# i386.net
KiCad netlist of a schematic drawn in Altium Designer
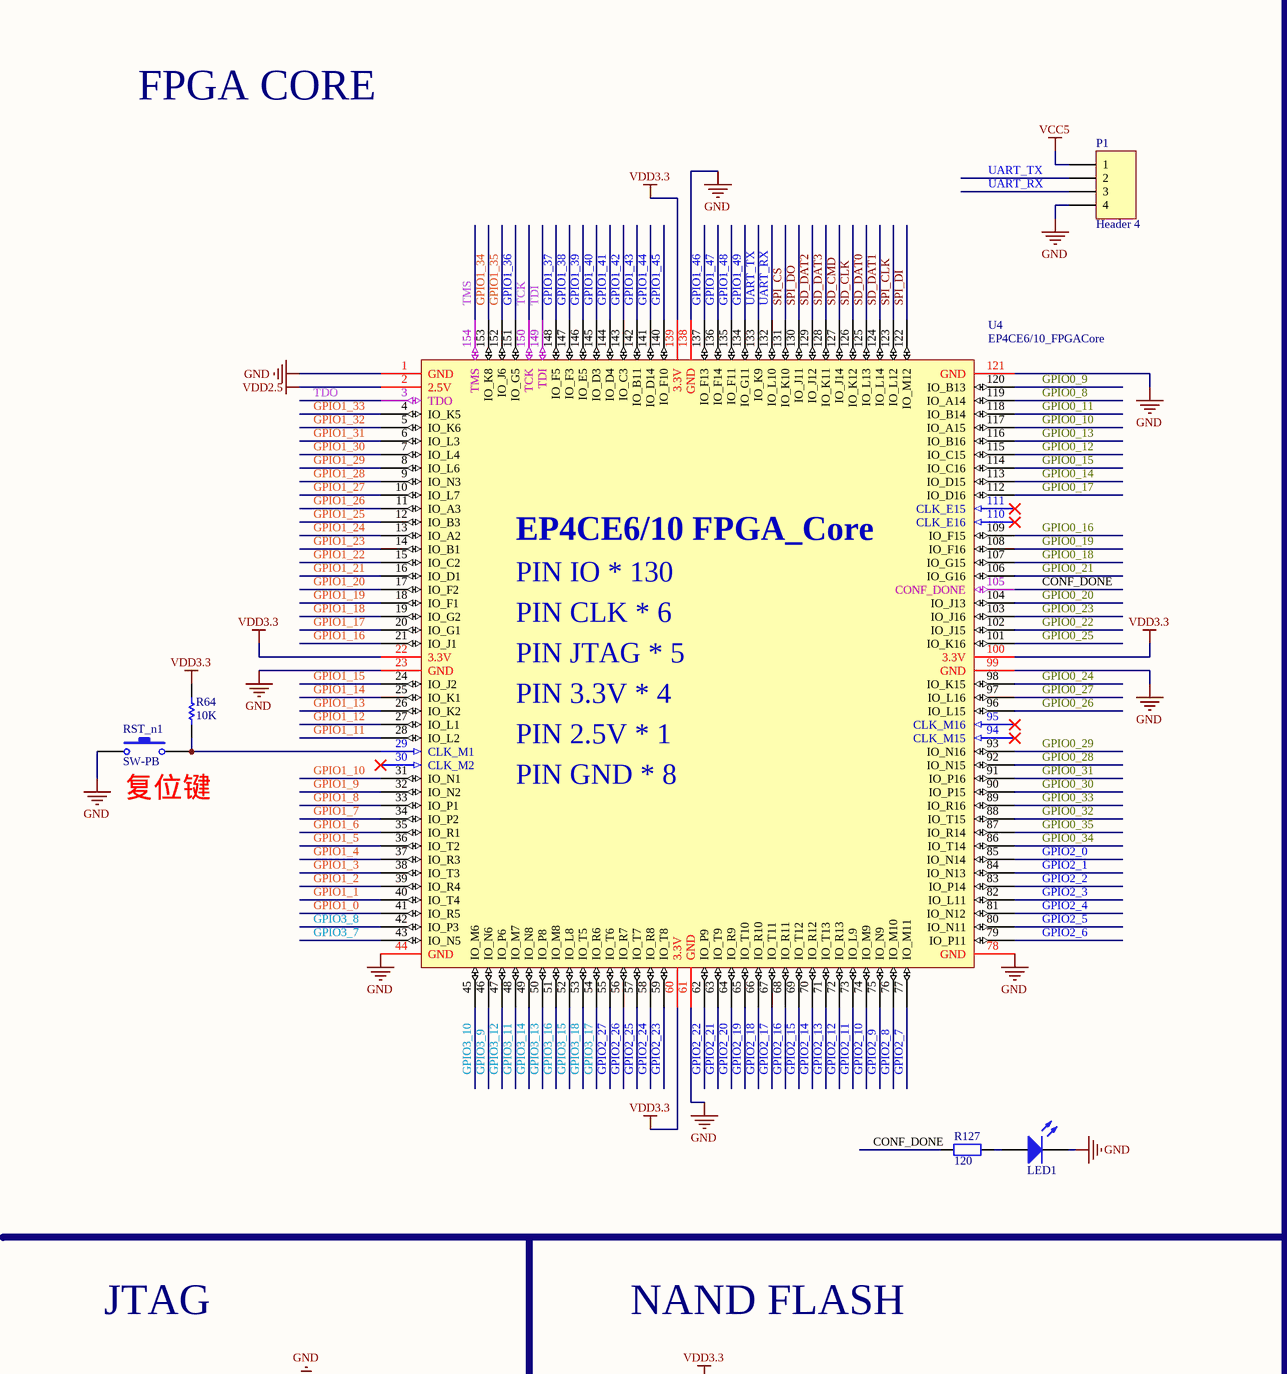
[diagram p0: i386.SchDoc, top left]
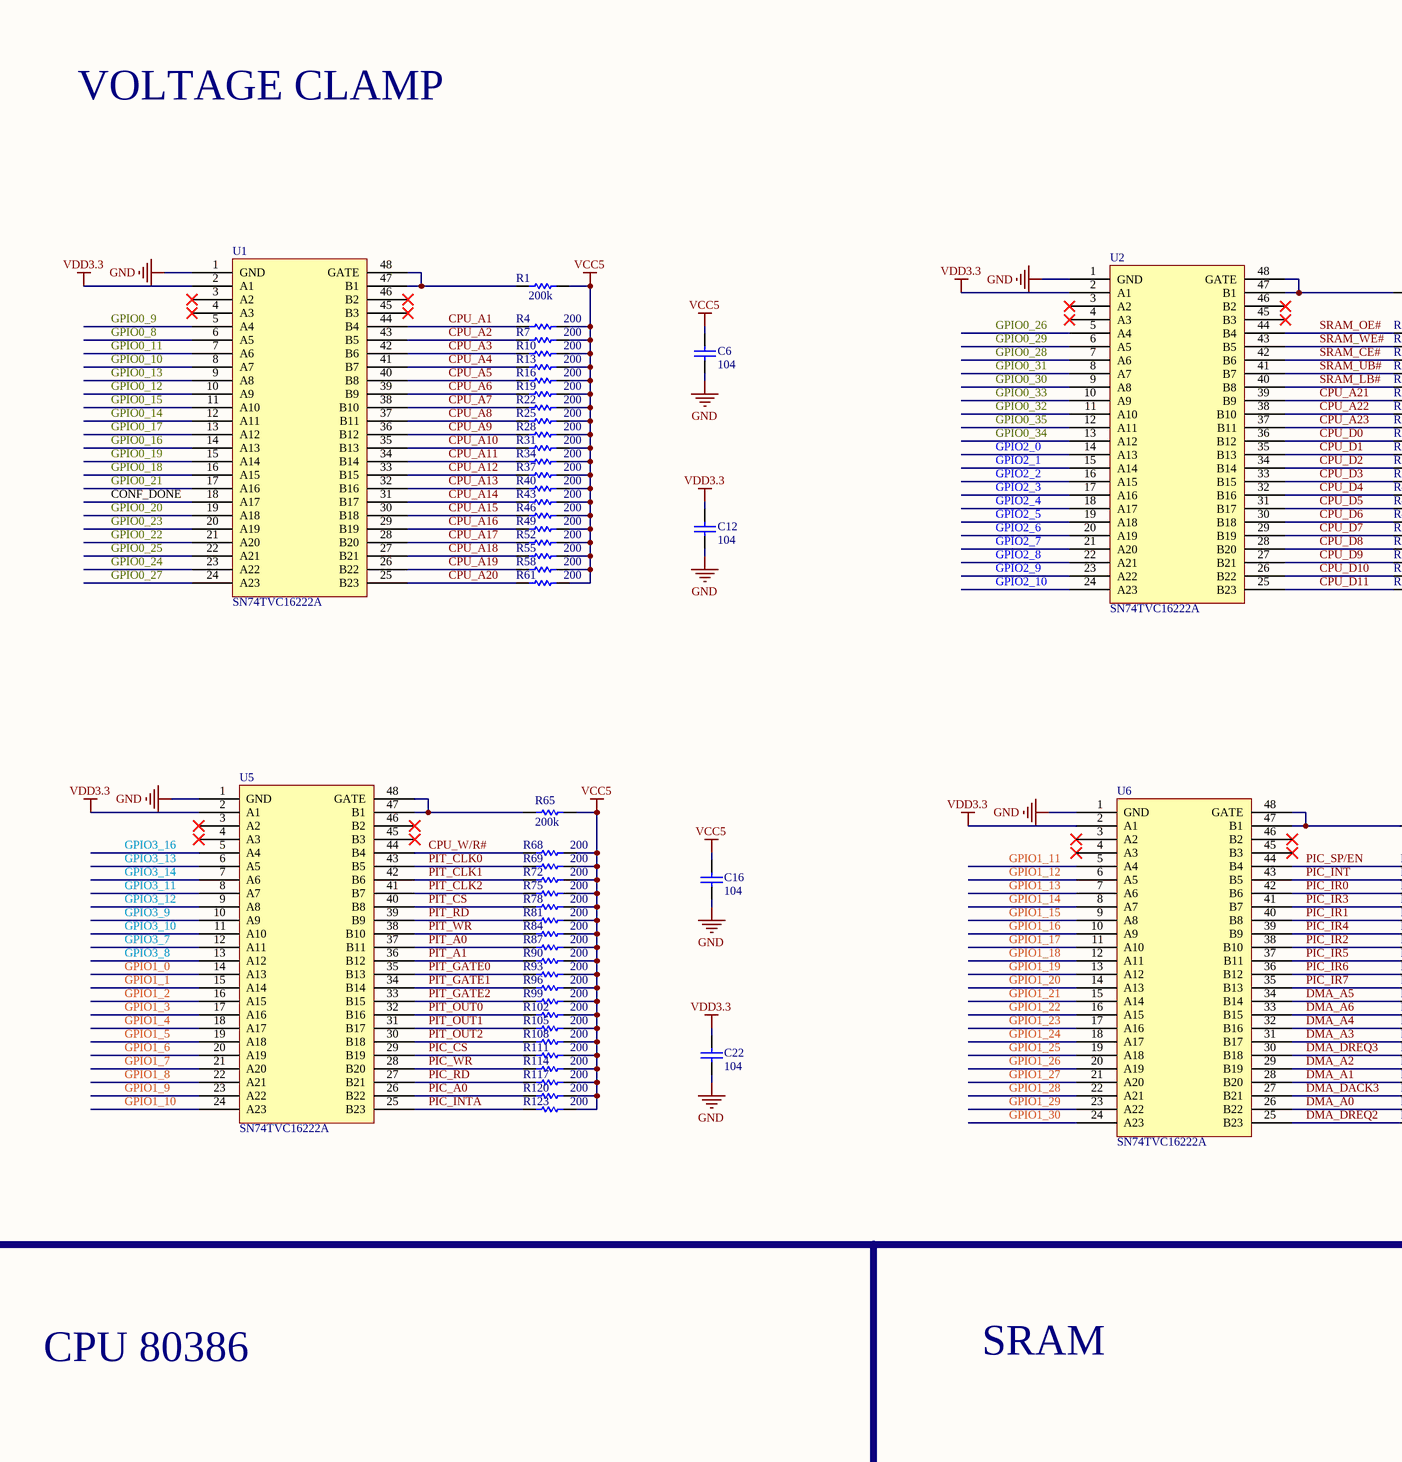
[diagram p1: i386.SchDoc, top middle]
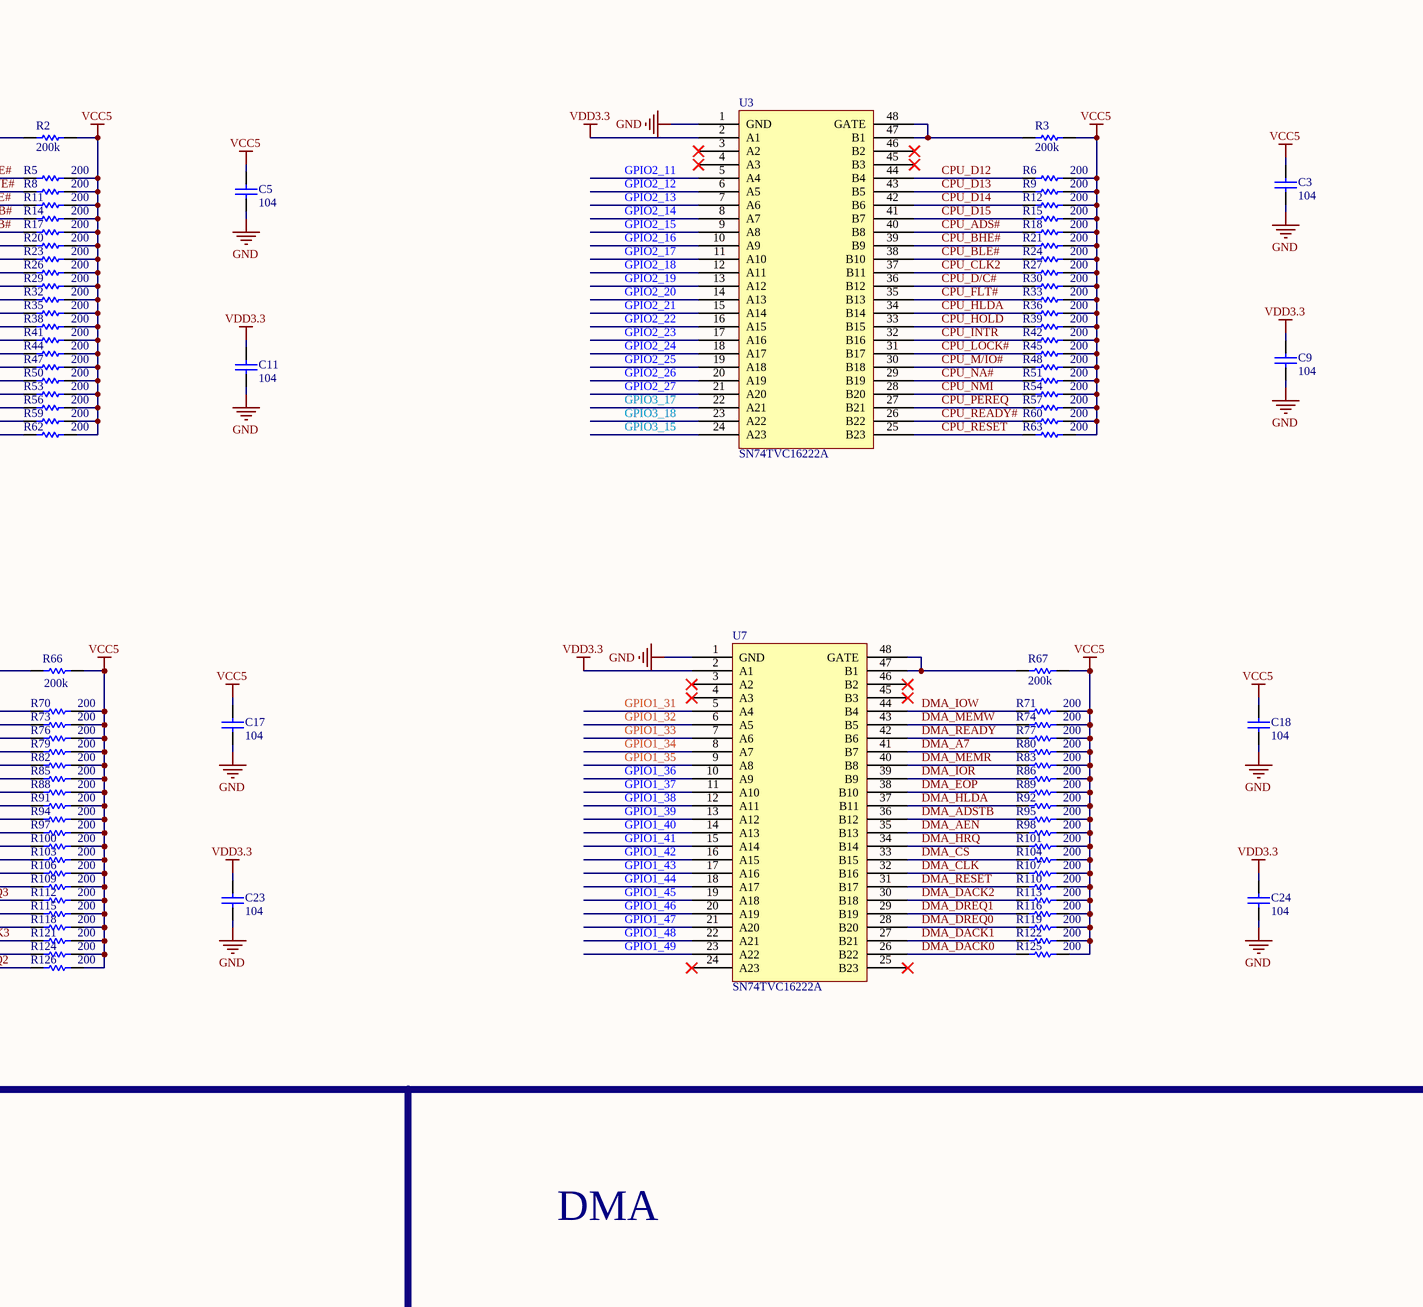
[diagram p2: i386.SchDoc, top right]
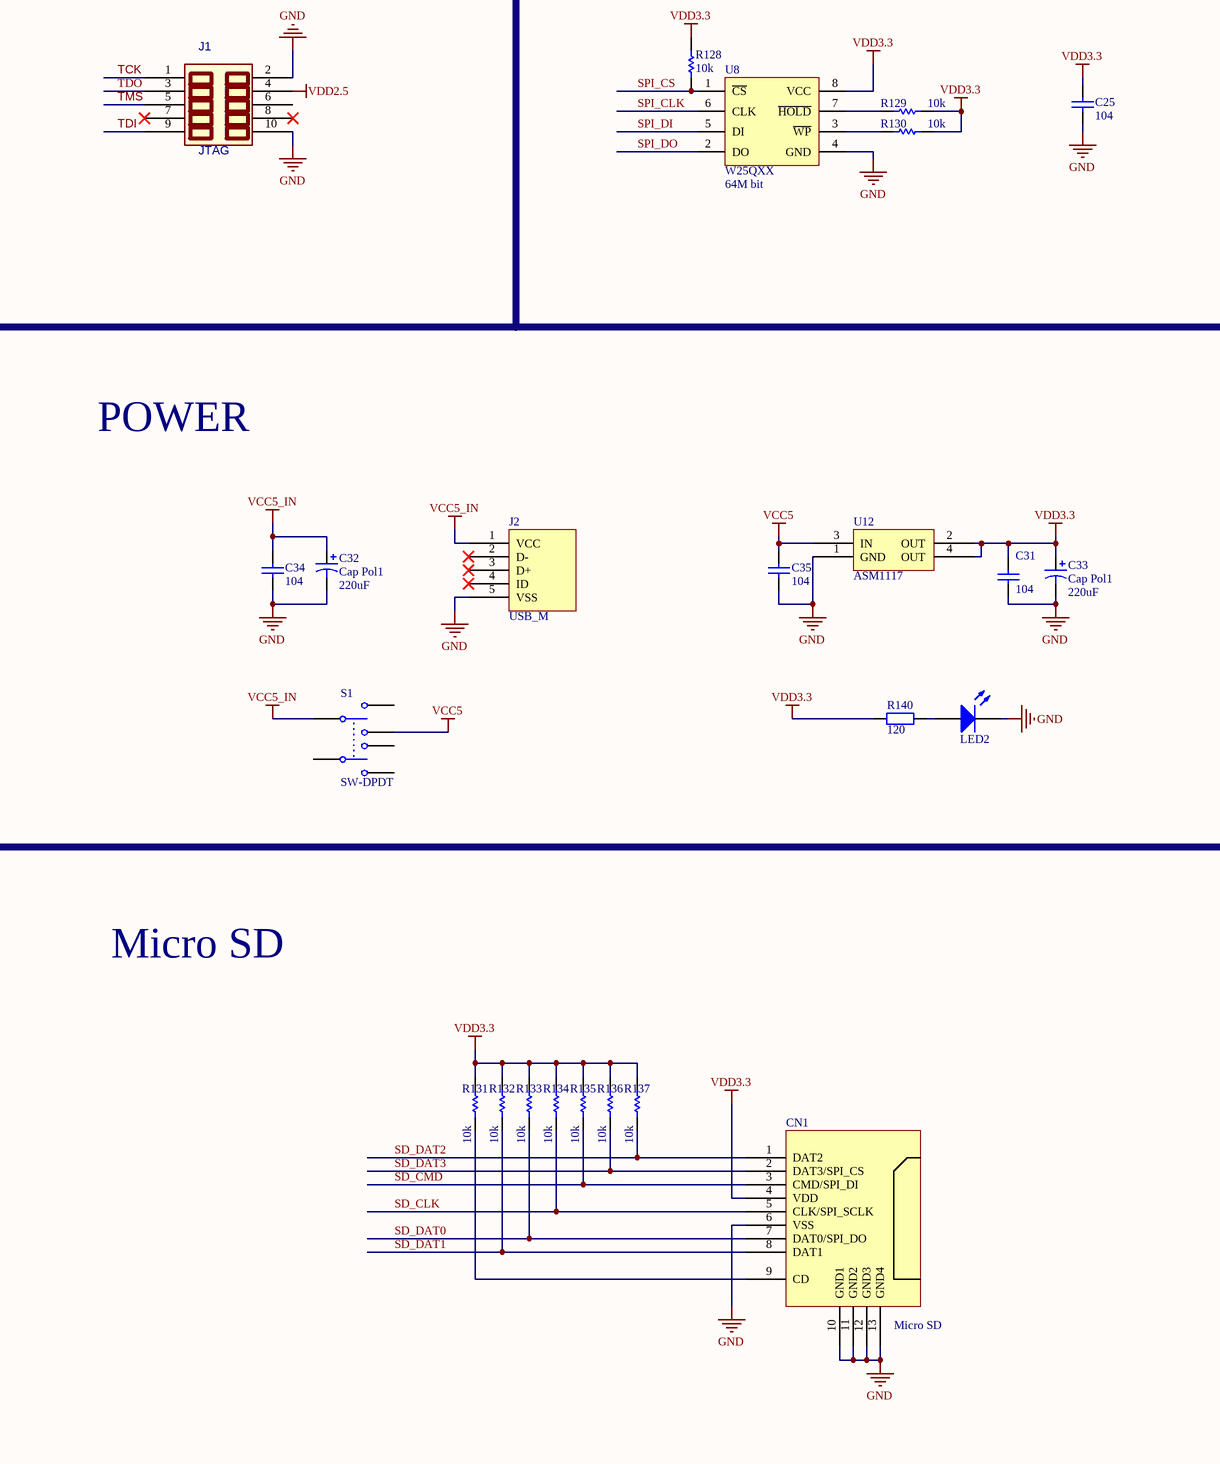
[diagram p3: i386.SchDoc, bottom left]
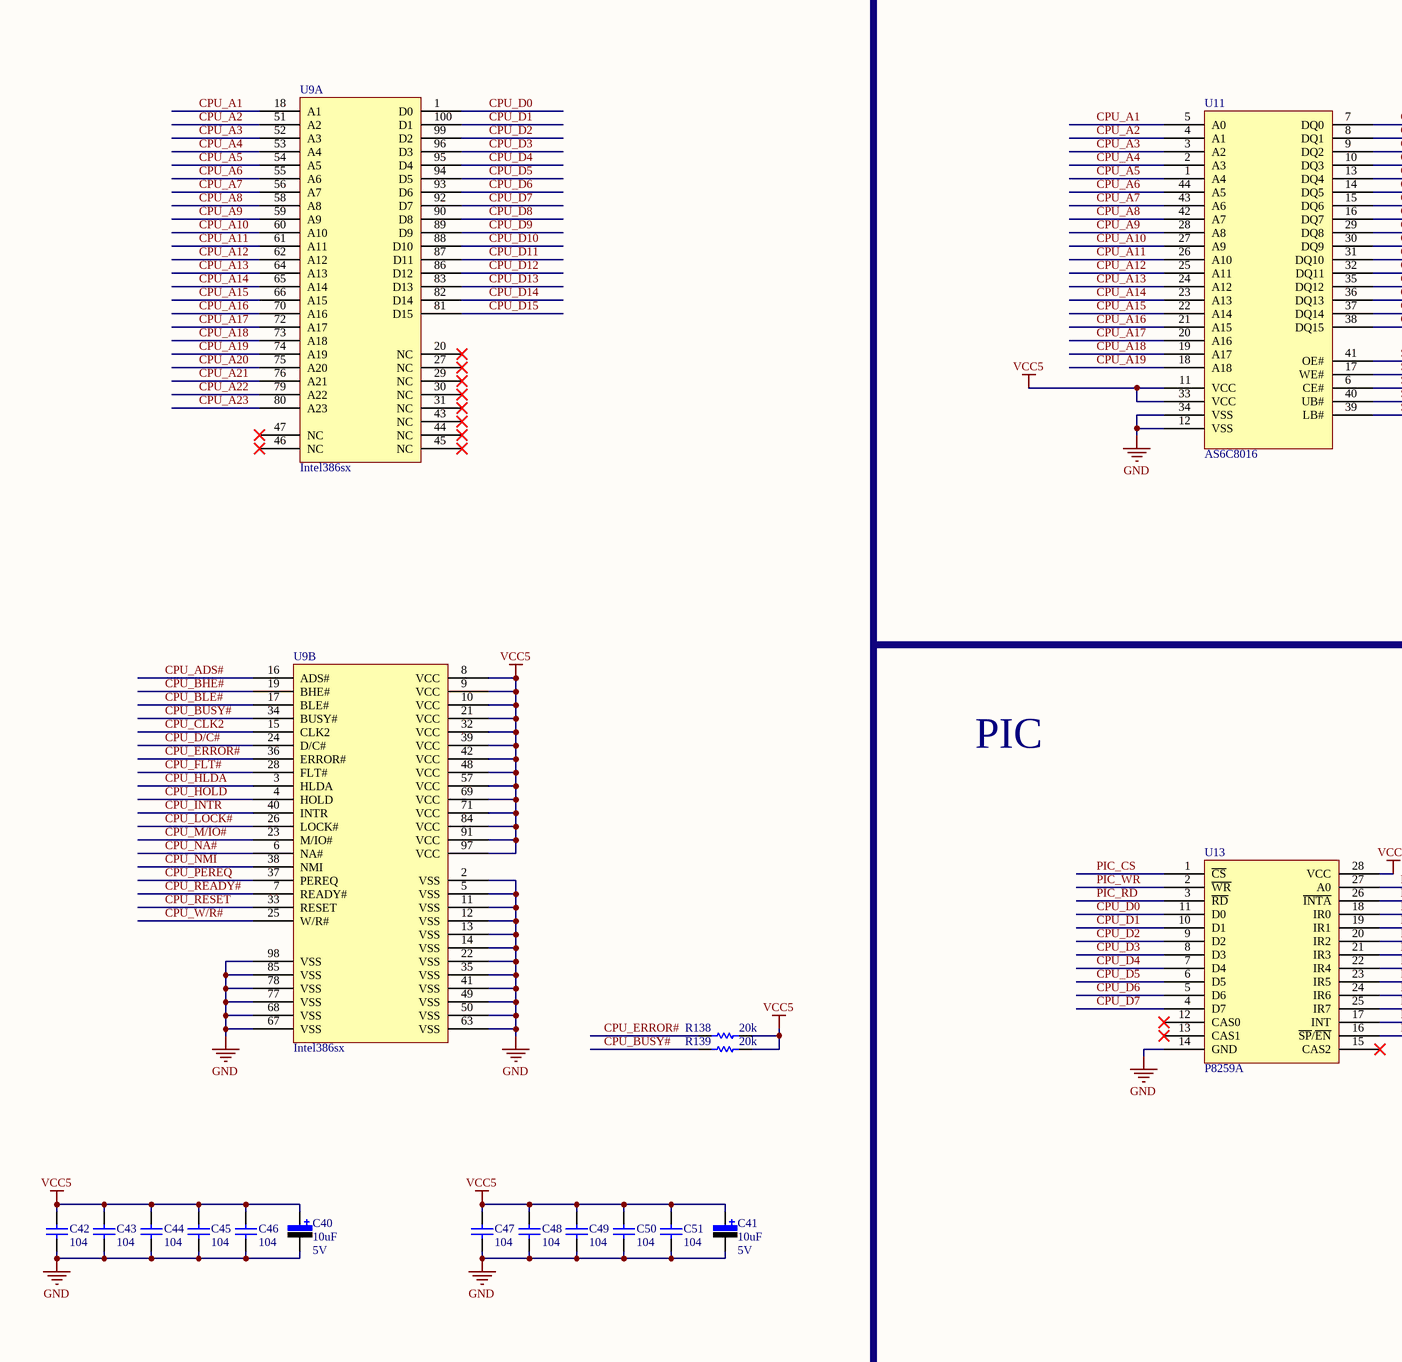
[diagram p4: i386.SchDoc, bottom middle]
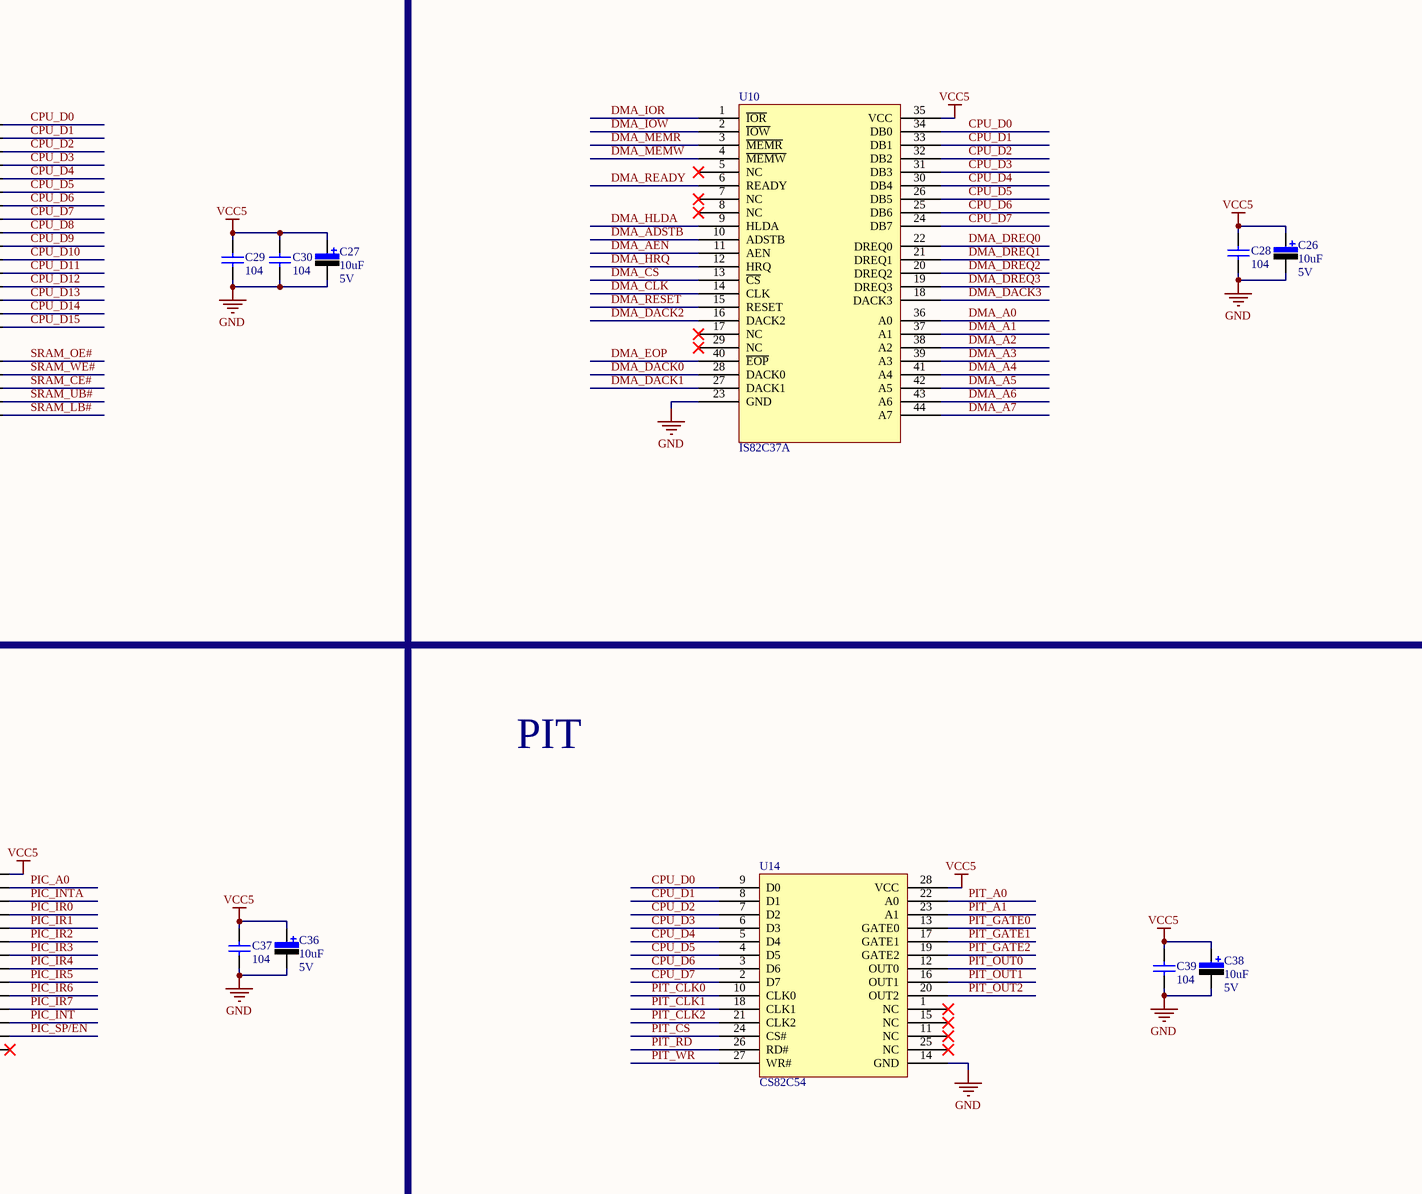
[diagram p5: i386.SchDoc, bottom right]

(export (version "E")
  (design (tool "Eeschema 10.0.6"))
  (components
    (comp (ref "C3")
      (value "104")
      (footprint "C0805")
      (description "Capacitor")
      (fields (field (name "PUBLISHER") "Altium Limited"))
      (libsource (lib "Miscellaneous Devices") (part "Cap"))
    )
    (comp (ref "C5")
      (value "104")
      (footprint "C0805")
      (description "Capacitor")
      (fields (field (name "PUBLISHER") "Altium Limited"))
      (libsource (lib "Miscellaneous Devices") (part "Cap"))
    )
    (comp (ref "C6")
      (value "104")
      (footprint "C0805")
      (description "Capacitor")
      (fields (field (name "PUBLISHER") "Altium Limited"))
      (libsource (lib "Miscellaneous Devices") (part "Cap"))
    )
    (comp (ref "C9")
      (value "104")
      (footprint "C0805")
      (description "Capacitor")
      (fields (field (name "PUBLISHER") "Altium Limited"))
      (libsource (lib "Miscellaneous Devices") (part "Cap"))
    )
    (comp (ref "C11")
      (value "104")
      (footprint "C0805")
      (description "Capacitor")
      (fields (field (name "PUBLISHER") "Altium Limited"))
      (libsource (lib "Miscellaneous Devices") (part "Cap"))
    )
    (comp (ref "C12")
      (value "104")
      (footprint "C0805")
      (description "Capacitor")
      (fields (field (name "PUBLISHER") "Altium Limited"))
      (libsource (lib "Miscellaneous Devices") (part "Cap"))
    )
    (comp (ref "C16")
      (value "104")
      (footprint "C0805")
      (description "Capacitor")
      (fields (field (name "PUBLISHER") "Altium Limited"))
      (libsource (lib "Miscellaneous Devices") (part "Cap"))
    )
    (comp (ref "C17")
      (value "104")
      (footprint "C0805")
      (description "Capacitor")
      (fields (field (name "PUBLISHER") "Altium Limited"))
      (libsource (lib "Miscellaneous Devices") (part "Cap"))
    )
    (comp (ref "C18")
      (value "104")
      (footprint "C0805")
      (description "Capacitor")
      (fields (field (name "PUBLISHER") "Altium Limited"))
      (libsource (lib "Miscellaneous Devices") (part "Cap"))
    )
    (comp (ref "C22")
      (value "104")
      (footprint "C0805")
      (description "Capacitor")
      (fields (field (name "PUBLISHER") "Altium Limited"))
      (libsource (lib "Miscellaneous Devices") (part "Cap"))
    )
    (comp (ref "C23")
      (value "104")
      (footprint "C0805")
      (description "Capacitor")
      (fields (field (name "PUBLISHER") "Altium Limited"))
      (libsource (lib "Miscellaneous Devices") (part "Cap"))
    )
    (comp (ref "C24")
      (value "104")
      (footprint "C0805")
      (description "Capacitor")
      (fields (field (name "PUBLISHER") "Altium Limited"))
      (libsource (lib "Miscellaneous Devices") (part "Cap"))
    )
    (comp (ref "C25")
      (value "104")
      (footprint "C0805")
      (description "Capacitor")
      (fields (field (name "PUBLISHER") "Altium Limited"))
      (libsource (lib "Miscellaneous Devices") (part "Cap"))
    )
    (comp (ref "C26")
      (value "10uF")
      (footprint "CAP-3528")
      (description "极性电解电容")
      (fields
        (field (name "VOL") "5V")
        (field (name "Comment") "Cap Pol")
        (field (name "PUBLISHER") "Altium Limited")
      )
      (libsource (lib "k7_ext") (part "Cap Pol"))
    )
    (comp (ref "C27")
      (value "10uF")
      (footprint "CAP-3528")
      (description "极性电解电容")
      (fields
        (field (name "VOL") "5V")
        (field (name "Comment") "Cap Pol")
        (field (name "PUBLISHER") "Altium Limited")
      )
      (libsource (lib "k7_ext") (part "Cap Pol"))
    )
    (comp (ref "C28")
      (value "104")
      (footprint "C0805")
      (description "Capacitor")
      (fields (field (name "PUBLISHER") "Altium Limited"))
      (libsource (lib "Miscellaneous Devices") (part "Cap"))
    )
    (comp (ref "C29")
      (value "104")
      (footprint "C0805")
      (description "Capacitor")
      (fields (field (name "PUBLISHER") "Altium Limited"))
      (libsource (lib "Miscellaneous Devices") (part "Cap"))
    )
    (comp (ref "C30")
      (value "104")
      (footprint "C0805")
      (description "Capacitor")
      (fields (field (name "PUBLISHER") "Altium Limited"))
      (libsource (lib "Miscellaneous Devices") (part "Cap"))
    )
    (comp (ref "C31")
      (value "104")
      (footprint "C0805")
      (description "Capacitor")
      (fields (field (name "PUBLISHER") "Altium Limited"))
      (libsource (lib "Miscellaneous Devices") (part "Cap"))
    )
    (comp (ref "C32")
      (value "Cap Pol1")
      (footprint "C-RB-S8")
      (description "Polarized Capacitor (Radial)")
      (fields (field (name "ALTIUM_VALUE") "220uF") (field (name "PUBLISHER") "Altium Limited"))
      (libsource (lib "Miscellaneous Devices") (part "Cap Pol1"))
    )
    (comp (ref "C33")
      (value "Cap Pol1")
      (footprint "C-RB-S8")
      (description "Polarized Capacitor (Radial)")
      (fields (field (name "ALTIUM_VALUE") "220uF") (field (name "PUBLISHER") "Altium Limited"))
      (libsource (lib "Miscellaneous Devices") (part "Cap Pol1"))
    )
    (comp (ref "C34")
      (value "104")
      (footprint "C0805")
      (description "Capacitor")
      (fields (field (name "PUBLISHER") "Altium Limited"))
      (libsource (lib "Miscellaneous Devices") (part "Cap"))
    )
    (comp (ref "C35")
      (value "104")
      (footprint "C0805")
      (description "Capacitor")
      (fields (field (name "PUBLISHER") "Altium Limited"))
      (libsource (lib "Miscellaneous Devices") (part "Cap"))
    )
    (comp (ref "C36")
      (value "10uF")
      (footprint "CAP-3528")
      (description "极性电解电容")
      (fields
        (field (name "VOL") "5V")
        (field (name "Comment") "Cap Pol")
        (field (name "PUBLISHER") "Altium Limited")
      )
      (libsource (lib "k7_ext") (part "Cap Pol"))
    )
    (comp (ref "C37")
      (value "104")
      (footprint "C0805")
      (description "Capacitor")
      (fields (field (name "PUBLISHER") "Altium Limited"))
      (libsource (lib "Miscellaneous Devices") (part "Cap"))
    )
    (comp (ref "C38")
      (value "10uF")
      (footprint "CAP-3528")
      (description "极性电解电容")
      (fields
        (field (name "VOL") "5V")
        (field (name "Comment") "Cap Pol")
        (field (name "PUBLISHER") "Altium Limited")
      )
      (libsource (lib "k7_ext") (part "Cap Pol"))
    )
    (comp (ref "C39")
      (value "104")
      (footprint "C0805")
      (description "Capacitor")
      (fields (field (name "PUBLISHER") "Altium Limited"))
      (libsource (lib "Miscellaneous Devices") (part "Cap"))
    )
    (comp (ref "C40")
      (value "10uF")
      (footprint "CAP-3528")
      (description "极性电解电容")
      (fields
        (field (name "VOL") "5V")
        (field (name "Comment") "Cap Pol")
        (field (name "PUBLISHER") "Altium Limited")
      )
      (libsource (lib "k7_ext") (part "Cap Pol"))
    )
    (comp (ref "C41")
      (value "10uF")
      (footprint "CAP-3528")
      (description "极性电解电容")
      (fields
        (field (name "VOL") "5V")
        (field (name "Comment") "Cap Pol")
        (field (name "PUBLISHER") "Altium Limited")
      )
      (libsource (lib "k7_ext") (part "Cap Pol"))
    )
    (comp (ref "C42")
      (value "104")
      (footprint "C0805")
      (description "Capacitor")
      (fields (field (name "PUBLISHER") "Altium Limited"))
      (libsource (lib "Miscellaneous Devices") (part "Cap"))
    )
    (comp (ref "C43")
      (value "104")
      (footprint "C0805")
      (description "Capacitor")
      (fields (field (name "PUBLISHER") "Altium Limited"))
      (libsource (lib "Miscellaneous Devices") (part "Cap"))
    )
    (comp (ref "C44")
      (value "104")
      (footprint "C0805")
      (description "Capacitor")
      (fields (field (name "PUBLISHER") "Altium Limited"))
      (libsource (lib "Miscellaneous Devices") (part "Cap"))
    )
    (comp (ref "C45")
      (value "104")
      (footprint "C0805")
      (description "Capacitor")
      (fields (field (name "PUBLISHER") "Altium Limited"))
      (libsource (lib "Miscellaneous Devices") (part "Cap"))
    )
    (comp (ref "C46")
      (value "104")
      (footprint "C0805")
      (description "Capacitor")
      (fields (field (name "PUBLISHER") "Altium Limited"))
      (libsource (lib "Miscellaneous Devices") (part "Cap"))
    )
    (comp (ref "C47")
      (value "104")
      (footprint "C0805")
      (description "Capacitor")
      (fields (field (name "PUBLISHER") "Altium Limited"))
      (libsource (lib "Miscellaneous Devices") (part "Cap"))
    )
    (comp (ref "C48")
      (value "104")
      (footprint "C0805")
      (description "Capacitor")
      (fields (field (name "PUBLISHER") "Altium Limited"))
      (libsource (lib "Miscellaneous Devices") (part "Cap"))
    )
    (comp (ref "C49")
      (value "104")
      (footprint "C0805")
      (description "Capacitor")
      (fields (field (name "PUBLISHER") "Altium Limited"))
      (libsource (lib "Miscellaneous Devices") (part "Cap"))
    )
    (comp (ref "C50")
      (value "104")
      (footprint "C0805")
      (description "Capacitor")
      (fields (field (name "PUBLISHER") "Altium Limited"))
      (libsource (lib "Miscellaneous Devices") (part "Cap"))
    )
    (comp (ref "C51")
      (value "104")
      (footprint "C0805")
      (description "Capacitor")
      (fields (field (name "PUBLISHER") "Altium Limited"))
      (libsource (lib "Miscellaneous Devices") (part "Cap"))
    )
    (comp (ref "CN1")
      (value "Micro SD")
      (footprint "SDCARD-M")
      (description "Micro SD卡座")
      (libsource (lib "k7_ext") (part "Micro SD卡座"))
    )
    (comp (ref "J1") (value "JTAG") (footprint "HDR5X2_B1") (libsource (lib "*") (part "JTAG-10_Dup1")))
    (comp (ref "J2")
      (value "USB_M")
      (footprint "USB_MICRO")
      (description "MicroUSB接口")
      (libsource (lib "k7_ext") (part "USB_M"))
    )
    (comp (ref "LED1")
      (value "LED0")
      (footprint "LED-0402")
      (description "发光二极管")
      (fields (field (name "PUBLISHER") "Altium Limited"))
      (libsource (lib "k7_ext") (part "LED0"))
    )
    (comp (ref "LED2")
      (value "LED0")
      (footprint "LED-0402")
      (description "发光二极管")
      (fields (field (name "PUBLISHER") "Altium Limited"))
      (libsource (lib "k7_ext") (part "LED0"))
    )
    (comp (ref "P1")
      (value "Header 4")
      (footprint "HDR1X4")
      (description "Header, 4-Pin")
      (fields (field (name "PUBLISHER") "Altium Limited"))
      (libsource (lib "Miscellaneous Connectors") (part "Header 4"))
    )
    (comp (ref "R1")
      (value "200k")
      (footprint "0402")
      (description "Resistor")
      (fields (field (name "Comment") "Res1") (field (name "PUBLISHER") "Altium Limited"))
      (libsource (lib "Miscellaneous Devices") (part "Res1"))
    )
    (comp (ref "R2")
      (value "200k")
      (footprint "0402")
      (description "Resistor")
      (fields (field (name "Comment") "Res1") (field (name "PUBLISHER") "Altium Limited"))
      (libsource (lib "Miscellaneous Devices") (part "Res1"))
    )
    (comp (ref "R3")
      (value "200k")
      (footprint "0402")
      (description "Resistor")
      (fields (field (name "Comment") "Res1") (field (name "PUBLISHER") "Altium Limited"))
      (libsource (lib "Miscellaneous Devices") (part "Res1"))
    )
    (comp (ref "R4")
      (value "200")
      (footprint "0402")
      (description "Resistor")
      (fields (field (name "Comment") "Res1") (field (name "PUBLISHER") "Altium Limited"))
      (libsource (lib "Miscellaneous Devices") (part "Res1"))
    )
    (comp (ref "R5")
      (value "200")
      (footprint "0402")
      (description "Resistor")
      (fields (field (name "Comment") "Res1") (field (name "PUBLISHER") "Altium Limited"))
      (libsource (lib "Miscellaneous Devices") (part "Res1"))
    )
    (comp (ref "R6")
      (value "200")
      (footprint "0402")
      (description "Resistor")
      (fields (field (name "Comment") "Res1") (field (name "PUBLISHER") "Altium Limited"))
      (libsource (lib "Miscellaneous Devices") (part "Res1"))
    )
    (comp (ref "R7")
      (value "200")
      (footprint "0402")
      (description "Resistor")
      (fields (field (name "Comment") "Res1") (field (name "PUBLISHER") "Altium Limited"))
      (libsource (lib "Miscellaneous Devices") (part "Res1"))
    )
    (comp (ref "R8")
      (value "200")
      (footprint "0402")
      (description "Resistor")
      (fields (field (name "Comment") "Res1") (field (name "PUBLISHER") "Altium Limited"))
      (libsource (lib "Miscellaneous Devices") (part "Res1"))
    )
    (comp (ref "R9")
      (value "200")
      (footprint "0402")
      (description "Resistor")
      (fields (field (name "Comment") "Res1") (field (name "PUBLISHER") "Altium Limited"))
      (libsource (lib "Miscellaneous Devices") (part "Res1"))
    )
    (comp (ref "R10")
      (value "200")
      (footprint "0402")
      (description "Resistor")
      (fields (field (name "Comment") "Res1") (field (name "PUBLISHER") "Altium Limited"))
      (libsource (lib "Miscellaneous Devices") (part "Res1"))
    )
    (comp (ref "R11")
      (value "200")
      (footprint "0402")
      (description "Resistor")
      (fields (field (name "Comment") "Res1") (field (name "PUBLISHER") "Altium Limited"))
      (libsource (lib "Miscellaneous Devices") (part "Res1"))
    )
    (comp (ref "R12")
      (value "200")
      (footprint "0402")
      (description "Resistor")
      (fields (field (name "Comment") "Res1") (field (name "PUBLISHER") "Altium Limited"))
      (libsource (lib "Miscellaneous Devices") (part "Res1"))
    )
    (comp (ref "R13")
      (value "200")
      (footprint "0402")
      (description "Resistor")
      (fields (field (name "Comment") "Res1") (field (name "PUBLISHER") "Altium Limited"))
      (libsource (lib "Miscellaneous Devices") (part "Res1"))
    )
    (comp (ref "R14")
      (value "200")
      (footprint "0402")
      (description "Resistor")
      (fields (field (name "Comment") "Res1") (field (name "PUBLISHER") "Altium Limited"))
      (libsource (lib "Miscellaneous Devices") (part "Res1"))
    )
    (comp (ref "R15")
      (value "200")
      (footprint "0402")
      (description "Resistor")
      (fields (field (name "Comment") "Res1") (field (name "PUBLISHER") "Altium Limited"))
      (libsource (lib "Miscellaneous Devices") (part "Res1"))
    )
    (comp (ref "R16")
      (value "200")
      (footprint "0402")
      (description "Resistor")
      (fields (field (name "Comment") "Res1") (field (name "PUBLISHER") "Altium Limited"))
      (libsource (lib "Miscellaneous Devices") (part "Res1"))
    )
    (comp (ref "R17")
      (value "200")
      (footprint "0402")
      (description "Resistor")
      (fields (field (name "Comment") "Res1") (field (name "PUBLISHER") "Altium Limited"))
      (libsource (lib "Miscellaneous Devices") (part "Res1"))
    )
    (comp (ref "R18")
      (value "200")
      (footprint "0402")
      (description "Resistor")
      (fields (field (name "Comment") "Res1") (field (name "PUBLISHER") "Altium Limited"))
      (libsource (lib "Miscellaneous Devices") (part "Res1"))
    )
    (comp (ref "R19")
      (value "200")
      (footprint "0402")
      (description "Resistor")
      (fields (field (name "Comment") "Res1") (field (name "PUBLISHER") "Altium Limited"))
      (libsource (lib "Miscellaneous Devices") (part "Res1"))
    )
    (comp (ref "R20")
      (value "200")
      (footprint "0402")
      (description "Resistor")
      (fields (field (name "Comment") "Res1") (field (name "PUBLISHER") "Altium Limited"))
      (libsource (lib "Miscellaneous Devices") (part "Res1"))
    )
    (comp (ref "R21")
      (value "200")
      (footprint "0402")
      (description "Resistor")
      (fields (field (name "Comment") "Res1") (field (name "PUBLISHER") "Altium Limited"))
      (libsource (lib "Miscellaneous Devices") (part "Res1"))
    )
    (comp (ref "R22")
      (value "200")
      (footprint "0402")
      (description "Resistor")
      (fields (field (name "Comment") "Res1") (field (name "PUBLISHER") "Altium Limited"))
      (libsource (lib "Miscellaneous Devices") (part "Res1"))
    )
    (comp (ref "R23")
      (value "200")
      (footprint "0402")
      (description "Resistor")
      (fields (field (name "Comment") "Res1") (field (name "PUBLISHER") "Altium Limited"))
      (libsource (lib "Miscellaneous Devices") (part "Res1"))
    )
    (comp (ref "R24")
      (value "200")
      (footprint "0402")
      (description "Resistor")
      (fields (field (name "Comment") "Res1") (field (name "PUBLISHER") "Altium Limited"))
      (libsource (lib "Miscellaneous Devices") (part "Res1"))
    )
    (comp (ref "R25")
      (value "200")
      (footprint "0402")
      (description "Resistor")
      (fields (field (name "Comment") "Res1") (field (name "PUBLISHER") "Altium Limited"))
      (libsource (lib "Miscellaneous Devices") (part "Res1"))
    )
    (comp (ref "R26")
      (value "200")
      (footprint "0402")
      (description "Resistor")
      (fields (field (name "Comment") "Res1") (field (name "PUBLISHER") "Altium Limited"))
      (libsource (lib "Miscellaneous Devices") (part "Res1"))
    )
    (comp (ref "R27")
      (value "200")
      (footprint "0402")
      (description "Resistor")
      (fields (field (name "Comment") "Res1") (field (name "PUBLISHER") "Altium Limited"))
      (libsource (lib "Miscellaneous Devices") (part "Res1"))
    )
    (comp (ref "R28")
      (value "200")
      (footprint "0402")
      (description "Resistor")
      (fields (field (name "Comment") "Res1") (field (name "PUBLISHER") "Altium Limited"))
      (libsource (lib "Miscellaneous Devices") (part "Res1"))
    )
    (comp (ref "R29")
      (value "200")
      (footprint "0402")
      (description "Resistor")
      (fields (field (name "Comment") "Res1") (field (name "PUBLISHER") "Altium Limited"))
      (libsource (lib "Miscellaneous Devices") (part "Res1"))
    )
    (comp (ref "R30")
      (value "200")
      (footprint "0402")
      (description "Resistor")
      (fields (field (name "Comment") "Res1") (field (name "PUBLISHER") "Altium Limited"))
      (libsource (lib "Miscellaneous Devices") (part "Res1"))
    )
    (comp (ref "R31")
      (value "200")
      (footprint "0402")
      (description "Resistor")
      (fields (field (name "Comment") "Res1") (field (name "PUBLISHER") "Altium Limited"))
      (libsource (lib "Miscellaneous Devices") (part "Res1"))
    )
    (comp (ref "R32")
      (value "200")
      (footprint "0402")
      (description "Resistor")
      (fields (field (name "Comment") "Res1") (field (name "PUBLISHER") "Altium Limited"))
      (libsource (lib "Miscellaneous Devices") (part "Res1"))
    )
    (comp (ref "R33")
      (value "200")
      (footprint "0402")
      (description "Resistor")
      (fields (field (name "Comment") "Res1") (field (name "PUBLISHER") "Altium Limited"))
      (libsource (lib "Miscellaneous Devices") (part "Res1"))
    )
    (comp (ref "R34")
      (value "200")
      (footprint "0402")
      (description "Resistor")
      (fields (field (name "Comment") "Res1") (field (name "PUBLISHER") "Altium Limited"))
      (libsource (lib "Miscellaneous Devices") (part "Res1"))
    )
    (comp (ref "R35")
      (value "200")
      (footprint "0402")
      (description "Resistor")
      (fields (field (name "Comment") "Res1") (field (name "PUBLISHER") "Altium Limited"))
      (libsource (lib "Miscellaneous Devices") (part "Res1"))
    )
    (comp (ref "R36")
      (value "200")
      (footprint "0402")
      (description "Resistor")
      (fields (field (name "Comment") "Res1") (field (name "PUBLISHER") "Altium Limited"))
      (libsource (lib "Miscellaneous Devices") (part "Res1"))
    )
    (comp (ref "R37")
      (value "200")
      (footprint "0402")
      (description "Resistor")
      (fields (field (name "Comment") "Res1") (field (name "PUBLISHER") "Altium Limited"))
      (libsource (lib "Miscellaneous Devices") (part "Res1"))
    )
    (comp (ref "R38")
      (value "200")
      (footprint "0402")
      (description "Resistor")
      (fields (field (name "Comment") "Res1") (field (name "PUBLISHER") "Altium Limited"))
      (libsource (lib "Miscellaneous Devices") (part "Res1"))
    )
    (comp (ref "R39")
      (value "200")
      (footprint "0402")
      (description "Resistor")
      (fields (field (name "Comment") "Res1") (field (name "PUBLISHER") "Altium Limited"))
      (libsource (lib "Miscellaneous Devices") (part "Res1"))
    )
    (comp (ref "R40")
      (value "200")
      (footprint "0402")
      (description "Resistor")
      (fields (field (name "Comment") "Res1") (field (name "PUBLISHER") "Altium Limited"))
      (libsource (lib "Miscellaneous Devices") (part "Res1"))
    )
    (comp (ref "R41")
      (value "200")
      (footprint "0402")
      (description "Resistor")
      (fields (field (name "Comment") "Res1") (field (name "PUBLISHER") "Altium Limited"))
      (libsource (lib "Miscellaneous Devices") (part "Res1"))
    )
    (comp (ref "R42")
      (value "200")
      (footprint "0402")
      (description "Resistor")
      (fields (field (name "Comment") "Res1") (field (name "PUBLISHER") "Altium Limited"))
      (libsource (lib "Miscellaneous Devices") (part "Res1"))
    )
    (comp (ref "R43")
      (value "200")
      (footprint "0402")
      (description "Resistor")
      (fields (field (name "Comment") "Res1") (field (name "PUBLISHER") "Altium Limited"))
      (libsource (lib "Miscellaneous Devices") (part "Res1"))
    )
    (comp (ref "R44")
      (value "200")
      (footprint "0402")
      (description "Resistor")
      (fields (field (name "Comment") "Res1") (field (name "PUBLISHER") "Altium Limited"))
      (libsource (lib "Miscellaneous Devices") (part "Res1"))
    )
    (comp (ref "R45")
      (value "200")
      (footprint "0402")
      (description "Resistor")
      (fields (field (name "Comment") "Res1") (field (name "PUBLISHER") "Altium Limited"))
      (libsource (lib "Miscellaneous Devices") (part "Res1"))
    )
    (comp (ref "R46")
      (value "200")
      (footprint "0402")
      (description "Resistor")
      (fields (field (name "Comment") "Res1") (field (name "PUBLISHER") "Altium Limited"))
      (libsource (lib "Miscellaneous Devices") (part "Res1"))
    )
    (comp (ref "R47")
      (value "200")
      (footprint "0402")
      (description "Resistor")
      (fields (field (name "Comment") "Res1") (field (name "PUBLISHER") "Altium Limited"))
      (libsource (lib "Miscellaneous Devices") (part "Res1"))
    )
    (comp (ref "R48")
      (value "200")
      (footprint "0402")
      (description "Resistor")
      (fields (field (name "Comment") "Res1") (field (name "PUBLISHER") "Altium Limited"))
      (libsource (lib "Miscellaneous Devices") (part "Res1"))
    )
    (comp (ref "R49")
      (value "200")
      (footprint "0402")
      (description "Resistor")
      (fields (field (name "Comment") "Res1") (field (name "PUBLISHER") "Altium Limited"))
      (libsource (lib "Miscellaneous Devices") (part "Res1"))
    )
    (comp (ref "R50")
      (value "200")
      (footprint "0402")
      (description "Resistor")
      (fields (field (name "Comment") "Res1") (field (name "PUBLISHER") "Altium Limited"))
      (libsource (lib "Miscellaneous Devices") (part "Res1"))
    )
    (comp (ref "R51")
      (value "200")
      (footprint "0402")
      (description "Resistor")
      (fields (field (name "Comment") "Res1") (field (name "PUBLISHER") "Altium Limited"))
      (libsource (lib "Miscellaneous Devices") (part "Res1"))
    )
    (comp (ref "R52")
      (value "200")
      (footprint "0402")
      (description "Resistor")
      (fields (field (name "Comment") "Res1") (field (name "PUBLISHER") "Altium Limited"))
      (libsource (lib "Miscellaneous Devices") (part "Res1"))
    )
    (comp (ref "R53")
      (value "200")
      (footprint "0402")
      (description "Resistor")
      (fields (field (name "Comment") "Res1") (field (name "PUBLISHER") "Altium Limited"))
      (libsource (lib "Miscellaneous Devices") (part "Res1"))
    )
    (comp (ref "R54")
      (value "200")
      (footprint "0402")
      (description "Resistor")
      (fields (field (name "Comment") "Res1") (field (name "PUBLISHER") "Altium Limited"))
      (libsource (lib "Miscellaneous Devices") (part "Res1"))
    )
    (comp (ref "R55")
      (value "200")
      (footprint "0402")
      (description "Resistor")
      (fields (field (name "Comment") "Res1") (field (name "PUBLISHER") "Altium Limited"))
      (libsource (lib "Miscellaneous Devices") (part "Res1"))
    )
    (comp (ref "R56")
      (value "200")
      (footprint "0402")
      (description "Resistor")
      (fields (field (name "Comment") "Res1") (field (name "PUBLISHER") "Altium Limited"))
      (libsource (lib "Miscellaneous Devices") (part "Res1"))
    )
    (comp (ref "R57")
      (value "200")
      (footprint "0402")
      (description "Resistor")
      (fields (field (name "Comment") "Res1") (field (name "PUBLISHER") "Altium Limited"))
      (libsource (lib "Miscellaneous Devices") (part "Res1"))
    )
    (comp (ref "R58")
      (value "200")
      (footprint "0402")
      (description "Resistor")
      (fields (field (name "Comment") "Res1") (field (name "PUBLISHER") "Altium Limited"))
      (libsource (lib "Miscellaneous Devices") (part "Res1"))
    )
    (comp (ref "R59")
      (value "200")
      (footprint "0402")
      (description "Resistor")
      (fields (field (name "Comment") "Res1") (field (name "PUBLISHER") "Altium Limited"))
      (libsource (lib "Miscellaneous Devices") (part "Res1"))
    )
    (comp (ref "R60")
      (value "200")
      (footprint "0402")
      (description "Resistor")
      (fields (field (name "Comment") "Res1") (field (name "PUBLISHER") "Altium Limited"))
      (libsource (lib "Miscellaneous Devices") (part "Res1"))
    )
    (comp (ref "R61")
      (value "200")
      (footprint "0402")
      (description "Resistor")
      (fields (field (name "Comment") "Res1") (field (name "PUBLISHER") "Altium Limited"))
      (libsource (lib "Miscellaneous Devices") (part "Res1"))
    )
    (comp (ref "R62")
      (value "200")
      (footprint "0402")
      (description "Resistor")
      (fields (field (name "Comment") "Res1") (field (name "PUBLISHER") "Altium Limited"))
      (libsource (lib "Miscellaneous Devices") (part "Res1"))
    )
    (comp (ref "R63")
      (value "200")
      (footprint "0402")
      (description "Resistor")
      (fields (field (name "Comment") "Res1") (field (name "PUBLISHER") "Altium Limited"))
      (libsource (lib "Miscellaneous Devices") (part "Res1"))
    )
    (comp (ref "R64")
      (value "10K")
      (footprint "0402")
      (description "Resistor")
      (fields (field (name "PUBLISHER") "Altium Limited"))
      (libsource (lib "Miscellaneous Devices") (part "Res1"))
    )
    (comp (ref "R65")
      (value "200k")
      (footprint "0402")
      (description "Resistor")
      (fields (field (name "Comment") "Res1") (field (name "PUBLISHER") "Altium Limited"))
      (libsource (lib "Miscellaneous Devices") (part "Res1"))
    )
    (comp (ref "R66")
      (value "200k")
      (footprint "0402")
      (description "Resistor")
      (fields (field (name "Comment") "Res1") (field (name "PUBLISHER") "Altium Limited"))
      (libsource (lib "Miscellaneous Devices") (part "Res1"))
    )
    (comp (ref "R67")
      (value "200k")
      (footprint "0402")
      (description "Resistor")
      (fields (field (name "Comment") "Res1") (field (name "PUBLISHER") "Altium Limited"))
      (libsource (lib "Miscellaneous Devices") (part "Res1"))
    )
    (comp (ref "R68")
      (value "200")
      (footprint "0402")
      (description "Resistor")
      (fields (field (name "Comment") "Res1") (field (name "PUBLISHER") "Altium Limited"))
      (libsource (lib "Miscellaneous Devices") (part "Res1"))
    )
    (comp (ref "R69")
      (value "200")
      (footprint "0402")
      (description "Resistor")
      (fields (field (name "Comment") "Res1") (field (name "PUBLISHER") "Altium Limited"))
      (libsource (lib "Miscellaneous Devices") (part "Res1"))
    )
    (comp (ref "R70")
      (value "200")
      (footprint "0402")
      (description "Resistor")
      (fields (field (name "Comment") "Res1") (field (name "PUBLISHER") "Altium Limited"))
      (libsource (lib "Miscellaneous Devices") (part "Res1"))
    )
    (comp (ref "R71")
      (value "200")
      (footprint "0402")
      (description "Resistor")
      (fields (field (name "Comment") "Res1") (field (name "PUBLISHER") "Altium Limited"))
      (libsource (lib "Miscellaneous Devices") (part "Res1"))
    )
    (comp (ref "R72")
      (value "200")
      (footprint "0402")
      (description "Resistor")
      (fields (field (name "Comment") "Res1") (field (name "PUBLISHER") "Altium Limited"))
      (libsource (lib "Miscellaneous Devices") (part "Res1"))
    )
    (comp (ref "R73")
      (value "200")
      (footprint "0402")
      (description "Resistor")
      (fields (field (name "Comment") "Res1") (field (name "PUBLISHER") "Altium Limited"))
      (libsource (lib "Miscellaneous Devices") (part "Res1"))
    )
    (comp (ref "R74")
      (value "200")
      (footprint "0402")
      (description "Resistor")
      (fields (field (name "Comment") "Res1") (field (name "PUBLISHER") "Altium Limited"))
      (libsource (lib "Miscellaneous Devices") (part "Res1"))
    )
    (comp (ref "R75")
      (value "200")
      (footprint "0402")
      (description "Resistor")
      (fields (field (name "Comment") "Res1") (field (name "PUBLISHER") "Altium Limited"))
      (libsource (lib "Miscellaneous Devices") (part "Res1"))
    )
    (comp (ref "R76")
      (value "200")
      (footprint "0402")
      (description "Resistor")
      (fields (field (name "Comment") "Res1") (field (name "PUBLISHER") "Altium Limited"))
      (libsource (lib "Miscellaneous Devices") (part "Res1"))
    )
    (comp (ref "R77")
      (value "200")
      (footprint "0402")
      (description "Resistor")
      (fields (field (name "Comment") "Res1") (field (name "PUBLISHER") "Altium Limited"))
      (libsource (lib "Miscellaneous Devices") (part "Res1"))
    )
    (comp (ref "R78")
      (value "200")
      (footprint "0402")
      (description "Resistor")
      (fields (field (name "Comment") "Res1") (field (name "PUBLISHER") "Altium Limited"))
      (libsource (lib "Miscellaneous Devices") (part "Res1"))
    )
    (comp (ref "R79")
      (value "200")
      (footprint "0402")
      (description "Resistor")
      (fields (field (name "Comment") "Res1") (field (name "PUBLISHER") "Altium Limited"))
      (libsource (lib "Miscellaneous Devices") (part "Res1"))
    )
    (comp (ref "R80")
      (value "200")
      (footprint "0402")
      (description "Resistor")
      (fields (field (name "Comment") "Res1") (field (name "PUBLISHER") "Altium Limited"))
      (libsource (lib "Miscellaneous Devices") (part "Res1"))
    )
    (comp (ref "R81")
      (value "200")
      (footprint "0402")
      (description "Resistor")
      (fields (field (name "Comment") "Res1") (field (name "PUBLISHER") "Altium Limited"))
      (libsource (lib "Miscellaneous Devices") (part "Res1"))
    )
    (comp (ref "R82")
      (value "200")
      (footprint "0402")
      (description "Resistor")
      (fields (field (name "Comment") "Res1") (field (name "PUBLISHER") "Altium Limited"))
      (libsource (lib "Miscellaneous Devices") (part "Res1"))
    )
    (comp (ref "R83")
      (value "200")
      (footprint "0402")
      (description "Resistor")
      (fields (field (name "Comment") "Res1") (field (name "PUBLISHER") "Altium Limited"))
      (libsource (lib "Miscellaneous Devices") (part "Res1"))
    )
    (comp (ref "R84")
      (value "200")
      (footprint "0402")
      (description "Resistor")
      (fields (field (name "Comment") "Res1") (field (name "PUBLISHER") "Altium Limited"))
      (libsource (lib "Miscellaneous Devices") (part "Res1"))
    )
    (comp (ref "R85")
      (value "200")
      (footprint "0402")
      (description "Resistor")
      (fields (field (name "Comment") "Res1") (field (name "PUBLISHER") "Altium Limited"))
      (libsource (lib "Miscellaneous Devices") (part "Res1"))
    )
    (comp (ref "R86")
      (value "200")
      (footprint "0402")
      (description "Resistor")
      (fields (field (name "Comment") "Res1") (field (name "PUBLISHER") "Altium Limited"))
      (libsource (lib "Miscellaneous Devices") (part "Res1"))
    )
    (comp (ref "R87")
      (value "200")
      (footprint "0402")
      (description "Resistor")
      (fields (field (name "Comment") "Res1") (field (name "PUBLISHER") "Altium Limited"))
      (libsource (lib "Miscellaneous Devices") (part "Res1"))
    )
    (comp (ref "R88")
      (value "200")
      (footprint "0402")
      (description "Resistor")
      (fields (field (name "Comment") "Res1") (field (name "PUBLISHER") "Altium Limited"))
      (libsource (lib "Miscellaneous Devices") (part "Res1"))
    )
    (comp (ref "R89")
      (value "200")
      (footprint "0402")
      (description "Resistor")
      (fields (field (name "Comment") "Res1") (field (name "PUBLISHER") "Altium Limited"))
      (libsource (lib "Miscellaneous Devices") (part "Res1"))
    )
    (comp (ref "R90")
      (value "200")
      (footprint "0402")
      (description "Resistor")
      (fields (field (name "Comment") "Res1") (field (name "PUBLISHER") "Altium Limited"))
      (libsource (lib "Miscellaneous Devices") (part "Res1"))
    )
    (comp (ref "R91")
      (value "200")
      (footprint "0402")
      (description "Resistor")
      (fields (field (name "Comment") "Res1") (field (name "PUBLISHER") "Altium Limited"))
      (libsource (lib "Miscellaneous Devices") (part "Res1"))
    )
    (comp (ref "R92")
      (value "200")
      (footprint "0402")
      (description "Resistor")
      (fields (field (name "Comment") "Res1") (field (name "PUBLISHER") "Altium Limited"))
      (libsource (lib "Miscellaneous Devices") (part "Res1"))
    )
    (comp (ref "R93")
      (value "200")
      (footprint "0402")
      (description "Resistor")
      (fields (field (name "Comment") "Res1") (field (name "PUBLISHER") "Altium Limited"))
      (libsource (lib "Miscellaneous Devices") (part "Res1"))
    )
    (comp (ref "R94")
      (value "200")
      (footprint "0402")
      (description "Resistor")
      (fields (field (name "Comment") "Res1") (field (name "PUBLISHER") "Altium Limited"))
      (libsource (lib "Miscellaneous Devices") (part "Res1"))
    )
    (comp (ref "R95")
      (value "200")
      (footprint "0402")
      (description "Resistor")
      (fields (field (name "Comment") "Res1") (field (name "PUBLISHER") "Altium Limited"))
      (libsource (lib "Miscellaneous Devices") (part "Res1"))
    )
    (comp (ref "R96")
      (value "200")
      (footprint "0402")
      (description "Resistor")
      (fields (field (name "Comment") "Res1") (field (name "PUBLISHER") "Altium Limited"))
      (libsource (lib "Miscellaneous Devices") (part "Res1"))
    )
    (comp (ref "R97")
      (value "200")
      (footprint "0402")
      (description "Resistor")
      (fields (field (name "Comment") "Res1") (field (name "PUBLISHER") "Altium Limited"))
      (libsource (lib "Miscellaneous Devices") (part "Res1"))
    )
    (comp (ref "R98")
      (value "200")
      (footprint "0402")
      (description "Resistor")
      (fields (field (name "Comment") "Res1") (field (name "PUBLISHER") "Altium Limited"))
      (libsource (lib "Miscellaneous Devices") (part "Res1"))
    )
    (comp (ref "R99")
      (value "200")
      (footprint "0402")
      (description "Resistor")
      (fields (field (name "Comment") "Res1") (field (name "PUBLISHER") "Altium Limited"))
      (libsource (lib "Miscellaneous Devices") (part "Res1"))
    )
    (comp (ref "R100")
      (value "200")
      (footprint "0402")
      (description "Resistor")
      (fields (field (name "Comment") "Res1") (field (name "PUBLISHER") "Altium Limited"))
      (libsource (lib "Miscellaneous Devices") (part "Res1"))
    )
    (comp (ref "R101")
      (value "200")
      (footprint "0402")
      (description "Resistor")
      (fields (field (name "Comment") "Res1") (field (name "PUBLISHER") "Altium Limited"))
      (libsource (lib "Miscellaneous Devices") (part "Res1"))
    )
    (comp (ref "R102")
      (value "200")
      (footprint "0402")
      (description "Resistor")
      (fields (field (name "Comment") "Res1") (field (name "PUBLISHER") "Altium Limited"))
      (libsource (lib "Miscellaneous Devices") (part "Res1"))
    )
    (comp (ref "R103")
      (value "200")
      (footprint "0402")
      (description "Resistor")
      (fields (field (name "Comment") "Res1") (field (name "PUBLISHER") "Altium Limited"))
      (libsource (lib "Miscellaneous Devices") (part "Res1"))
    )
    (comp (ref "R104")
      (value "200")
      (footprint "0402")
      (description "Resistor")
      (fields (field (name "Comment") "Res1") (field (name "PUBLISHER") "Altium Limited"))
      (libsource (lib "Miscellaneous Devices") (part "Res1"))
    )
    (comp (ref "R105")
      (value "200")
      (footprint "0402")
      (description "Resistor")
      (fields (field (name "Comment") "Res1") (field (name "PUBLISHER") "Altium Limited"))
      (libsource (lib "Miscellaneous Devices") (part "Res1"))
    )
    (comp (ref "R106")
      (value "200")
      (footprint "0402")
      (description "Resistor")
      (fields (field (name "Comment") "Res1") (field (name "PUBLISHER") "Altium Limited"))
      (libsource (lib "Miscellaneous Devices") (part "Res1"))
    )
    (comp (ref "R107")
      (value "200")
      (footprint "0402")
      (description "Resistor")
      (fields (field (name "Comment") "Res1") (field (name "PUBLISHER") "Altium Limited"))
      (libsource (lib "Miscellaneous Devices") (part "Res1"))
    )
    (comp (ref "R108")
      (value "200")
      (footprint "0402")
      (description "Resistor")
      (fields (field (name "Comment") "Res1") (field (name "PUBLISHER") "Altium Limited"))
      (libsource (lib "Miscellaneous Devices") (part "Res1"))
    )
    (comp (ref "R109")
      (value "200")
      (footprint "0402")
      (description "Resistor")
      (fields (field (name "Comment") "Res1") (field (name "PUBLISHER") "Altium Limited"))
      (libsource (lib "Miscellaneous Devices") (part "Res1"))
    )
    (comp (ref "R110")
      (value "200")
      (footprint "0402")
      (description "Resistor")
      (fields (field (name "Comment") "Res1") (field (name "PUBLISHER") "Altium Limited"))
      (libsource (lib "Miscellaneous Devices") (part "Res1"))
    )
    (comp (ref "R111")
      (value "200")
      (footprint "0402")
      (description "Resistor")
      (fields (field (name "Comment") "Res1") (field (name "PUBLISHER") "Altium Limited"))
      (libsource (lib "Miscellaneous Devices") (part "Res1"))
    )
    (comp (ref "R112")
      (value "200")
      (footprint "0402")
      (description "Resistor")
      (fields (field (name "Comment") "Res1") (field (name "PUBLISHER") "Altium Limited"))
      (libsource (lib "Miscellaneous Devices") (part "Res1"))
    )
    (comp (ref "R113")
      (value "200")
      (footprint "0402")
      (description "Resistor")
      (fields (field (name "Comment") "Res1") (field (name "PUBLISHER") "Altium Limited"))
      (libsource (lib "Miscellaneous Devices") (part "Res1"))
    )
    (comp (ref "R114")
      (value "200")
      (footprint "0402")
      (description "Resistor")
      (fields (field (name "Comment") "Res1") (field (name "PUBLISHER") "Altium Limited"))
      (libsource (lib "Miscellaneous Devices") (part "Res1"))
    )
    (comp (ref "R115")
      (value "200")
      (footprint "0402")
      (description "Resistor")
      (fields (field (name "Comment") "Res1") (field (name "PUBLISHER") "Altium Limited"))
      (libsource (lib "Miscellaneous Devices") (part "Res1"))
    )
    (comp (ref "R116")
      (value "200")
      (footprint "0402")
      (description "Resistor")
      (fields (field (name "Comment") "Res1") (field (name "PUBLISHER") "Altium Limited"))
      (libsource (lib "Miscellaneous Devices") (part "Res1"))
    )
    (comp (ref "R117")
      (value "200")
      (footprint "0402")
      (description "Resistor")
      (fields (field (name "Comment") "Res1") (field (name "PUBLISHER") "Altium Limited"))
      (libsource (lib "Miscellaneous Devices") (part "Res1"))
    )
    (comp (ref "R118")
      (value "200")
      (footprint "0402")
      (description "Resistor")
      (fields (field (name "Comment") "Res1") (field (name "PUBLISHER") "Altium Limited"))
      (libsource (lib "Miscellaneous Devices") (part "Res1"))
    )
    (comp (ref "R119")
      (value "200")
      (footprint "0402")
      (description "Resistor")
      (fields (field (name "Comment") "Res1") (field (name "PUBLISHER") "Altium Limited"))
      (libsource (lib "Miscellaneous Devices") (part "Res1"))
    )
    (comp (ref "R120")
      (value "200")
      (footprint "0402")
      (description "Resistor")
      (fields (field (name "Comment") "Res1") (field (name "PUBLISHER") "Altium Limited"))
      (libsource (lib "Miscellaneous Devices") (part "Res1"))
    )
    (comp (ref "R121")
      (value "200")
      (footprint "0402")
      (description "Resistor")
      (fields (field (name "Comment") "Res1") (field (name "PUBLISHER") "Altium Limited"))
      (libsource (lib "Miscellaneous Devices") (part "Res1"))
    )
    (comp (ref "R122")
      (value "200")
      (footprint "0402")
      (description "Resistor")
      (fields (field (name "Comment") "Res1") (field (name "PUBLISHER") "Altium Limited"))
      (libsource (lib "Miscellaneous Devices") (part "Res1"))
    )
    (comp (ref "R123")
      (value "200")
      (footprint "0402")
      (description "Resistor")
      (fields (field (name "Comment") "Res1") (field (name "PUBLISHER") "Altium Limited"))
      (libsource (lib "Miscellaneous Devices") (part "Res1"))
    )
    (comp (ref "R124")
      (value "200")
      (footprint "0402")
      (description "Resistor")
      (fields (field (name "Comment") "Res1") (field (name "PUBLISHER") "Altium Limited"))
      (libsource (lib "Miscellaneous Devices") (part "Res1"))
    )
    (comp (ref "R125")
      (value "200")
      (footprint "0402")
      (description "Resistor")
      (fields (field (name "Comment") "Res1") (field (name "PUBLISHER") "Altium Limited"))
      (libsource (lib "Miscellaneous Devices") (part "Res1"))
    )
    (comp (ref "R126")
      (value "200")
      (footprint "0402")
      (description "Resistor")
      (fields (field (name "Comment") "Res1") (field (name "PUBLISHER") "Altium Limited"))
      (libsource (lib "Miscellaneous Devices") (part "Res1"))
    )
    (comp (ref "R127")
      (value "120")
      (footprint "0402")
      (description "贴片电阻")
      (fields (field (name "Comment") "Res1") (field (name "PUBLISHER") "Altium Limited"))
      (libsource (lib "k7_ext") (part "Res1"))
    )
    (comp (ref "R128")
      (value "10k")
      (footprint "0402")
      (description "Resistor")
      (fields (field (name "Comment") "Res1") (field (name "PUBLISHER") "Altium Limited"))
      (libsource (lib "Miscellaneous Devices") (part "Res1"))
    )
    (comp (ref "R129")
      (value "10k")
      (footprint "0402")
      (description "Resistor")
      (fields (field (name "Comment") "Res1") (field (name "PUBLISHER") "Altium Limited"))
      (libsource (lib "Miscellaneous Devices") (part "Res1"))
    )
    (comp (ref "R130")
      (value "10k")
      (footprint "0402")
      (description "Resistor")
      (fields (field (name "Comment") "Res1") (field (name "PUBLISHER") "Altium Limited"))
      (libsource (lib "Miscellaneous Devices") (part "Res1"))
    )
    (comp (ref "R131")
      (value "10k")
      (footprint "0402")
      (description "Resistor")
      (fields (field (name "Comment") "Res1") (field (name "PUBLISHER") "Altium Limited"))
      (libsource (lib "Miscellaneous Devices") (part "Res1"))
    )
    (comp (ref "R132")
      (value "10k")
      (footprint "0402")
      (description "Resistor")
      (fields (field (name "Comment") "Res1") (field (name "PUBLISHER") "Altium Limited"))
      (libsource (lib "Miscellaneous Devices") (part "Res1"))
    )
    (comp (ref "R133")
      (value "10k")
      (footprint "0402")
      (description "Resistor")
      (fields (field (name "Comment") "Res1") (field (name "PUBLISHER") "Altium Limited"))
      (libsource (lib "Miscellaneous Devices") (part "Res1"))
    )
    (comp (ref "R134")
      (value "10k")
      (footprint "0402")
      (description "Resistor")
      (fields (field (name "Comment") "Res1") (field (name "PUBLISHER") "Altium Limited"))
      (libsource (lib "Miscellaneous Devices") (part "Res1"))
    )
    (comp (ref "R135")
      (value "10k")
      (footprint "0402")
      (description "Resistor")
      (fields (field (name "Comment") "Res1") (field (name "PUBLISHER") "Altium Limited"))
      (libsource (lib "Miscellaneous Devices") (part "Res1"))
    )
    (comp (ref "R136")
      (value "10k")
      (footprint "0402")
      (description "Resistor")
      (fields (field (name "Comment") "Res1") (field (name "PUBLISHER") "Altium Limited"))
      (libsource (lib "Miscellaneous Devices") (part "Res1"))
    )
    (comp (ref "R137")
      (value "10k")
      (footprint "0402")
      (description "Resistor")
      (fields (field (name "Comment") "Res1") (field (name "PUBLISHER") "Altium Limited"))
      (libsource (lib "Miscellaneous Devices") (part "Res1"))
    )
    (comp (ref "R138")
      (value "20k")
      (footprint "0402")
      (description "Resistor")
      (fields (field (name "Comment") "Res1") (field (name "PUBLISHER") "Altium Limited"))
      (libsource (lib "Miscellaneous Devices") (part "Res1"))
    )
    (comp (ref "R139")
      (value "20k")
      (footprint "0402")
      (description "Resistor")
      (fields (field (name "Comment") "Res1") (field (name "PUBLISHER") "Altium Limited"))
      (libsource (lib "Miscellaneous Devices") (part "Res1"))
    )
    (comp (ref "R140")
      (value "120")
      (footprint "0402")
      (description "贴片电阻")
      (fields (field (name "Comment") "Res1") (field (name "PUBLISHER") "Altium Limited"))
      (libsource (lib "k7_ext") (part "Res1"))
    )
    (comp (ref "RST_n1")
      (value "SW-PB")
      (footprint "SPST-2")
      (description "Switch")
      (fields (field (name "PUBLISHER") "Altium Limited"))
      (libsource (lib "Miscellaneous Devices") (part "SW-PB"))
    )
    (comp (ref "S1")
      (value "SW-DPDT")
      (footprint "DPDT-6")
      (description "Double-Pole, Double-Throw Switch")
      (fields (field (name "PUBLISHER") "Altium Limited"))
      (libsource (lib "Miscellaneous Devices") (part "SW-DPDT"))
    )
    (comp (ref "U1")
      (value "SN74TVC16222A")
      (footprint "TSSOP50P810X120-48N")
      (libsource (lib "k7_ext") (part "SN74TVC16222A"))
    )
    (comp (ref "U2")
      (value "SN74TVC16222A")
      (footprint "TSSOP50P810X120-48N")
      (libsource (lib "k7_ext") (part "SN74TVC16222A"))
    )
    (comp (ref "U3")
      (value "SN74TVC16222A")
      (footprint "TSSOP50P810X120-48N")
      (libsource (lib "k7_ext") (part "SN74TVC16222A"))
    )
    (comp (ref "U4")
      (value "EP4CE6/10_FPGACore")
      (footprint "EP4CE6/10_FPGACore")
      (libsource (lib "VIP_Board_Mini") (part "EP4CE6/10_FPGACore"))
    )
    (comp (ref "U5")
      (value "SN74TVC16222A")
      (footprint "TSSOP50P810X120-48N")
      (libsource (lib "k7_ext") (part "SN74TVC16222A"))
    )
    (comp (ref "U6")
      (value "SN74TVC16222A")
      (footprint "TSSOP50P810X120-48N")
      (libsource (lib "k7_ext") (part "SN74TVC16222A"))
    )
    (comp (ref "U7")
      (value "SN74TVC16222A")
      (footprint "TSSOP50P810X120-48N")
      (libsource (lib "k7_ext") (part "SN74TVC16222A"))
    )
    (comp (ref "U8")
      (value "W25QXX")
      (footprint "SOIC8_W")
      (description "SPI FLASH")
      (fields (field (name "MEMORY") "64M bit"))
      (libsource (lib "k7_ext") (part "W25QXX"))
    )
    (comp (ref "U9")
      (value "Intel386sx")
      (footprint "BQFP-i386-SX")
      (description "CPU-80386")
      (libsource (lib "k7_ext") (part "Intel386sx"))
    )
    (comp (ref "U10")
      (value "IS82C37A")
      (footprint "PLCC-44-IC-SOCKET")
      (description "DMA控制器")
      (libsource (lib "k7_ext") (part "IS82C37A"))
    )
    (comp (ref "U11")
      (value "AS6C8016")
      (footprint "TSOP80P1160X120-44N")
      (libsource (lib "k7_ext") (part "AS6C8016"))
    )
    (comp (ref "U12")
      (value "ASM1117")
      (footprint "SOT-223")
      (description "3.3V稳压芯片")
      (libsource (lib "k7_ext") (part "ASM1117"))
    )
    (comp (ref "U13")
      (value "P8259A")
      (footprint "DIP28")
      (description "中断控制器")
      (libsource (lib "k7_ext") (part "P8259A"))
    )
    (comp (ref "U14")
      (value "CS82C54")
      (footprint "PLCC-28-IC-SOCKET")
      (description "Timer 定时器")
      (libsource (lib "k7_ext") (part "CS82C54"))
    )
  )
  (nets
    (net (code "1") (name "/CONF_DONE") (class "Default")
      (node (ref "R127") (pin "1") (pinfunction "1_1") (pintype "passive"))
      (node (ref "U1") (pin "18") (pinfunction "A17_18") (pintype "passive"))
      (node (ref "U4") (pin "105") (pinfunction "CONF_DONE_105") (pintype "bidirectional"))
    )
    (net (code "2") (name "/CPU_A1") (class "Default")
      (node (ref "R4") (pin "1") (pinfunction "1_1") (pintype "passive"))
      (node (ref "U1") (pin "44") (pinfunction "B4_44") (pintype "passive"))
      (node (ref "U11") (pin "5") (pinfunction "A0_5") (pintype "passive"))
      (node (ref "U9") (pin "18") (pinfunction "A1_18") (pintype "passive"))
    )
    (net (code "3") (name "/CPU_A2") (class "Default")
      (node (ref "R7") (pin "1") (pinfunction "1_1") (pintype "passive"))
      (node (ref "U1") (pin "43") (pinfunction "B5_43") (pintype "passive"))
      (node (ref "U11") (pin "4") (pinfunction "A1_4") (pintype "passive"))
      (node (ref "U9") (pin "51") (pinfunction "A2_51") (pintype "passive"))
    )
    (net (code "4") (name "/CPU_A3") (class "Default")
      (node (ref "R10") (pin "1") (pinfunction "1_1") (pintype "passive"))
      (node (ref "U1") (pin "42") (pinfunction "B6_42") (pintype "passive"))
      (node (ref "U11") (pin "3") (pinfunction "A2_3") (pintype "passive"))
      (node (ref "U9") (pin "52") (pinfunction "A3_52") (pintype "passive"))
    )
    (net (code "5") (name "/CPU_A4") (class "Default")
      (node (ref "R13") (pin "1") (pinfunction "1_1") (pintype "passive"))
      (node (ref "U1") (pin "41") (pinfunction "B7_41") (pintype "passive"))
      (node (ref "U11") (pin "2") (pinfunction "A3_2") (pintype "passive"))
      (node (ref "U9") (pin "53") (pinfunction "A4_53") (pintype "passive"))
    )
    (net (code "6") (name "/CPU_A5") (class "Default")
      (node (ref "R16") (pin "1") (pinfunction "1_1") (pintype "passive"))
      (node (ref "U1") (pin "40") (pinfunction "B8_40") (pintype "passive"))
      (node (ref "U11") (pin "1") (pinfunction "A4_1") (pintype "passive"))
      (node (ref "U9") (pin "54") (pinfunction "A5_54") (pintype "passive"))
    )
    (net (code "7") (name "/CPU_A6") (class "Default")
      (node (ref "R19") (pin "1") (pinfunction "1_1") (pintype "passive"))
      (node (ref "U1") (pin "39") (pinfunction "B9_39") (pintype "passive"))
      (node (ref "U11") (pin "44") (pinfunction "A5_44") (pintype "passive"))
      (node (ref "U9") (pin "55") (pinfunction "A6_55") (pintype "passive"))
    )
    (net (code "8") (name "/CPU_A7") (class "Default")
      (node (ref "R22") (pin "1") (pinfunction "1_1") (pintype "passive"))
      (node (ref "U1") (pin "38") (pinfunction "B10_38") (pintype "passive"))
      (node (ref "U11") (pin "43") (pinfunction "A6_43") (pintype "passive"))
      (node (ref "U9") (pin "56") (pinfunction "A7_56") (pintype "passive"))
    )
    (net (code "9") (name "/CPU_A8") (class "Default")
      (node (ref "R25") (pin "1") (pinfunction "1_1") (pintype "passive"))
      (node (ref "U1") (pin "37") (pinfunction "B11_37") (pintype "passive"))
      (node (ref "U11") (pin "42") (pinfunction "A7_42") (pintype "passive"))
      (node (ref "U9") (pin "58") (pinfunction "A8_58") (pintype "passive"))
    )
    (net (code "10") (name "/CPU_A9") (class "Default")
      (node (ref "R28") (pin "1") (pinfunction "1_1") (pintype "passive"))
      (node (ref "U1") (pin "36") (pinfunction "B12_36") (pintype "passive"))
      (node (ref "U11") (pin "28") (pinfunction "A8_28") (pintype "passive"))
      (node (ref "U9") (pin "59") (pinfunction "A9_59") (pintype "passive"))
    )
    (net (code "11") (name "/CPU_A10") (class "Default")
      (node (ref "R31") (pin "1") (pinfunction "1_1") (pintype "passive"))
      (node (ref "U1") (pin "35") (pinfunction "B13_35") (pintype "passive"))
      (node (ref "U11") (pin "27") (pinfunction "A9_27") (pintype "passive"))
      (node (ref "U9") (pin "60") (pinfunction "A10_60") (pintype "passive"))
    )
    (net (code "12") (name "/CPU_A11") (class "Default")
      (node (ref "R34") (pin "1") (pinfunction "1_1") (pintype "passive"))
      (node (ref "U1") (pin "34") (pinfunction "B14_34") (pintype "passive"))
      (node (ref "U11") (pin "26") (pinfunction "A10_26") (pintype "passive"))
      (node (ref "U9") (pin "61") (pinfunction "A11_61") (pintype "passive"))
    )
    (net (code "13") (name "/CPU_A12") (class "Default")
      (node (ref "R37") (pin "1") (pinfunction "1_1") (pintype "passive"))
      (node (ref "U1") (pin "33") (pinfunction "B15_33") (pintype "passive"))
      (node (ref "U11") (pin "25") (pinfunction "A11_25") (pintype "passive"))
      (node (ref "U9") (pin "62") (pinfunction "A12_62") (pintype "passive"))
    )
    (net (code "14") (name "/CPU_A13") (class "Default")
      (node (ref "R40") (pin "1") (pinfunction "1_1") (pintype "passive"))
      (node (ref "U1") (pin "32") (pinfunction "B16_32") (pintype "passive"))
      (node (ref "U11") (pin "24") (pinfunction "A12_24") (pintype "passive"))
      (node (ref "U9") (pin "64") (pinfunction "A13_64") (pintype "passive"))
    )
    (net (code "15") (name "/CPU_A14") (class "Default")
      (node (ref "R43") (pin "1") (pinfunction "1_1") (pintype "passive"))
      (node (ref "U1") (pin "31") (pinfunction "B17_31") (pintype "passive"))
      (node (ref "U11") (pin "23") (pinfunction "A13_23") (pintype "passive"))
      (node (ref "U9") (pin "65") (pinfunction "A14_65") (pintype "passive"))
    )
    (net (code "16") (name "/CPU_A15") (class "Default")
      (node (ref "R46") (pin "1") (pinfunction "1_1") (pintype "passive"))
      (node (ref "U1") (pin "30") (pinfunction "B18_30") (pintype "passive"))
      (node (ref "U11") (pin "22") (pinfunction "A14_22") (pintype "passive"))
      (node (ref "U9") (pin "66") (pinfunction "A15_66") (pintype "passive"))
    )
    (net (code "17") (name "/CPU_A16") (class "Default")
      (node (ref "R49") (pin "1") (pinfunction "1_1") (pintype "passive"))
      (node (ref "U1") (pin "29") (pinfunction "B19_29") (pintype "passive"))
      (node (ref "U11") (pin "21") (pinfunction "A15_21") (pintype "passive"))
      (node (ref "U9") (pin "70") (pinfunction "A16_70") (pintype "passive"))
    )
    (net (code "18") (name "/CPU_A17") (class "Default")
      (node (ref "R52") (pin "1") (pinfunction "1_1") (pintype "passive"))
      (node (ref "U1") (pin "28") (pinfunction "B20_28") (pintype "passive"))
      (node (ref "U11") (pin "20") (pinfunction "A16_20") (pintype "passive"))
      (node (ref "U9") (pin "72") (pinfunction "A17_72") (pintype "passive"))
    )
    (net (code "19") (name "/CPU_A18") (class "Default")
      (node (ref "R55") (pin "1") (pinfunction "1_1") (pintype "passive"))
      (node (ref "U1") (pin "27") (pinfunction "B21_27") (pintype "passive"))
      (node (ref "U11") (pin "19") (pinfunction "A17_19") (pintype "passive"))
      (node (ref "U9") (pin "73") (pinfunction "A18_73") (pintype "passive"))
    )
    (net (code "20") (name "/CPU_A19") (class "Default")
      (node (ref "R58") (pin "1") (pinfunction "1_1") (pintype "passive"))
      (node (ref "U1") (pin "26") (pinfunction "B22_26") (pintype "passive"))
      (node (ref "U11") (pin "18") (pinfunction "A18_18") (pintype "passive"))
      (node (ref "U9") (pin "74") (pinfunction "A19_74") (pintype "passive"))
    )
    (net (code "21") (name "/CPU_A20") (class "Default")
      (node (ref "R61") (pin "1") (pinfunction "1_1") (pintype "passive"))
      (node (ref "U1") (pin "25") (pinfunction "B23_25") (pintype "passive"))
      (node (ref "U9") (pin "75") (pinfunction "A20_75") (pintype "passive"))
    )
    (net (code "22") (name "/CPU_A21") (class "Default")
      (node (ref "R20") (pin "1") (pinfunction "1_1") (pintype "passive"))
      (node (ref "U2") (pin "39") (pinfunction "B9_39") (pintype "passive"))
      (node (ref "U9") (pin "76") (pinfunction "A21_76") (pintype "passive"))
    )
    (net (code "23") (name "/CPU_A22") (class "Default")
      (node (ref "R23") (pin "1") (pinfunction "1_1") (pintype "passive"))
      (node (ref "U2") (pin "38") (pinfunction "B10_38") (pintype "passive"))
      (node (ref "U9") (pin "79") (pinfunction "A22_79") (pintype "passive"))
    )
    (net (code "24") (name "/CPU_A23") (class "Default")
      (node (ref "R26") (pin "1") (pinfunction "1_1") (pintype "passive"))
      (node (ref "U2") (pin "37") (pinfunction "B11_37") (pintype "passive"))
      (node (ref "U9") (pin "80") (pinfunction "A23_80") (pintype "passive"))
    )
    (net (code "25") (name "/CPU_ADS#") (class "Default")
      (node (ref "R18") (pin "1") (pinfunction "1_1") (pintype "passive"))
      (node (ref "U3") (pin "40") (pinfunction "B8_40") (pintype "passive"))
      (node (ref "U9") (pin "16") (pinfunction "ADS#_16") (pintype "passive"))
    )
    (net (code "26") (name "/CPU_BHE#") (class "Default")
      (node (ref "R21") (pin "1") (pinfunction "1_1") (pintype "passive"))
      (node (ref "U3") (pin "39") (pinfunction "B9_39") (pintype "passive"))
      (node (ref "U9") (pin "19") (pinfunction "BHE#_19") (pintype "passive"))
    )
    (net (code "27") (name "/CPU_BLE#") (class "Default")
      (node (ref "R24") (pin "1") (pinfunction "1_1") (pintype "passive"))
      (node (ref "U3") (pin "38") (pinfunction "B10_38") (pintype "passive"))
      (node (ref "U9") (pin "17") (pinfunction "BLE#_17") (pintype "passive"))
    )
    (net (code "28") (name "/CPU_BUSY#") (class "Default")
      (node (ref "R139") (pin "1") (pinfunction "1_1") (pintype "passive"))
      (node (ref "U9") (pin "34") (pinfunction "BUSY#_34") (pintype "passive"))
    )
    (net (code "29") (name "/CPU_CLK2") (class "Default")
      (node (ref "R27") (pin "1") (pinfunction "1_1") (pintype "passive"))
      (node (ref "U3") (pin "37") (pinfunction "B11_37") (pintype "passive"))
      (node (ref "U9") (pin "15") (pinfunction "CLK2_15") (pintype "passive"))
    )
    (net (code "30") (name "/CPU_D0") (class "Default")
      (node (ref "R29") (pin "1") (pinfunction "1_1") (pintype "passive"))
      (node (ref "U10") (pin "34") (pinfunction "DB0_34") (pintype "passive"))
      (node (ref "U11") (pin "7") (pinfunction "DQ0_7") (pintype "passive"))
      (node (ref "U13") (pin "11") (pinfunction "D0_11") (pintype "passive"))
      (node (ref "U14") (pin "9") (pinfunction "D0_9") (pintype "passive"))
      (node (ref "U2") (pin "36") (pinfunction "B12_36") (pintype "passive"))
      (node (ref "U9") (pin "1") (pinfunction "D0_1") (pintype "passive"))
    )
    (net (code "31") (name "/CPU_D1") (class "Default")
      (node (ref "R32") (pin "1") (pinfunction "1_1") (pintype "passive"))
      (node (ref "U10") (pin "33") (pinfunction "DB1_33") (pintype "passive"))
      (node (ref "U11") (pin "8") (pinfunction "DQ1_8") (pintype "passive"))
      (node (ref "U13") (pin "10") (pinfunction "D1_10") (pintype "passive"))
      (node (ref "U14") (pin "8") (pinfunction "D1_8") (pintype "passive"))
      (node (ref "U2") (pin "35") (pinfunction "B13_35") (pintype "passive"))
      (node (ref "U9") (pin "100") (pinfunction "D1_100") (pintype "passive"))
    )
    (net (code "32") (name "/CPU_D2") (class "Default")
      (node (ref "R35") (pin "1") (pinfunction "1_1") (pintype "passive"))
      (node (ref "U10") (pin "32") (pinfunction "DB2_32") (pintype "passive"))
      (node (ref "U11") (pin "9") (pinfunction "DQ2_9") (pintype "passive"))
      (node (ref "U13") (pin "9") (pinfunction "D2_9") (pintype "passive"))
      (node (ref "U14") (pin "7") (pinfunction "D2_7") (pintype "passive"))
      (node (ref "U2") (pin "34") (pinfunction "B14_34") (pintype "passive"))
      (node (ref "U9") (pin "99") (pinfunction "D2_99") (pintype "passive"))
    )
    (net (code "33") (name "/CPU_D3") (class "Default")
      (node (ref "R38") (pin "1") (pinfunction "1_1") (pintype "passive"))
      (node (ref "U10") (pin "31") (pinfunction "DB3_31") (pintype "passive"))
      (node (ref "U11") (pin "10") (pinfunction "DQ3_10") (pintype "passive"))
      (node (ref "U13") (pin "8") (pinfunction "D3_8") (pintype "passive"))
      (node (ref "U14") (pin "6") (pinfunction "D3_6") (pintype "passive"))
      (node (ref "U2") (pin "33") (pinfunction "B15_33") (pintype "passive"))
      (node (ref "U9") (pin "96") (pinfunction "D3_96") (pintype "passive"))
    )
    (net (code "34") (name "/CPU_D4") (class "Default")
      (node (ref "R41") (pin "1") (pinfunction "1_1") (pintype "passive"))
      (node (ref "U10") (pin "30") (pinfunction "DB4_30") (pintype "passive"))
      (node (ref "U11") (pin "13") (pinfunction "DQ4_13") (pintype "passive"))
      (node (ref "U13") (pin "7") (pinfunction "D4_7") (pintype "passive"))
      (node (ref "U14") (pin "5") (pinfunction "D4_5") (pintype "passive"))
      (node (ref "U2") (pin "32") (pinfunction "B16_32") (pintype "passive"))
      (node (ref "U9") (pin "95") (pinfunction "D4_95") (pintype "passive"))
    )
    (net (code "35") (name "/CPU_D5") (class "Default")
      (node (ref "R44") (pin "1") (pinfunction "1_1") (pintype "passive"))
      (node (ref "U10") (pin "26") (pinfunction "DB5_26") (pintype "passive"))
      (node (ref "U11") (pin "14") (pinfunction "DQ5_14") (pintype "passive"))
      (node (ref "U13") (pin "6") (pinfunction "D5_6") (pintype "passive"))
      (node (ref "U14") (pin "4") (pinfunction "D5_4") (pintype "passive"))
      (node (ref "U2") (pin "31") (pinfunction "B17_31") (pintype "passive"))
      (node (ref "U9") (pin "94") (pinfunction "D5_94") (pintype "passive"))
    )
    (net (code "36") (name "/CPU_D6") (class "Default")
      (node (ref "R47") (pin "1") (pinfunction "1_1") (pintype "passive"))
      (node (ref "U10") (pin "25") (pinfunction "DB6_25") (pintype "passive"))
      (node (ref "U11") (pin "15") (pinfunction "DQ6_15") (pintype "passive"))
      (node (ref "U13") (pin "5") (pinfunction "D6_5") (pintype "passive"))
      (node (ref "U14") (pin "3") (pinfunction "D6_3") (pintype "passive"))
      (node (ref "U2") (pin "30") (pinfunction "B18_30") (pintype "passive"))
      (node (ref "U9") (pin "93") (pinfunction "D6_93") (pintype "passive"))
    )
    (net (code "37") (name "/CPU_D7") (class "Default")
      (node (ref "R50") (pin "1") (pinfunction "1_1") (pintype "passive"))
      (node (ref "U10") (pin "24") (pinfunction "DB7_24") (pintype "passive"))
      (node (ref "U11") (pin "16") (pinfunction "DQ7_16") (pintype "passive"))
      (node (ref "U13") (pin "4") (pinfunction "D7_4") (pintype "passive"))
      (node (ref "U14") (pin "2") (pinfunction "D7_2") (pintype "passive"))
      (node (ref "U2") (pin "29") (pinfunction "B19_29") (pintype "passive"))
      (node (ref "U9") (pin "92") (pinfunction "D7_92") (pintype "passive"))
    )
    (net (code "38") (name "/CPU_D8") (class "Default")
      (node (ref "R53") (pin "1") (pinfunction "1_1") (pintype "passive"))
      (node (ref "U11") (pin "29") (pinfunction "DQ8_29") (pintype "passive"))
      (node (ref "U2") (pin "28") (pinfunction "B20_28") (pintype "passive"))
      (node (ref "U9") (pin "90") (pinfunction "D8_90") (pintype "passive"))
    )
    (net (code "39") (name "/CPU_D9") (class "Default")
      (node (ref "R56") (pin "1") (pinfunction "1_1") (pintype "passive"))
      (node (ref "U11") (pin "30") (pinfunction "DQ9_30") (pintype "passive"))
      (node (ref "U2") (pin "27") (pinfunction "B21_27") (pintype "passive"))
      (node (ref "U9") (pin "89") (pinfunction "D9_89") (pintype "passive"))
    )
    (net (code "40") (name "/CPU_D10") (class "Default")
      (node (ref "R59") (pin "1") (pinfunction "1_1") (pintype "passive"))
      (node (ref "U11") (pin "31") (pinfunction "DQ10_31") (pintype "passive"))
      (node (ref "U2") (pin "26") (pinfunction "B22_26") (pintype "passive"))
      (node (ref "U9") (pin "88") (pinfunction "D10_88") (pintype "passive"))
    )
    (net (code "41") (name "/CPU_D11") (class "Default")
      (node (ref "R62") (pin "1") (pinfunction "1_1") (pintype "passive"))
      (node (ref "U11") (pin "32") (pinfunction "DQ11_32") (pintype "passive"))
      (node (ref "U2") (pin "25") (pinfunction "B23_25") (pintype "passive"))
      (node (ref "U9") (pin "87") (pinfunction "D11_87") (pintype "passive"))
    )
    (net (code "42") (name "/CPU_D12") (class "Default")
      (node (ref "R6") (pin "1") (pinfunction "1_1") (pintype "passive"))
      (node (ref "U11") (pin "35") (pinfunction "DQ12_35") (pintype "passive"))
      (node (ref "U3") (pin "44") (pinfunction "B4_44") (pintype "passive"))
      (node (ref "U9") (pin "86") (pinfunction "D12_86") (pintype "passive"))
    )
    (net (code "43") (name "/CPU_D13") (class "Default")
      (node (ref "R9") (pin "1") (pinfunction "1_1") (pintype "passive"))
      (node (ref "U11") (pin "36") (pinfunction "DQ13_36") (pintype "passive"))
      (node (ref "U3") (pin "43") (pinfunction "B5_43") (pintype "passive"))
      (node (ref "U9") (pin "83") (pinfunction "D13_83") (pintype "passive"))
    )
    (net (code "44") (name "/CPU_D14") (class "Default")
      (node (ref "R12") (pin "1") (pinfunction "1_1") (pintype "passive"))
      (node (ref "U11") (pin "37") (pinfunction "DQ14_37") (pintype "passive"))
      (node (ref "U3") (pin "42") (pinfunction "B6_42") (pintype "passive"))
      (node (ref "U9") (pin "82") (pinfunction "D14_82") (pintype "passive"))
    )
    (net (code "45") (name "/CPU_D15") (class "Default")
      (node (ref "R15") (pin "1") (pinfunction "1_1") (pintype "passive"))
      (node (ref "U11") (pin "38") (pinfunction "DQ15_38") (pintype "passive"))
      (node (ref "U3") (pin "41") (pinfunction "B7_41") (pintype "passive"))
      (node (ref "U9") (pin "81") (pinfunction "D15_81") (pintype "passive"))
    )
    (net (code "46") (name "/CPU_D{slash}C#") (class "Default")
      (node (ref "R30") (pin "1") (pinfunction "1_1") (pintype "passive"))
      (node (ref "U3") (pin "36") (pinfunction "B12_36") (pintype "passive"))
      (node (ref "U9") (pin "24") (pinfunction "D/C#_24") (pintype "passive"))
    )
    (net (code "47") (name "/CPU_ERROR#") (class "Default")
      (node (ref "R138") (pin "1") (pinfunction "1_1") (pintype "passive"))
      (node (ref "U9") (pin "36") (pinfunction "ERROR#_36") (pintype "passive"))
    )
    (net (code "48") (name "/CPU_FLT#") (class "Default")
      (node (ref "R33") (pin "1") (pinfunction "1_1") (pintype "passive"))
      (node (ref "U3") (pin "35") (pinfunction "B13_35") (pintype "passive"))
      (node (ref "U9") (pin "28") (pinfunction "FLT#_28") (pintype "passive"))
    )
    (net (code "49") (name "/CPU_HLDA") (class "Default")
      (node (ref "R36") (pin "1") (pinfunction "1_1") (pintype "passive"))
      (node (ref "U3") (pin "34") (pinfunction "B14_34") (pintype "passive"))
      (node (ref "U9") (pin "3") (pinfunction "HLDA_3") (pintype "passive"))
    )
    (net (code "50") (name "/CPU_HOLD") (class "Default")
      (node (ref "R39") (pin "1") (pinfunction "1_1") (pintype "passive"))
      (node (ref "U3") (pin "33") (pinfunction "B15_33") (pintype "passive"))
      (node (ref "U9") (pin "4") (pinfunction "HOLD_4") (pintype "passive"))
    )
    (net (code "51") (name "/CPU_INTR") (class "Default")
      (node (ref "R42") (pin "1") (pinfunction "1_1") (pintype "passive"))
      (node (ref "U3") (pin "32") (pinfunction "B16_32") (pintype "passive"))
      (node (ref "U9") (pin "40") (pinfunction "INTR_40") (pintype "passive"))
    )
    (net (code "52") (name "/CPU_LOCK#") (class "Default")
      (node (ref "R45") (pin "1") (pinfunction "1_1") (pintype "passive"))
      (node (ref "U3") (pin "31") (pinfunction "B17_31") (pintype "passive"))
      (node (ref "U9") (pin "26") (pinfunction "LOCK#_26") (pintype "passive"))
    )
    (net (code "53") (name "/CPU_M{slash}IO#") (class "Default")
      (node (ref "R48") (pin "1") (pinfunction "1_1") (pintype "passive"))
      (node (ref "U3") (pin "30") (pinfunction "B18_30") (pintype "passive"))
      (node (ref "U9") (pin "23") (pinfunction "M/IO#_23") (pintype "passive"))
    )
    (net (code "54") (name "/CPU_NA#") (class "Default")
      (node (ref "R51") (pin "1") (pinfunction "1_1") (pintype "passive"))
      (node (ref "U3") (pin "29") (pinfunction "B19_29") (pintype "passive"))
      (node (ref "U9") (pin "6") (pinfunction "NA#_6") (pintype "passive"))
    )
    (net (code "55") (name "/CPU_NMI") (class "Default")
      (node (ref "R54") (pin "1") (pinfunction "1_1") (pintype "passive"))
      (node (ref "U3") (pin "28") (pinfunction "B20_28") (pintype "passive"))
      (node (ref "U9") (pin "38") (pinfunction "NMI_38") (pintype "passive"))
    )
    (net (code "56") (name "/CPU_PEREQ") (class "Default")
      (node (ref "R57") (pin "1") (pinfunction "1_1") (pintype "passive"))
      (node (ref "U3") (pin "27") (pinfunction "B21_27") (pintype "passive"))
      (node (ref "U9") (pin "37") (pinfunction "PEREQ_37") (pintype "passive"))
    )
    (net (code "57") (name "/CPU_READY#") (class "Default")
      (node (ref "R60") (pin "1") (pinfunction "1_1") (pintype "passive"))
      (node (ref "U3") (pin "26") (pinfunction "B22_26") (pintype "passive"))
      (node (ref "U9") (pin "7") (pinfunction "READY#_7") (pintype "passive"))
    )
    (net (code "58") (name "/CPU_RESET") (class "Default")
      (node (ref "R63") (pin "1") (pinfunction "1_1") (pintype "passive"))
      (node (ref "U3") (pin "25") (pinfunction "B23_25") (pintype "passive"))
      (node (ref "U9") (pin "33") (pinfunction "RESET_33") (pintype "passive"))
    )
    (net (code "59") (name "/CPU_W{slash}R#") (class "Default")
      (node (ref "R68") (pin "1") (pinfunction "1_1") (pintype "passive"))
      (node (ref "U5") (pin "44") (pinfunction "B4_44") (pintype "passive"))
      (node (ref "U9") (pin "25") (pinfunction "W/R#_25") (pintype "passive"))
    )
    (net (code "60") (name "/DMA_A0") (class "Default")
      (node (ref "R124") (pin "1") (pinfunction "1_1") (pintype "passive"))
      (node (ref "U10") (pin "36") (pinfunction "A0_36") (pintype "passive"))
      (node (ref "U6") (pin "26") (pinfunction "B22_26") (pintype "passive"))
    )
    (net (code "61") (name "/DMA_A1") (class "Default")
      (node (ref "R118") (pin "1") (pinfunction "1_1") (pintype "passive"))
      (node (ref "U10") (pin "37") (pinfunction "A1_37") (pintype "passive"))
      (node (ref "U6") (pin "28") (pinfunction "B20_28") (pintype "passive"))
    )
    (net (code "62") (name "/DMA_A2") (class "Default")
      (node (ref "R115") (pin "1") (pinfunction "1_1") (pintype "passive"))
      (node (ref "U10") (pin "38") (pinfunction "A2_38") (pintype "passive"))
      (node (ref "U6") (pin "29") (pinfunction "B19_29") (pintype "passive"))
    )
    (net (code "63") (name "/DMA_A3") (class "Default")
      (node (ref "R109") (pin "1") (pinfunction "1_1") (pintype "passive"))
      (node (ref "U10") (pin "39") (pinfunction "A3_39") (pintype "passive"))
      (node (ref "U6") (pin "31") (pinfunction "B17_31") (pintype "passive"))
    )
    (net (code "64") (name "/DMA_A4") (class "Default")
      (node (ref "R106") (pin "1") (pinfunction "1_1") (pintype "passive"))
      (node (ref "U10") (pin "41") (pinfunction "A4_41") (pintype "passive"))
      (node (ref "U6") (pin "32") (pinfunction "B16_32") (pintype "passive"))
    )
    (net (code "65") (name "/DMA_A5") (class "Default")
      (node (ref "R100") (pin "1") (pinfunction "1_1") (pintype "passive"))
      (node (ref "U10") (pin "42") (pinfunction "A5_42") (pintype "passive"))
      (node (ref "U6") (pin "34") (pinfunction "B14_34") (pintype "passive"))
    )
    (net (code "66") (name "/DMA_A6") (class "Default")
      (node (ref "R103") (pin "1") (pinfunction "1_1") (pintype "passive"))
      (node (ref "U10") (pin "43") (pinfunction "A6_43") (pintype "passive"))
      (node (ref "U6") (pin "33") (pinfunction "B15_33") (pintype "passive"))
    )
    (net (code "67") (name "/DMA_A7") (class "Default")
      (node (ref "R80") (pin "1") (pinfunction "1_1") (pintype "passive"))
      (node (ref "U10") (pin "44") (pinfunction "A7_44") (pintype "passive"))
      (node (ref "U7") (pin "41") (pinfunction "B7_41") (pintype "passive"))
    )
    (net (code "68") (name "/DMA_ADSTB") (class "Default")
      (node (ref "R95") (pin "1") (pinfunction "1_1") (pintype "passive"))
      (node (ref "U10") (pin "10") (pinfunction "ADSTB_10") (pintype "passive"))
      (node (ref "U7") (pin "36") (pinfunction "B12_36") (pintype "passive"))
    )
    (net (code "69") (name "/DMA_AEN") (class "Default")
      (node (ref "R98") (pin "1") (pinfunction "1_1") (pintype "passive"))
      (node (ref "U10") (pin "11") (pinfunction "AEN_11") (pintype "passive"))
      (node (ref "U7") (pin "35") (pinfunction "B13_35") (pintype "passive"))
    )
    (net (code "70") (name "/DMA_CLK") (class "Default")
      (node (ref "R107") (pin "1") (pinfunction "1_1") (pintype "passive"))
      (node (ref "U10") (pin "14") (pinfunction "CLK_14") (pintype "passive"))
      (node (ref "U7") (pin "32") (pinfunction "B16_32") (pintype "passive"))
    )
    (net (code "71") (name "/DMA_CS") (class "Default")
      (node (ref "R104") (pin "1") (pinfunction "1_1") (pintype "passive"))
      (node (ref "U10") (pin "13") (pinfunction "~{CS}_13") (pintype "passive"))
      (node (ref "U7") (pin "33") (pinfunction "B15_33") (pintype "passive"))
    )
    (net (code "72") (name "/DMA_DACK0") (class "Default")
      (node (ref "R125") (pin "1") (pinfunction "1_1") (pintype "passive"))
      (node (ref "U10") (pin "28") (pinfunction "DACK0_28") (pintype "passive"))
      (node (ref "U7") (pin "26") (pinfunction "B22_26") (pintype "passive"))
    )
    (net (code "73") (name "/DMA_DACK1") (class "Default")
      (node (ref "R122") (pin "1") (pinfunction "1_1") (pintype "passive"))
      (node (ref "U10") (pin "27") (pinfunction "DACK1_27") (pintype "passive"))
      (node (ref "U7") (pin "27") (pinfunction "B21_27") (pintype "passive"))
    )
    (net (code "74") (name "/DMA_DACK2") (class "Default")
      (node (ref "R113") (pin "1") (pinfunction "1_1") (pintype "passive"))
      (node (ref "U10") (pin "16") (pinfunction "DACK2_16") (pintype "passive"))
      (node (ref "U7") (pin "30") (pinfunction "B18_30") (pintype "passive"))
    )
    (net (code "75") (name "/DMA_DACK3") (class "Default")
      (node (ref "R121") (pin "1") (pinfunction "1_1") (pintype "passive"))
      (node (ref "U10") (pin "18") (pinfunction "DACK3_18") (pintype "passive"))
      (node (ref "U6") (pin "27") (pinfunction "B21_27") (pintype "passive"))
    )
    (net (code "76") (name "/DMA_DREQ0") (class "Default")
      (node (ref "R119") (pin "1") (pinfunction "1_1") (pintype "passive"))
      (node (ref "U10") (pin "22") (pinfunction "DREQ0_22") (pintype "passive"))
      (node (ref "U7") (pin "28") (pinfunction "B20_28") (pintype "passive"))
    )
    (net (code "77") (name "/DMA_DREQ1") (class "Default")
      (node (ref "R116") (pin "1") (pinfunction "1_1") (pintype "passive"))
      (node (ref "U10") (pin "21") (pinfunction "DREQ1_21") (pintype "passive"))
      (node (ref "U7") (pin "29") (pinfunction "B19_29") (pintype "passive"))
    )
    (net (code "78") (name "/DMA_DREQ2") (class "Default")
      (node (ref "R126") (pin "1") (pinfunction "1_1") (pintype "passive"))
      (node (ref "U10") (pin "20") (pinfunction "DREQ2_20") (pintype "passive"))
      (node (ref "U6") (pin "25") (pinfunction "B23_25") (pintype "passive"))
    )
    (net (code "79") (name "/DMA_DREQ3") (class "Default")
      (node (ref "R112") (pin "1") (pinfunction "1_1") (pintype "passive"))
      (node (ref "U10") (pin "19") (pinfunction "DREQ3_19") (pintype "passive"))
      (node (ref "U6") (pin "30") (pinfunction "B18_30") (pintype "passive"))
    )
    (net (code "80") (name "/DMA_EOP") (class "Default")
      (node (ref "R89") (pin "1") (pinfunction "1_1") (pintype "passive"))
      (node (ref "U10") (pin "40") (pinfunction "~{EOP}_40") (pintype "passive"))
      (node (ref "U7") (pin "38") (pinfunction "B10_38") (pintype "passive"))
    )
    (net (code "81") (name "/DMA_HLDA") (class "Default")
      (node (ref "R92") (pin "1") (pinfunction "1_1") (pintype "passive"))
      (node (ref "U10") (pin "9") (pinfunction "HLDA_9") (pintype "passive"))
      (node (ref "U7") (pin "37") (pinfunction "B11_37") (pintype "passive"))
    )
    (net (code "82") (name "/DMA_HRQ") (class "Default")
      (node (ref "R101") (pin "1") (pinfunction "1_1") (pintype "passive"))
      (node (ref "U10") (pin "12") (pinfunction "HRQ_12") (pintype "passive"))
      (node (ref "U7") (pin "34") (pinfunction "B14_34") (pintype "passive"))
    )
    (net (code "83") (name "/DMA_IOR") (class "Default")
      (node (ref "R86") (pin "1") (pinfunction "1_1") (pintype "passive"))
      (node (ref "U10") (pin "1") (pinfunction "~{IOR}_1") (pintype "passive"))
      (node (ref "U7") (pin "39") (pinfunction "B9_39") (pintype "passive"))
    )
    (net (code "84") (name "/DMA_IOW") (class "Default")
      (node (ref "R71") (pin "1") (pinfunction "1_1") (pintype "passive"))
      (node (ref "U10") (pin "2") (pinfunction "~{IOW}_2") (pintype "passive"))
      (node (ref "U7") (pin "44") (pinfunction "B4_44") (pintype "passive"))
    )
    (net (code "85") (name "/DMA_MEMR") (class "Default")
      (node (ref "R83") (pin "1") (pinfunction "1_1") (pintype "passive"))
      (node (ref "U10") (pin "3") (pinfunction "~{MEMR}_3") (pintype "passive"))
      (node (ref "U7") (pin "40") (pinfunction "B8_40") (pintype "passive"))
    )
    (net (code "86") (name "/DMA_MEMW") (class "Default")
      (node (ref "R74") (pin "1") (pinfunction "1_1") (pintype "passive"))
      (node (ref "U10") (pin "4") (pinfunction "~{MEMW}_4") (pintype "passive"))
      (node (ref "U7") (pin "43") (pinfunction "B5_43") (pintype "passive"))
    )
    (net (code "87") (name "/DMA_READY") (class "Default")
      (node (ref "R77") (pin "1") (pinfunction "1_1") (pintype "passive"))
      (node (ref "U10") (pin "6") (pinfunction "READY_6") (pintype "passive"))
      (node (ref "U7") (pin "42") (pinfunction "B6_42") (pintype "passive"))
    )
    (net (code "88") (name "/DMA_RESET") (class "Default")
      (node (ref "R110") (pin "1") (pinfunction "1_1") (pintype "passive"))
      (node (ref "U10") (pin "15") (pinfunction "RESET_15") (pintype "passive"))
      (node (ref "U7") (pin "31") (pinfunction "B17_31") (pintype "passive"))
    )
    (net (code "89") (name "/GPIO0_8") (class "Default")
      (node (ref "U1") (pin "6") (pinfunction "A5_6") (pintype "passive"))
      (node (ref "U4") (pin "119") (pinfunction "IO_A14_119") (pintype "bidirectional"))
    )
    (net (code "90") (name "/GPIO0_9") (class "Default")
      (node (ref "U1") (pin "5") (pinfunction "A4_5") (pintype "passive"))
      (node (ref "U4") (pin "120") (pinfunction "IO_B13_120") (pintype "bidirectional"))
    )
    (net (code "91") (name "/GPIO0_10") (class "Default")
      (node (ref "U1") (pin "8") (pinfunction "A7_8") (pintype "passive"))
      (node (ref "U4") (pin "117") (pinfunction "IO_A15_117") (pintype "bidirectional"))
    )
    (net (code "92") (name "/GPIO0_11") (class "Default")
      (node (ref "U1") (pin "7") (pinfunction "A6_7") (pintype "passive"))
      (node (ref "U4") (pin "118") (pinfunction "IO_B14_118") (pintype "bidirectional"))
    )
    (net (code "93") (name "/GPIO0_12") (class "Default")
      (node (ref "U1") (pin "10") (pinfunction "A9_10") (pintype "passive"))
      (node (ref "U4") (pin "115") (pinfunction "IO_C15_115") (pintype "bidirectional"))
    )
    (net (code "94") (name "/GPIO0_13") (class "Default")
      (node (ref "U1") (pin "9") (pinfunction "A8_9") (pintype "passive"))
      (node (ref "U4") (pin "116") (pinfunction "IO_B16_116") (pintype "bidirectional"))
    )
    (net (code "95") (name "/GPIO0_14") (class "Default")
      (node (ref "U1") (pin "12") (pinfunction "A11_12") (pintype "passive"))
      (node (ref "U4") (pin "113") (pinfunction "IO_D15_113") (pintype "bidirectional"))
    )
    (net (code "96") (name "/GPIO0_15") (class "Default")
      (node (ref "U1") (pin "11") (pinfunction "A10_11") (pintype "passive"))
      (node (ref "U4") (pin "114") (pinfunction "IO_C16_114") (pintype "bidirectional"))
    )
    (net (code "97") (name "/GPIO0_16") (class "Default")
      (node (ref "U1") (pin "14") (pinfunction "A13_14") (pintype "passive"))
      (node (ref "U4") (pin "109") (pinfunction "IO_F15_109") (pintype "bidirectional"))
    )
    (net (code "98") (name "/GPIO0_17") (class "Default")
      (node (ref "U1") (pin "13") (pinfunction "A12_13") (pintype "passive"))
      (node (ref "U4") (pin "112") (pinfunction "IO_D16_112") (pintype "bidirectional"))
    )
    (net (code "99") (name "/GPIO0_18") (class "Default")
      (node (ref "U1") (pin "16") (pinfunction "A15_16") (pintype "passive"))
      (node (ref "U4") (pin "107") (pinfunction "IO_G15_107") (pintype "bidirectional"))
    )
    (net (code "100") (name "/GPIO0_19") (class "Default")
      (node (ref "U1") (pin "15") (pinfunction "A14_15") (pintype "passive"))
      (node (ref "U4") (pin "108") (pinfunction "IO_F16_108") (pintype "bidirectional"))
    )
    (net (code "101") (name "/GPIO0_20") (class "Default")
      (node (ref "U1") (pin "19") (pinfunction "A18_19") (pintype "passive"))
      (node (ref "U4") (pin "104") (pinfunction "IO_J13_104") (pintype "bidirectional"))
    )
    (net (code "102") (name "/GPIO0_21") (class "Default")
      (node (ref "U1") (pin "17") (pinfunction "A16_17") (pintype "passive"))
      (node (ref "U4") (pin "106") (pinfunction "IO_G16_106") (pintype "bidirectional"))
    )
    (net (code "103") (name "/GPIO0_22") (class "Default")
      (node (ref "U1") (pin "21") (pinfunction "A20_21") (pintype "passive"))
      (node (ref "U4") (pin "102") (pinfunction "IO_J15_102") (pintype "bidirectional"))
    )
    (net (code "104") (name "/GPIO0_23") (class "Default")
      (node (ref "U1") (pin "20") (pinfunction "A19_20") (pintype "passive"))
      (node (ref "U4") (pin "103") (pinfunction "IO_J16_103") (pintype "bidirectional"))
    )
    (net (code "105") (name "/GPIO0_24") (class "Default")
      (node (ref "U1") (pin "23") (pinfunction "A22_23") (pintype "passive"))
      (node (ref "U4") (pin "98") (pinfunction "IO_K15_98") (pintype "bidirectional"))
    )
    (net (code "106") (name "/GPIO0_25") (class "Default")
      (node (ref "U1") (pin "22") (pinfunction "A21_22") (pintype "passive"))
      (node (ref "U4") (pin "101") (pinfunction "IO_K16_101") (pintype "bidirectional"))
    )
    (net (code "107") (name "/GPIO0_26") (class "Default")
      (node (ref "U2") (pin "5") (pinfunction "A4_5") (pintype "passive"))
      (node (ref "U4") (pin "96") (pinfunction "IO_L15_96") (pintype "bidirectional"))
    )
    (net (code "108") (name "/GPIO0_27") (class "Default")
      (node (ref "U1") (pin "24") (pinfunction "A23_24") (pintype "passive"))
      (node (ref "U4") (pin "97") (pinfunction "IO_L16_97") (pintype "bidirectional"))
    )
    (net (code "109") (name "/GPIO0_28") (class "Default")
      (node (ref "U2") (pin "7") (pinfunction "A6_7") (pintype "passive"))
      (node (ref "U4") (pin "92") (pinfunction "IO_N15_92") (pintype "bidirectional"))
    )
    (net (code "110") (name "/GPIO0_29") (class "Default")
      (node (ref "U2") (pin "6") (pinfunction "A5_6") (pintype "passive"))
      (node (ref "U4") (pin "93") (pinfunction "IO_N16_93") (pintype "bidirectional"))
    )
    (net (code "111") (name "/GPIO0_30") (class "Default")
      (node (ref "U2") (pin "9") (pinfunction "A8_9") (pintype "passive"))
      (node (ref "U4") (pin "90") (pinfunction "IO_P15_90") (pintype "bidirectional"))
    )
    (net (code "112") (name "/GPIO0_31") (class "Default")
      (node (ref "U2") (pin "8") (pinfunction "A7_8") (pintype "passive"))
      (node (ref "U4") (pin "91") (pinfunction "IO_P16_91") (pintype "bidirectional"))
    )
    (net (code "113") (name "/GPIO0_32") (class "Default")
      (node (ref "U2") (pin "11") (pinfunction "A10_11") (pintype "passive"))
      (node (ref "U4") (pin "88") (pinfunction "IO_T15_88") (pintype "bidirectional"))
    )
    (net (code "114") (name "/GPIO0_33") (class "Default")
      (node (ref "U2") (pin "10") (pinfunction "A9_10") (pintype "passive"))
      (node (ref "U4") (pin "89") (pinfunction "IO_R16_89") (pintype "bidirectional"))
    )
    (net (code "115") (name "/GPIO0_34") (class "Default")
      (node (ref "U2") (pin "13") (pinfunction "A12_13") (pintype "passive"))
      (node (ref "U4") (pin "86") (pinfunction "IO_T14_86") (pintype "bidirectional"))
    )
    (net (code "116") (name "/GPIO0_35") (class "Default")
      (node (ref "U2") (pin "12") (pinfunction "A11_12") (pintype "passive"))
      (node (ref "U4") (pin "87") (pinfunction "IO_R14_87") (pintype "bidirectional"))
    )
    (net (code "117") (name "/GPIO1_0") (class "Default")
      (node (ref "U4") (pin "41") (pinfunction "IO_R5_41") (pintype "bidirectional"))
      (node (ref "U5") (pin "14") (pinfunction "A13_14") (pintype "passive"))
    )
    (net (code "118") (name "/GPIO1_1") (class "Default")
      (node (ref "U4") (pin "40") (pinfunction "IO_T4_40") (pintype "bidirectional"))
      (node (ref "U5") (pin "15") (pinfunction "A14_15") (pintype "passive"))
    )
    (net (code "119") (name "/GPIO1_2") (class "Default")
      (node (ref "U4") (pin "39") (pinfunction "IO_R4_39") (pintype "bidirectional"))
      (node (ref "U5") (pin "16") (pinfunction "A15_16") (pintype "passive"))
    )
    (net (code "120") (name "/GPIO1_3") (class "Default")
      (node (ref "U4") (pin "38") (pinfunction "IO_T3_38") (pintype "bidirectional"))
      (node (ref "U5") (pin "17") (pinfunction "A16_17") (pintype "passive"))
    )
    (net (code "121") (name "/GPIO1_4") (class "Default")
      (node (ref "U4") (pin "37") (pinfunction "IO_R3_37") (pintype "bidirectional"))
      (node (ref "U5") (pin "18") (pinfunction "A17_18") (pintype "passive"))
    )
    (net (code "122") (name "/GPIO1_5") (class "Default")
      (node (ref "U4") (pin "36") (pinfunction "IO_T2_36") (pintype "bidirectional"))
      (node (ref "U5") (pin "19") (pinfunction "A18_19") (pintype "passive"))
    )
    (net (code "123") (name "/GPIO1_6") (class "Default")
      (node (ref "U4") (pin "35") (pinfunction "IO_R1_35") (pintype "bidirectional"))
      (node (ref "U5") (pin "20") (pinfunction "A19_20") (pintype "passive"))
    )
    (net (code "124") (name "/GPIO1_7") (class "Default")
      (node (ref "U4") (pin "34") (pinfunction "IO_P2_34") (pintype "bidirectional"))
      (node (ref "U5") (pin "21") (pinfunction "A20_21") (pintype "passive"))
    )
    (net (code "125") (name "/GPIO1_8") (class "Default")
      (node (ref "U4") (pin "33") (pinfunction "IO_P1_33") (pintype "bidirectional"))
      (node (ref "U5") (pin "22") (pinfunction "A21_22") (pintype "passive"))
    )
    (net (code "126") (name "/GPIO1_9") (class "Default")
      (node (ref "U4") (pin "32") (pinfunction "IO_N2_32") (pintype "bidirectional"))
      (node (ref "U5") (pin "23") (pinfunction "A22_23") (pintype "passive"))
    )
    (net (code "127") (name "/GPIO1_10") (class "Default")
      (node (ref "U4") (pin "31") (pinfunction "IO_N1_31") (pintype "bidirectional"))
      (node (ref "U5") (pin "24") (pinfunction "A23_24") (pintype "passive"))
    )
    (net (code "128") (name "/GPIO1_11") (class "Default")
      (node (ref "U4") (pin "28") (pinfunction "IO_L2_28") (pintype "bidirectional"))
      (node (ref "U6") (pin "5") (pinfunction "A4_5") (pintype "passive"))
    )
    (net (code "129") (name "/GPIO1_12") (class "Default")
      (node (ref "U4") (pin "27") (pinfunction "IO_L1_27") (pintype "bidirectional"))
      (node (ref "U6") (pin "6") (pinfunction "A5_6") (pintype "passive"))
    )
    (net (code "130") (name "/GPIO1_13") (class "Default")
      (node (ref "U4") (pin "26") (pinfunction "IO_K2_26") (pintype "bidirectional"))
      (node (ref "U6") (pin "7") (pinfunction "A6_7") (pintype "passive"))
    )
    (net (code "131") (name "/GPIO1_14") (class "Default")
      (node (ref "U4") (pin "25") (pinfunction "IO_K1_25") (pintype "bidirectional"))
      (node (ref "U6") (pin "8") (pinfunction "A7_8") (pintype "passive"))
    )
    (net (code "132") (name "/GPIO1_15") (class "Default")
      (node (ref "U4") (pin "24") (pinfunction "IO_J2_24") (pintype "bidirectional"))
      (node (ref "U6") (pin "9") (pinfunction "A8_9") (pintype "passive"))
    )
    (net (code "133") (name "/GPIO1_16") (class "Default")
      (node (ref "U4") (pin "21") (pinfunction "IO_J1_21") (pintype "bidirectional"))
      (node (ref "U6") (pin "10") (pinfunction "A9_10") (pintype "passive"))
    )
    (net (code "134") (name "/GPIO1_17") (class "Default")
      (node (ref "U4") (pin "20") (pinfunction "IO_G1_20") (pintype "bidirectional"))
      (node (ref "U6") (pin "11") (pinfunction "A10_11") (pintype "passive"))
    )
    (net (code "135") (name "/GPIO1_18") (class "Default")
      (node (ref "U4") (pin "19") (pinfunction "IO_G2_19") (pintype "bidirectional"))
      (node (ref "U6") (pin "12") (pinfunction "A11_12") (pintype "passive"))
    )
    (net (code "136") (name "/GPIO1_19") (class "Default")
      (node (ref "U4") (pin "18") (pinfunction "IO_F1_18") (pintype "bidirectional"))
      (node (ref "U6") (pin "13") (pinfunction "A12_13") (pintype "passive"))
    )
    (net (code "137") (name "/GPIO1_20") (class "Default")
      (node (ref "U4") (pin "17") (pinfunction "IO_F2_17") (pintype "bidirectional"))
      (node (ref "U6") (pin "14") (pinfunction "A13_14") (pintype "passive"))
    )
    (net (code "138") (name "/GPIO1_21") (class "Default")
      (node (ref "U4") (pin "16") (pinfunction "IO_D1_16") (pintype "bidirectional"))
      (node (ref "U6") (pin "15") (pinfunction "A14_15") (pintype "passive"))
    )
    (net (code "139") (name "/GPIO1_22") (class "Default")
      (node (ref "U4") (pin "15") (pinfunction "IO_C2_15") (pintype "bidirectional"))
      (node (ref "U6") (pin "16") (pinfunction "A15_16") (pintype "passive"))
    )
    (net (code "140") (name "/GPIO1_23") (class "Default")
      (node (ref "U4") (pin "14") (pinfunction "IO_B1_14") (pintype "bidirectional"))
      (node (ref "U6") (pin "17") (pinfunction "A16_17") (pintype "passive"))
    )
    (net (code "141") (name "/GPIO1_24") (class "Default")
      (node (ref "U4") (pin "13") (pinfunction "IO_A2_13") (pintype "bidirectional"))
      (node (ref "U6") (pin "18") (pinfunction "A17_18") (pintype "passive"))
    )
    (net (code "142") (name "/GPIO1_25") (class "Default")
      (node (ref "U4") (pin "12") (pinfunction "IO_B3_12") (pintype "bidirectional"))
      (node (ref "U6") (pin "19") (pinfunction "A18_19") (pintype "passive"))
    )
    (net (code "143") (name "/GPIO1_26") (class "Default")
      (node (ref "U4") (pin "11") (pinfunction "IO_A3_11") (pintype "bidirectional"))
      (node (ref "U6") (pin "20") (pinfunction "A19_20") (pintype "passive"))
    )
    (net (code "144") (name "/GPIO1_27") (class "Default")
      (node (ref "U4") (pin "10") (pinfunction "IO_L7_10") (pintype "bidirectional"))
      (node (ref "U6") (pin "21") (pinfunction "A20_21") (pintype "passive"))
    )
    (net (code "145") (name "/GPIO1_28") (class "Default")
      (node (ref "U4") (pin "9") (pinfunction "IO_N3_9") (pintype "bidirectional"))
      (node (ref "U6") (pin "22") (pinfunction "A21_22") (pintype "passive"))
    )
    (net (code "146") (name "/GPIO1_29") (class "Default")
      (node (ref "U4") (pin "8") (pinfunction "IO_L6_8") (pintype "bidirectional"))
      (node (ref "U6") (pin "23") (pinfunction "A22_23") (pintype "passive"))
    )
    (net (code "147") (name "/GPIO1_30") (class "Default")
      (node (ref "U4") (pin "7") (pinfunction "IO_L4_7") (pintype "bidirectional"))
      (node (ref "U6") (pin "24") (pinfunction "A23_24") (pintype "passive"))
    )
    (net (code "148") (name "/GPIO1_31") (class "Default")
      (node (ref "U4") (pin "6") (pinfunction "IO_L3_6") (pintype "bidirectional"))
      (node (ref "U7") (pin "5") (pinfunction "A4_5") (pintype "passive"))
    )
    (net (code "149") (name "/GPIO1_32") (class "Default")
      (node (ref "U4") (pin "5") (pinfunction "IO_K6_5") (pintype "bidirectional"))
      (node (ref "U7") (pin "6") (pinfunction "A5_6") (pintype "passive"))
    )
    (net (code "150") (name "/GPIO1_33") (class "Default")
      (node (ref "U4") (pin "4") (pinfunction "IO_K5_4") (pintype "bidirectional"))
      (node (ref "U7") (pin "7") (pinfunction "A6_7") (pintype "passive"))
    )
    (net (code "151") (name "/GPIO1_34") (class "Default")
      (node (ref "U4") (pin "153") (pinfunction "IO_K8_153") (pintype "bidirectional"))
      (node (ref "U7") (pin "8") (pinfunction "A7_8") (pintype "passive"))
    )
    (net (code "152") (name "/GPIO1_35") (class "Default")
      (node (ref "U4") (pin "152") (pinfunction "IO_J6_152") (pintype "bidirectional"))
      (node (ref "U7") (pin "9") (pinfunction "A8_9") (pintype "passive"))
    )
    (net (code "153") (name "/GPIO1_36") (class "Default")
      (node (ref "U4") (pin "151") (pinfunction "IO_G5_151") (pintype "bidirectional"))
      (node (ref "U7") (pin "10") (pinfunction "A9_10") (pintype "passive"))
    )
    (net (code "154") (name "/GPIO1_37") (class "Default")
      (node (ref "U4") (pin "148") (pinfunction "IO_F5_148") (pintype "bidirectional"))
      (node (ref "U7") (pin "11") (pinfunction "A10_11") (pintype "passive"))
    )
    (net (code "155") (name "/GPIO1_38") (class "Default")
      (node (ref "U4") (pin "147") (pinfunction "IO_F3_147") (pintype "bidirectional"))
      (node (ref "U7") (pin "12") (pinfunction "A11_12") (pintype "passive"))
    )
    (net (code "156") (name "/GPIO1_39") (class "Default")
      (node (ref "U4") (pin "146") (pinfunction "IO_E5_146") (pintype "bidirectional"))
      (node (ref "U7") (pin "13") (pinfunction "A12_13") (pintype "passive"))
    )
    (net (code "157") (name "/GPIO1_40") (class "Default")
      (node (ref "U4") (pin "145") (pinfunction "IO_D3_145") (pintype "bidirectional"))
      (node (ref "U7") (pin "14") (pinfunction "A13_14") (pintype "passive"))
    )
    (net (code "158") (name "/GPIO1_41") (class "Default")
      (node (ref "U4") (pin "144") (pinfunction "IO_D4_144") (pintype "bidirectional"))
      (node (ref "U7") (pin "15") (pinfunction "A14_15") (pintype "passive"))
    )
    (net (code "159") (name "/GPIO1_42") (class "Default")
      (node (ref "U4") (pin "143") (pinfunction "IO_C3_143") (pintype "bidirectional"))
      (node (ref "U7") (pin "16") (pinfunction "A15_16") (pintype "passive"))
    )
    (net (code "160") (name "/GPIO1_43") (class "Default")
      (node (ref "U4") (pin "142") (pinfunction "IO_B11_142") (pintype "bidirectional"))
      (node (ref "U7") (pin "17") (pinfunction "A16_17") (pintype "passive"))
    )
    (net (code "161") (name "/GPIO1_44") (class "Default")
      (node (ref "U4") (pin "141") (pinfunction "IO_D14_141") (pintype "bidirectional"))
      (node (ref "U7") (pin "18") (pinfunction "A17_18") (pintype "passive"))
    )
    (net (code "162") (name "/GPIO1_45") (class "Default")
      (node (ref "U4") (pin "140") (pinfunction "IO_F10_140") (pintype "bidirectional"))
      (node (ref "U7") (pin "19") (pinfunction "A18_19") (pintype "passive"))
    )
    (net (code "163") (name "/GPIO1_46") (class "Default")
      (node (ref "U4") (pin "137") (pinfunction "IO_F13_137") (pintype "bidirectional"))
      (node (ref "U7") (pin "20") (pinfunction "A19_20") (pintype "passive"))
    )
    (net (code "164") (name "/GPIO1_47") (class "Default")
      (node (ref "U4") (pin "136") (pinfunction "IO_F14_136") (pintype "bidirectional"))
      (node (ref "U7") (pin "21") (pinfunction "A20_21") (pintype "passive"))
    )
    (net (code "165") (name "/GPIO1_48") (class "Default")
      (node (ref "U4") (pin "135") (pinfunction "IO_F11_135") (pintype "bidirectional"))
      (node (ref "U7") (pin "22") (pinfunction "A21_22") (pintype "passive"))
    )
    (net (code "166") (name "/GPIO1_49") (class "Default")
      (node (ref "U4") (pin "134") (pinfunction "IO_G11_134") (pintype "bidirectional"))
      (node (ref "U7") (pin "23") (pinfunction "A22_23") (pintype "passive"))
    )
    (net (code "167") (name "/GPIO2_0") (class "Default")
      (node (ref "U2") (pin "14") (pinfunction "A13_14") (pintype "passive"))
      (node (ref "U4") (pin "85") (pinfunction "IO_N14_85") (pintype "bidirectional"))
    )
    (net (code "168") (name "/GPIO2_1") (class "Default")
      (node (ref "U2") (pin "15") (pinfunction "A14_15") (pintype "passive"))
      (node (ref "U4") (pin "84") (pinfunction "IO_N13_84") (pintype "bidirectional"))
    )
    (net (code "169") (name "/GPIO2_2") (class "Default")
      (node (ref "U2") (pin "16") (pinfunction "A15_16") (pintype "passive"))
      (node (ref "U4") (pin "83") (pinfunction "IO_P14_83") (pintype "bidirectional"))
    )
    (net (code "170") (name "/GPIO2_3") (class "Default")
      (node (ref "U2") (pin "17") (pinfunction "A16_17") (pintype "passive"))
      (node (ref "U4") (pin "82") (pinfunction "IO_L11_82") (pintype "bidirectional"))
    )
    (net (code "171") (name "/GPIO2_4") (class "Default")
      (node (ref "U2") (pin "18") (pinfunction "A17_18") (pintype "passive"))
      (node (ref "U4") (pin "81") (pinfunction "IO_N12_81") (pintype "bidirectional"))
    )
    (net (code "172") (name "/GPIO2_5") (class "Default")
      (node (ref "U2") (pin "19") (pinfunction "A18_19") (pintype "passive"))
      (node (ref "U4") (pin "80") (pinfunction "IO_N11_80") (pintype "bidirectional"))
    )
    (net (code "173") (name "/GPIO2_6") (class "Default")
      (node (ref "U2") (pin "20") (pinfunction "A19_20") (pintype "passive"))
      (node (ref "U4") (pin "79") (pinfunction "IO_P11_79") (pintype "bidirectional"))
    )
    (net (code "174") (name "/GPIO2_7") (class "Default")
      (node (ref "U2") (pin "21") (pinfunction "A20_21") (pintype "passive"))
      (node (ref "U4") (pin "77") (pinfunction "IO_M11_77") (pintype "bidirectional"))
    )
    (net (code "175") (name "/GPIO2_8") (class "Default")
      (node (ref "U2") (pin "22") (pinfunction "A21_22") (pintype "passive"))
      (node (ref "U4") (pin "76") (pinfunction "IO_M10_76") (pintype "bidirectional"))
    )
    (net (code "176") (name "/GPIO2_9") (class "Default")
      (node (ref "U2") (pin "23") (pinfunction "A22_23") (pintype "passive"))
      (node (ref "U4") (pin "75") (pinfunction "IO_N9_75") (pintype "bidirectional"))
    )
    (net (code "177") (name "/GPIO2_10") (class "Default")
      (node (ref "U2") (pin "24") (pinfunction "A23_24") (pintype "passive"))
      (node (ref "U4") (pin "74") (pinfunction "IO_M9_74") (pintype "bidirectional"))
    )
    (net (code "178") (name "/GPIO2_11") (class "Default")
      (node (ref "U3") (pin "5") (pinfunction "A4_5") (pintype "passive"))
      (node (ref "U4") (pin "73") (pinfunction "IO_L9_73") (pintype "bidirectional"))
    )
    (net (code "179") (name "/GPIO2_12") (class "Default")
      (node (ref "U3") (pin "6") (pinfunction "A5_6") (pintype "passive"))
      (node (ref "U4") (pin "72") (pinfunction "IO_R13_72") (pintype "bidirectional"))
    )
    (net (code "180") (name "/GPIO2_13") (class "Default")
      (node (ref "U3") (pin "7") (pinfunction "A6_7") (pintype "passive"))
      (node (ref "U4") (pin "71") (pinfunction "IO_T13_71") (pintype "bidirectional"))
    )
    (net (code "181") (name "/GPIO2_14") (class "Default")
      (node (ref "U3") (pin "8") (pinfunction "A7_8") (pintype "passive"))
      (node (ref "U4") (pin "70") (pinfunction "IO_R12_70") (pintype "bidirectional"))
    )
    (net (code "182") (name "/GPIO2_15") (class "Default")
      (node (ref "U3") (pin "9") (pinfunction "A8_9") (pintype "passive"))
      (node (ref "U4") (pin "69") (pinfunction "IO_T12_69") (pintype "bidirectional"))
    )
    (net (code "183") (name "/GPIO2_16") (class "Default")
      (node (ref "U3") (pin "10") (pinfunction "A9_10") (pintype "passive"))
      (node (ref "U4") (pin "68") (pinfunction "IO_R11_68") (pintype "bidirectional"))
    )
    (net (code "184") (name "/GPIO2_17") (class "Default")
      (node (ref "U3") (pin "11") (pinfunction "A10_11") (pintype "passive"))
      (node (ref "U4") (pin "67") (pinfunction "IO_T11_67") (pintype "bidirectional"))
    )
    (net (code "185") (name "/GPIO2_18") (class "Default")
      (node (ref "U3") (pin "12") (pinfunction "A11_12") (pintype "passive"))
      (node (ref "U4") (pin "66") (pinfunction "IO_R10_66") (pintype "bidirectional"))
    )
    (net (code "186") (name "/GPIO2_19") (class "Default")
      (node (ref "U3") (pin "13") (pinfunction "A12_13") (pintype "passive"))
      (node (ref "U4") (pin "65") (pinfunction "IO_T10_65") (pintype "bidirectional"))
    )
    (net (code "187") (name "/GPIO2_20") (class "Default")
      (node (ref "U3") (pin "14") (pinfunction "A13_14") (pintype "passive"))
      (node (ref "U4") (pin "64") (pinfunction "IO_R9_64") (pintype "bidirectional"))
    )
    (net (code "188") (name "/GPIO2_21") (class "Default")
      (node (ref "U3") (pin "15") (pinfunction "A14_15") (pintype "passive"))
      (node (ref "U4") (pin "63") (pinfunction "IO_T9_63") (pintype "bidirectional"))
    )
    (net (code "189") (name "/GPIO2_22") (class "Default")
      (node (ref "U3") (pin "16") (pinfunction "A15_16") (pintype "passive"))
      (node (ref "U4") (pin "62") (pinfunction "IO_P9_62") (pintype "bidirectional"))
    )
    (net (code "190") (name "/GPIO2_23") (class "Default")
      (node (ref "U3") (pin "17") (pinfunction "A16_17") (pintype "passive"))
      (node (ref "U4") (pin "59") (pinfunction "IO_T8_59") (pintype "bidirectional"))
    )
    (net (code "191") (name "/GPIO2_24") (class "Default")
      (node (ref "U3") (pin "18") (pinfunction "A17_18") (pintype "passive"))
      (node (ref "U4") (pin "58") (pinfunction "IO_R8_58") (pintype "bidirectional"))
    )
    (net (code "192") (name "/GPIO2_25") (class "Default")
      (node (ref "U3") (pin "19") (pinfunction "A18_19") (pintype "passive"))
      (node (ref "U4") (pin "57") (pinfunction "IO_T7_57") (pintype "bidirectional"))
    )
    (net (code "193") (name "/GPIO2_26") (class "Default")
      (node (ref "U3") (pin "20") (pinfunction "A19_20") (pintype "passive"))
      (node (ref "U4") (pin "56") (pinfunction "IO_R7_56") (pintype "bidirectional"))
    )
    (net (code "194") (name "/GPIO2_27") (class "Default")
      (node (ref "U3") (pin "21") (pinfunction "A20_21") (pintype "passive"))
      (node (ref "U4") (pin "55") (pinfunction "IO_T6_55") (pintype "bidirectional"))
    )
    (net (code "195") (name "/GPIO3_7") (class "Default")
      (node (ref "U4") (pin "43") (pinfunction "IO_N5_43") (pintype "bidirectional"))
      (node (ref "U5") (pin "12") (pinfunction "A11_12") (pintype "passive"))
    )
    (net (code "196") (name "/GPIO3_8") (class "Default")
      (node (ref "U4") (pin "42") (pinfunction "IO_P3_42") (pintype "bidirectional"))
      (node (ref "U5") (pin "13") (pinfunction "A12_13") (pintype "passive"))
    )
    (net (code "197") (name "/GPIO3_9") (class "Default")
      (node (ref "U4") (pin "46") (pinfunction "IO_N6_46") (pintype "bidirectional"))
      (node (ref "U5") (pin "10") (pinfunction "A9_10") (pintype "passive"))
    )
    (net (code "198") (name "/GPIO3_10") (class "Default")
      (node (ref "U4") (pin "45") (pinfunction "IO_M6_45") (pintype "bidirectional"))
      (node (ref "U5") (pin "11") (pinfunction "A10_11") (pintype "passive"))
    )
    (net (code "199") (name "/GPIO3_11") (class "Default")
      (node (ref "U4") (pin "48") (pinfunction "IO_M7_48") (pintype "bidirectional"))
      (node (ref "U5") (pin "8") (pinfunction "A7_8") (pintype "passive"))
    )
    (net (code "200") (name "/GPIO3_12") (class "Default")
      (node (ref "U4") (pin "47") (pinfunction "IO_P6_47") (pintype "bidirectional"))
      (node (ref "U5") (pin "9") (pinfunction "A8_9") (pintype "passive"))
    )
    (net (code "201") (name "/GPIO3_13") (class "Default")
      (node (ref "U4") (pin "50") (pinfunction "IO_P8_50") (pintype "bidirectional"))
      (node (ref "U5") (pin "6") (pinfunction "A5_6") (pintype "passive"))
    )
    (net (code "202") (name "/GPIO3_14") (class "Default")
      (node (ref "U4") (pin "49") (pinfunction "IO_N8_49") (pintype "bidirectional"))
      (node (ref "U5") (pin "7") (pinfunction "A6_7") (pintype "passive"))
    )
    (net (code "203") (name "/GPIO3_15") (class "Default")
      (node (ref "U3") (pin "24") (pinfunction "A23_24") (pintype "passive"))
      (node (ref "U4") (pin "52") (pinfunction "IO_L8_52") (pintype "bidirectional"))
    )
    (net (code "204") (name "/GPIO3_16") (class "Default")
      (node (ref "U4") (pin "51") (pinfunction "IO_M8_51") (pintype "bidirectional"))
      (node (ref "U5") (pin "5") (pinfunction "A4_5") (pintype "passive"))
    )
    (net (code "205") (name "/GPIO3_17") (class "Default")
      (node (ref "U3") (pin "22") (pinfunction "A21_22") (pintype "passive"))
      (node (ref "U4") (pin "54") (pinfunction "IO_R6_54") (pintype "bidirectional"))
    )
    (net (code "206") (name "/GPIO3_18") (class "Default")
      (node (ref "U3") (pin "23") (pinfunction "A22_23") (pintype "passive"))
      (node (ref "U4") (pin "53") (pinfunction "IO_T5_53") (pintype "bidirectional"))
    )
    (net (code "207") (name "/PIC_A0") (class "Default")
      (node (ref "R120") (pin "1") (pinfunction "1_1") (pintype "passive"))
      (node (ref "U13") (pin "27") (pinfunction "A0_27") (pintype "passive"))
      (node (ref "U5") (pin "26") (pinfunction "B22_26") (pintype "passive"))
    )
    (net (code "208") (name "/PIC_CS") (class "Default")
      (node (ref "R111") (pin "1") (pinfunction "1_1") (pintype "passive"))
      (node (ref "U13") (pin "1") (pinfunction "~{CS}_1") (pintype "passive"))
      (node (ref "U5") (pin "29") (pinfunction "B19_29") (pintype "passive"))
    )
    (net (code "209") (name "/PIC_INT") (class "Default")
      (node (ref "R73") (pin "1") (pinfunction "1_1") (pintype "passive"))
      (node (ref "U13") (pin "17") (pinfunction "INT_17") (pintype "passive"))
      (node (ref "U6") (pin "43") (pinfunction "B5_43") (pintype "passive"))
    )
    (net (code "210") (name "/PIC_INTA") (class "Default")
      (node (ref "R123") (pin "1") (pinfunction "1_1") (pintype "passive"))
      (node (ref "U13") (pin "26") (pinfunction "~{INTA}_26") (pintype "passive"))
      (node (ref "U5") (pin "25") (pinfunction "B23_25") (pintype "passive"))
    )
    (net (code "211") (name "/PIC_IR0") (class "Default")
      (node (ref "R76") (pin "1") (pinfunction "1_1") (pintype "passive"))
      (node (ref "U13") (pin "18") (pinfunction "IR0_18") (pintype "passive"))
      (node (ref "U6") (pin "42") (pinfunction "B6_42") (pintype "passive"))
    )
    (net (code "212") (name "/PIC_IR1") (class "Default")
      (node (ref "R82") (pin "1") (pinfunction "1_1") (pintype "passive"))
      (node (ref "U13") (pin "19") (pinfunction "IR1_19") (pintype "passive"))
      (node (ref "U6") (pin "40") (pinfunction "B8_40") (pintype "passive"))
    )
    (net (code "213") (name "/PIC_IR2") (class "Default")
      (node (ref "R88") (pin "1") (pinfunction "1_1") (pintype "passive"))
      (node (ref "U13") (pin "20") (pinfunction "IR2_20") (pintype "passive"))
      (node (ref "U6") (pin "38") (pinfunction "B10_38") (pintype "passive"))
    )
    (net (code "214") (name "/PIC_IR3") (class "Default")
      (node (ref "R79") (pin "1") (pinfunction "1_1") (pintype "passive"))
      (node (ref "U13") (pin "21") (pinfunction "IR3_21") (pintype "passive"))
      (node (ref "U6") (pin "41") (pinfunction "B7_41") (pintype "passive"))
    )
    (net (code "215") (name "/PIC_IR4") (class "Default")
      (node (ref "R85") (pin "1") (pinfunction "1_1") (pintype "passive"))
      (node (ref "U13") (pin "22") (pinfunction "IR4_22") (pintype "passive"))
      (node (ref "U6") (pin "39") (pinfunction "B9_39") (pintype "passive"))
    )
    (net (code "216") (name "/PIC_IR5") (class "Default")
      (node (ref "R91") (pin "1") (pinfunction "1_1") (pintype "passive"))
      (node (ref "U13") (pin "23") (pinfunction "IR5_23") (pintype "passive"))
      (node (ref "U6") (pin "37") (pinfunction "B11_37") (pintype "passive"))
    )
    (net (code "217") (name "/PIC_IR6") (class "Default")
      (node (ref "R94") (pin "1") (pinfunction "1_1") (pintype "passive"))
      (node (ref "U13") (pin "24") (pinfunction "IR6_24") (pintype "passive"))
      (node (ref "U6") (pin "36") (pinfunction "B12_36") (pintype "passive"))
    )
    (net (code "218") (name "/PIC_IR7") (class "Default")
      (node (ref "R97") (pin "1") (pinfunction "1_1") (pintype "passive"))
      (node (ref "U13") (pin "25") (pinfunction "IR7_25") (pintype "passive"))
      (node (ref "U6") (pin "35") (pinfunction "B13_35") (pintype "passive"))
    )
    (net (code "219") (name "/PIC_RD") (class "Default")
      (node (ref "R117") (pin "1") (pinfunction "1_1") (pintype "passive"))
      (node (ref "U13") (pin "3") (pinfunction "~{RD}_3") (pintype "passive"))
      (node (ref "U5") (pin "27") (pinfunction "B21_27") (pintype "passive"))
    )
    (net (code "220") (name "/PIC_SP{slash}EN") (class "Default")
      (node (ref "R70") (pin "1") (pinfunction "1_1") (pintype "passive"))
      (node (ref "U13") (pin "16") (pinfunction "~{SP}/~{EN}_16") (pintype "passive"))
      (node (ref "U6") (pin "44") (pinfunction "B4_44") (pintype "passive"))
    )
    (net (code "221") (name "/PIC_WR") (class "Default")
      (node (ref "R114") (pin "1") (pinfunction "1_1") (pintype "passive"))
      (node (ref "U13") (pin "2") (pinfunction "~{WR}_2") (pintype "passive"))
      (node (ref "U5") (pin "28") (pinfunction "B20_28") (pintype "passive"))
    )
    (net (code "222") (name "/PIT_A0") (class "Default")
      (node (ref "R87") (pin "1") (pinfunction "1_1") (pintype "passive"))
      (node (ref "U14") (pin "22") (pinfunction "A0_22") (pintype "passive"))
      (node (ref "U5") (pin "37") (pinfunction "B11_37") (pintype "passive"))
    )
    (net (code "223") (name "/PIT_A1") (class "Default")
      (node (ref "R90") (pin "1") (pinfunction "1_1") (pintype "passive"))
      (node (ref "U14") (pin "23") (pinfunction "A1_23") (pintype "passive"))
      (node (ref "U5") (pin "36") (pinfunction "B12_36") (pintype "passive"))
    )
    (net (code "224") (name "/PIT_CLK0") (class "Default")
      (node (ref "R69") (pin "1") (pinfunction "1_1") (pintype "passive"))
      (node (ref "U14") (pin "10") (pinfunction "CLK0_10") (pintype "passive"))
      (node (ref "U5") (pin "43") (pinfunction "B5_43") (pintype "passive"))
    )
    (net (code "225") (name "/PIT_CLK1") (class "Default")
      (node (ref "R72") (pin "1") (pinfunction "1_1") (pintype "passive"))
      (node (ref "U14") (pin "18") (pinfunction "CLK1_18") (pintype "passive"))
      (node (ref "U5") (pin "42") (pinfunction "B6_42") (pintype "passive"))
    )
    (net (code "226") (name "/PIT_CLK2") (class "Default")
      (node (ref "R75") (pin "1") (pinfunction "1_1") (pintype "passive"))
      (node (ref "U14") (pin "21") (pinfunction "CLK2_21") (pintype "passive"))
      (node (ref "U5") (pin "41") (pinfunction "B7_41") (pintype "passive"))
    )
    (net (code "227") (name "/PIT_CS") (class "Default")
      (node (ref "R78") (pin "1") (pinfunction "1_1") (pintype "passive"))
      (node (ref "U14") (pin "24") (pinfunction "CS#_24") (pintype "passive"))
      (node (ref "U5") (pin "40") (pinfunction "B8_40") (pintype "passive"))
    )
    (net (code "228") (name "/PIT_GATE0") (class "Default")
      (node (ref "R93") (pin "1") (pinfunction "1_1") (pintype "passive"))
      (node (ref "U14") (pin "13") (pinfunction "GATE0_13") (pintype "passive"))
      (node (ref "U5") (pin "35") (pinfunction "B13_35") (pintype "passive"))
    )
    (net (code "229") (name "/PIT_GATE1") (class "Default")
      (node (ref "R96") (pin "1") (pinfunction "1_1") (pintype "passive"))
      (node (ref "U14") (pin "17") (pinfunction "GATE1_17") (pintype "passive"))
      (node (ref "U5") (pin "34") (pinfunction "B14_34") (pintype "passive"))
    )
    (net (code "230") (name "/PIT_GATE2") (class "Default")
      (node (ref "R99") (pin "1") (pinfunction "1_1") (pintype "passive"))
      (node (ref "U14") (pin "19") (pinfunction "GATE2_19") (pintype "passive"))
      (node (ref "U5") (pin "33") (pinfunction "B15_33") (pintype "passive"))
    )
    (net (code "231") (name "/PIT_OUT0") (class "Default")
      (node (ref "R102") (pin "1") (pinfunction "1_1") (pintype "passive"))
      (node (ref "U14") (pin "12") (pinfunction "OUT0_12") (pintype "passive"))
      (node (ref "U5") (pin "32") (pinfunction "B16_32") (pintype "passive"))
    )
    (net (code "232") (name "/PIT_OUT1") (class "Default")
      (node (ref "R105") (pin "1") (pinfunction "1_1") (pintype "passive"))
      (node (ref "U14") (pin "16") (pinfunction "OUT1_16") (pintype "passive"))
      (node (ref "U5") (pin "31") (pinfunction "B17_31") (pintype "passive"))
    )
    (net (code "233") (name "/PIT_OUT2") (class "Default")
      (node (ref "R108") (pin "1") (pinfunction "1_1") (pintype "passive"))
      (node (ref "U14") (pin "20") (pinfunction "OUT2_20") (pintype "passive"))
      (node (ref "U5") (pin "30") (pinfunction "B18_30") (pintype "passive"))
    )
    (net (code "234") (name "/PIT_RD") (class "Default")
      (node (ref "R81") (pin "1") (pinfunction "1_1") (pintype "passive"))
      (node (ref "U14") (pin "26") (pinfunction "RD#_26") (pintype "passive"))
      (node (ref "U5") (pin "39") (pinfunction "B9_39") (pintype "passive"))
    )
    (net (code "235") (name "/PIT_WR") (class "Default")
      (node (ref "R84") (pin "1") (pinfunction "1_1") (pintype "passive"))
      (node (ref "U14") (pin "27") (pinfunction "WR#_27") (pintype "passive"))
      (node (ref "U5") (pin "38") (pinfunction "B10_38") (pintype "passive"))
    )
    (net (code "236") (name "/SD_CLK") (class "Default")
      (node (ref "CN1") (pin "5") (pinfunction "CLK/SPI_SCLK_5") (pintype "passive"))
      (node (ref "R134") (pin "1") (pinfunction "1_1") (pintype "passive"))
      (node (ref "U4") (pin "126") (pinfunction "IO_K12_126") (pintype "bidirectional"))
    )
    (net (code "237") (name "/SD_CMD") (class "Default")
      (node (ref "CN1") (pin "3") (pinfunction "CMD/SPI_DI_3") (pintype "passive"))
      (node (ref "R135") (pin "1") (pinfunction "1_1") (pintype "passive"))
      (node (ref "U4") (pin "127") (pinfunction "IO_J14_127") (pintype "bidirectional"))
    )
    (net (code "238") (name "/SD_DAT0") (class "Default")
      (node (ref "CN1") (pin "7") (pinfunction "DAT0/SPI_DO_7") (pintype "passive"))
      (node (ref "R133") (pin "1") (pinfunction "1_1") (pintype "passive"))
      (node (ref "U4") (pin "125") (pinfunction "IO_L13_125") (pintype "bidirectional"))
    )
    (net (code "239") (name "/SD_DAT1") (class "Default")
      (node (ref "CN1") (pin "8") (pinfunction "DAT1_8") (pintype "passive"))
      (node (ref "R132") (pin "1") (pinfunction "1_1") (pintype "passive"))
      (node (ref "U4") (pin "124") (pinfunction "IO_L14_124") (pintype "bidirectional"))
    )
    (net (code "240") (name "/SD_DAT2") (class "Default")
      (node (ref "CN1") (pin "1") (pinfunction "DAT2_1") (pintype "passive"))
      (node (ref "R137") (pin "1") (pinfunction "1_1") (pintype "passive"))
      (node (ref "U4") (pin "129") (pinfunction "IO_J12_129") (pintype "bidirectional"))
    )
    (net (code "241") (name "/SD_DAT3") (class "Default")
      (node (ref "CN1") (pin "2") (pinfunction "DAT3/SPI_CS_2") (pintype "passive"))
      (node (ref "R136") (pin "1") (pinfunction "1_1") (pintype "passive"))
      (node (ref "U4") (pin "128") (pinfunction "IO_K11_128") (pintype "bidirectional"))
    )
    (net (code "242") (name "/SPI_CLK") (class "Default")
      (node (ref "U4") (pin "123") (pinfunction "IO_L12_123") (pintype "bidirectional"))
      (node (ref "U8") (pin "6") (pinfunction "CLK_6") (pintype "passive"))
    )
    (net (code "243") (name "/SPI_CS") (class "Default")
      (node (ref "R128") (pin "1") (pinfunction "1_1") (pintype "passive"))
      (node (ref "U4") (pin "131") (pinfunction "IO_K10_131") (pintype "bidirectional"))
      (node (ref "U8") (pin "1") (pinfunction "~{CS}_1") (pintype "passive"))
    )
    (net (code "244") (name "/SPI_DI") (class "Default")
      (node (ref "U4") (pin "122") (pinfunction "IO_M12_122") (pintype "bidirectional"))
      (node (ref "U8") (pin "5") (pinfunction "DI_5") (pintype "passive"))
    )
    (net (code "245") (name "/SPI_DO") (class "Default")
      (node (ref "U4") (pin "130") (pinfunction "IO_J11_130") (pintype "bidirectional"))
      (node (ref "U8") (pin "2") (pinfunction "DO_2") (pintype "passive"))
    )
    (net (code "246") (name "/SRAM_CE#") (class "Default")
      (node (ref "R11") (pin "1") (pinfunction "1_1") (pintype "passive"))
      (node (ref "U11") (pin "6") (pinfunction "CE#_6") (pintype "passive"))
      (node (ref "U2") (pin "42") (pinfunction "B6_42") (pintype "passive"))
    )
    (net (code "247") (name "/SRAM_LB#") (class "Default")
      (node (ref "R17") (pin "1") (pinfunction "1_1") (pintype "passive"))
      (node (ref "U11") (pin "39") (pinfunction "LB#_39") (pintype "passive"))
      (node (ref "U2") (pin "40") (pinfunction "B8_40") (pintype "passive"))
    )
    (net (code "248") (name "/SRAM_OE#") (class "Default")
      (node (ref "R5") (pin "1") (pinfunction "1_1") (pintype "passive"))
      (node (ref "U11") (pin "41") (pinfunction "OE#_41") (pintype "passive"))
      (node (ref "U2") (pin "44") (pinfunction "B4_44") (pintype "passive"))
    )
    (net (code "249") (name "/SRAM_UB#") (class "Default")
      (node (ref "R14") (pin "1") (pinfunction "1_1") (pintype "passive"))
      (node (ref "U11") (pin "40") (pinfunction "UB#_40") (pintype "passive"))
      (node (ref "U2") (pin "41") (pinfunction "B7_41") (pintype "passive"))
    )
    (net (code "250") (name "/SRAM_WE#") (class "Default")
      (node (ref "R8") (pin "1") (pinfunction "1_1") (pintype "passive"))
      (node (ref "U11") (pin "17") (pinfunction "WE#_17") (pintype "passive"))
      (node (ref "U2") (pin "43") (pinfunction "B5_43") (pintype "passive"))
    )
    (net (code "251") (name "/TCK") (class "Default")
      (node (ref "J1") (pin "1") (pinfunction "1_1") (pintype "passive"))
      (node (ref "U4") (pin "150") (pinfunction "TCK_150") (pintype "bidirectional"))
    )
    (net (code "252") (name "/TDI") (class "Default")
      (node (ref "J1") (pin "9") (pinfunction "9_9") (pintype "passive"))
      (node (ref "U4") (pin "149") (pinfunction "TDI_149") (pintype "bidirectional"))
    )
    (net (code "253") (name "/TDO") (class "Default")
      (node (ref "J1") (pin "3") (pinfunction "3_3") (pintype "passive"))
      (node (ref "U4") (pin "3") (pinfunction "TDO_3") (pintype "bidirectional"))
    )
    (net (code "254") (name "/TMS") (class "Default")
      (node (ref "J1") (pin "5") (pinfunction "5_5") (pintype "passive"))
      (node (ref "U4") (pin "154") (pinfunction "TMS_154") (pintype "bidirectional"))
    )
    (net (code "255") (name "/UART_RX") (class "Default")
      (node (ref "P1") (pin "3") (pinfunction "3_3") (pintype "passive"))
      (node (ref "U4") (pin "132") (pinfunction "IO_L10_132") (pintype "bidirectional"))
    )
    (net (code "256") (name "/UART_TX") (class "Default")
      (node (ref "P1") (pin "2") (pinfunction "2_2") (pintype "passive"))
      (node (ref "U4") (pin "133") (pinfunction "IO_K9_133") (pintype "bidirectional"))
    )
    (net (code "257") (name "GND") (class "Default")
      (node (ref "C11") (pin "2") (pinfunction "2_2") (pintype "passive"))
      (node (ref "C12") (pin "2") (pinfunction "2_2") (pintype "passive"))
      (node (ref "C16") (pin "2") (pinfunction "2_2") (pintype "passive"))
      (node (ref "C17") (pin "2") (pinfunction "2_2") (pintype "passive"))
      (node (ref "C18") (pin "2") (pinfunction "2_2") (pintype "passive"))
      (node (ref "C22") (pin "2") (pinfunction "2_2") (pintype "passive"))
      (node (ref "C23") (pin "2") (pinfunction "2_2") (pintype "passive"))
      (node (ref "C24") (pin "2") (pinfunction "2_2") (pintype "passive"))
      (node (ref "C25") (pin "1") (pinfunction "1_1") (pintype "passive"))
      (node (ref "C26") (pin "2") (pinfunction "2_2") (pintype "passive"))
      (node (ref "C27") (pin "2") (pinfunction "2_2") (pintype "passive"))
      (node (ref "C28") (pin "2") (pinfunction "2_2") (pintype "passive"))
      (node (ref "C29") (pin "2") (pinfunction "2_2") (pintype "passive"))
      (node (ref "C3") (pin "2") (pinfunction "2_2") (pintype "passive"))
      (node (ref "C30") (pin "2") (pinfunction "2_2") (pintype "passive"))
      (node (ref "C31") (pin "1") (pinfunction "1_1") (pintype "passive"))
      (node (ref "C32") (pin "2") (pinfunction "2_2") (pintype "passive"))
      (node (ref "C33") (pin "2") (pinfunction "2_2") (pintype "passive"))
      (node (ref "C34") (pin "1") (pinfunction "1_1") (pintype "passive"))
      (node (ref "C35") (pin "1") (pinfunction "1_1") (pintype "passive"))
      (node (ref "C36") (pin "2") (pinfunction "2_2") (pintype "passive"))
      (node (ref "C37") (pin "2") (pinfunction "2_2") (pintype "passive"))
      (node (ref "C38") (pin "2") (pinfunction "2_2") (pintype "passive"))
      (node (ref "C39") (pin "2") (pinfunction "2_2") (pintype "passive"))
      (node (ref "C40") (pin "2") (pinfunction "2_2") (pintype "passive"))
      (node (ref "C41") (pin "2") (pinfunction "2_2") (pintype "passive"))
      (node (ref "C42") (pin "2") (pinfunction "2_2") (pintype "passive"))
      (node (ref "C43") (pin "2") (pinfunction "2_2") (pintype "passive"))
      (node (ref "C44") (pin "2") (pinfunction "2_2") (pintype "passive"))
      (node (ref "C45") (pin "2") (pinfunction "2_2") (pintype "passive"))
      (node (ref "C46") (pin "2") (pinfunction "2_2") (pintype "passive"))
      (node (ref "C47") (pin "2") (pinfunction "2_2") (pintype "passive"))
      (node (ref "C48") (pin "2") (pinfunction "2_2") (pintype "passive"))
      (node (ref "C49") (pin "2") (pinfunction "2_2") (pintype "passive"))
      (node (ref "C5") (pin "2") (pinfunction "2_2") (pintype "passive"))
      (node (ref "C50") (pin "2") (pinfunction "2_2") (pintype "passive"))
      (node (ref "C51") (pin "2") (pinfunction "2_2") (pintype "passive"))
      (node (ref "C6") (pin "2") (pinfunction "2_2") (pintype "passive"))
      (node (ref "C9") (pin "2") (pinfunction "2_2") (pintype "passive"))
      (node (ref "CN1") (pin "10") (pinfunction "GND1_10") (pintype "passive"))
      (node (ref "CN1") (pin "11") (pinfunction "GND2_11") (pintype "passive"))
      (node (ref "CN1") (pin "12") (pinfunction "GND3_12") (pintype "passive"))
      (node (ref "CN1") (pin "13") (pinfunction "GND4_13") (pintype "passive"))
      (node (ref "CN1") (pin "6") (pinfunction "VSS_6") (pintype "passive"))
      (node (ref "J1") (pin "10") (pinfunction "10_10") (pintype "passive"))
      (node (ref "J1") (pin "2") (pinfunction "2_2") (pintype "passive"))
      (node (ref "J2") (pin "5") (pinfunction "VSS_5") (pintype "passive"))
      (node (ref "LED1") (pin "2") (pinfunction "K_2") (pintype "passive"))
      (node (ref "LED2") (pin "2") (pinfunction "K_2") (pintype "passive"))
      (node (ref "P1") (pin "4") (pinfunction "4_4") (pintype "passive"))
      (node (ref "RST_n1") (pin "1") (pinfunction "1_1") (pintype "passive"))
      (node (ref "U1") (pin "1") (pinfunction "GND_1") (pintype "passive"))
      (node (ref "U10") (pin "23") (pinfunction "GND_23") (pintype "passive"))
      (node (ref "U11") (pin "12") (pinfunction "VSS_12") (pintype "passive"))
      (node (ref "U11") (pin "34") (pinfunction "VSS_34") (pintype "passive"))
      (node (ref "U12") (pin "1") (pinfunction "GND_1") (pintype "passive"))
      (node (ref "U13") (pin "14") (pinfunction "GND_14") (pintype "passive"))
      (node (ref "U14") (pin "14") (pinfunction "GND_14") (pintype "passive"))
      (node (ref "U2") (pin "1") (pinfunction "GND_1") (pintype "passive"))
      (node (ref "U3") (pin "1") (pinfunction "GND_1") (pintype "passive"))
      (node (ref "U4") (pin "1") (pinfunction "GND_1") (pintype "power_in"))
      (node (ref "U4") (pin "121") (pinfunction "GND_121") (pintype "power_in"))
      (node (ref "U4") (pin "138") (pinfunction "GND_138") (pintype "power_in"))
      (node (ref "U4") (pin "23") (pinfunction "GND_23") (pintype "power_in"))
      (node (ref "U4") (pin "44") (pinfunction "GND_44") (pintype "power_in"))
      (node (ref "U4") (pin "61") (pinfunction "GND_61") (pintype "power_in"))
      (node (ref "U4") (pin "78") (pinfunction "GND_78") (pintype "power_in"))
      (node (ref "U4") (pin "99") (pinfunction "GND_99") (pintype "power_in"))
      (node (ref "U5") (pin "1") (pinfunction "GND_1") (pintype "passive"))
      (node (ref "U6") (pin "1") (pinfunction "GND_1") (pintype "passive"))
      (node (ref "U7") (pin "1") (pinfunction "GND_1") (pintype "passive"))
      (node (ref "U8") (pin "4") (pinfunction "GND_4") (pintype "passive"))
      (node (ref "U9") (pin "11") (pinfunction "VSS_11") (pintype "passive"))
      (node (ref "U9") (pin "12") (pinfunction "VSS_12") (pintype "passive"))
      (node (ref "U9") (pin "13") (pinfunction "VSS_13") (pintype "passive"))
      (node (ref "U9") (pin "14") (pinfunction "VSS_14") (pintype "passive"))
      (node (ref "U9") (pin "2") (pinfunction "VSS_2") (pintype "passive"))
      (node (ref "U9") (pin "22") (pinfunction "VSS_22") (pintype "passive"))
      (node (ref "U9") (pin "35") (pinfunction "VSS_35") (pintype "passive"))
      (node (ref "U9") (pin "41") (pinfunction "VSS_41") (pintype "passive"))
      (node (ref "U9") (pin "49") (pinfunction "VSS_49") (pintype "passive"))
      (node (ref "U9") (pin "5") (pinfunction "VSS_5") (pintype "passive"))
      (node (ref "U9") (pin "50") (pinfunction "VSS_50") (pintype "passive"))
      (node (ref "U9") (pin "63") (pinfunction "VSS_63") (pintype "passive"))
      (node (ref "U9") (pin "67") (pinfunction "VSS_67") (pintype "passive"))
      (node (ref "U9") (pin "68") (pinfunction "VSS_68") (pintype "passive"))
      (node (ref "U9") (pin "77") (pinfunction "VSS_77") (pintype "passive"))
      (node (ref "U9") (pin "78") (pinfunction "VSS_78") (pintype "passive"))
      (node (ref "U9") (pin "85") (pinfunction "VSS_85") (pintype "passive"))
      (node (ref "U9") (pin "98") (pinfunction "VSS_98") (pintype "passive"))
    )
    (net (code "258") (name "Net-(CN1-CD)") (class "Default")
      (node (ref "CN1") (pin "9") (pinfunction "CD_9") (pintype "passive"))
      (node (ref "R131") (pin "1") (pinfunction "1_1") (pintype "passive"))
    )
    (net (code "259") (name "Net-(LED1-A)") (class "Default")
      (node (ref "LED1") (pin "1") (pinfunction "A_1") (pintype "passive"))
      (node (ref "R127") (pin "2") (pinfunction "2_2") (pintype "passive"))
    )
    (net (code "260") (name "Net-(LED2-A)") (class "Default")
      (node (ref "LED2") (pin "1") (pinfunction "A_1") (pintype "passive"))
      (node (ref "R140") (pin "2") (pinfunction "2_2") (pintype "passive"))
    )
    (net (code "261") (name "Net-(U1-B1)") (class "Default")
      (node (ref "R1") (pin "1") (pinfunction "1_1") (pintype "passive"))
      (node (ref "U1") (pin "47") (pinfunction "B1_47") (pintype "passive"))
      (node (ref "U1") (pin "48") (pinfunction "GATE_48") (pintype "passive"))
    )
    (net (code "262") (name "Net-(U2-B1)") (class "Default")
      (node (ref "R2") (pin "1") (pinfunction "1_1") (pintype "passive"))
      (node (ref "U2") (pin "47") (pinfunction "B1_47") (pintype "passive"))
      (node (ref "U2") (pin "48") (pinfunction "GATE_48") (pintype "passive"))
    )
    (net (code "263") (name "Net-(U3-B1)") (class "Default")
      (node (ref "R3") (pin "1") (pinfunction "1_1") (pintype "passive"))
      (node (ref "U3") (pin "47") (pinfunction "B1_47") (pintype "passive"))
      (node (ref "U3") (pin "48") (pinfunction "GATE_48") (pintype "passive"))
    )
    (net (code "264") (name "Net-(U4-CLK_M1)") (class "Default")
      (node (ref "R64") (pin "1") (pinfunction "1_1") (pintype "passive"))
      (node (ref "RST_n1") (pin "2") (pinfunction "2_2") (pintype "passive"))
      (node (ref "U4") (pin "29") (pinfunction "CLK_M1_29") (pintype "input"))
    )
    (net (code "265") (name "Net-(U5-B1)") (class "Default")
      (node (ref "R65") (pin "1") (pinfunction "1_1") (pintype "passive"))
      (node (ref "U5") (pin "47") (pinfunction "B1_47") (pintype "passive"))
      (node (ref "U5") (pin "48") (pinfunction "GATE_48") (pintype "passive"))
    )
    (net (code "266") (name "Net-(U6-B1)") (class "Default")
      (node (ref "R66") (pin "1") (pinfunction "1_1") (pintype "passive"))
      (node (ref "U6") (pin "47") (pinfunction "B1_47") (pintype "passive"))
      (node (ref "U6") (pin "48") (pinfunction "GATE_48") (pintype "passive"))
    )
    (net (code "267") (name "Net-(U7-B1)") (class "Default")
      (node (ref "R67") (pin "1") (pinfunction "1_1") (pintype "passive"))
      (node (ref "U7") (pin "47") (pinfunction "B1_47") (pintype "passive"))
      (node (ref "U7") (pin "48") (pinfunction "GATE_48") (pintype "passive"))
    )
    (net (code "268") (name "Net-(U8-~{HOLD})") (class "Default")
      (node (ref "R129") (pin "1") (pinfunction "1_1") (pintype "passive"))
      (node (ref "U8") (pin "7") (pinfunction "~{HOLD}_7") (pintype "passive"))
    )
    (net (code "269") (name "Net-(U8-~{WP})") (class "Default")
      (node (ref "R130") (pin "1") (pinfunction "1_1") (pintype "passive"))
      (node (ref "U8") (pin "3") (pinfunction "~{WP}_3") (pintype "passive"))
    )
    (net (code "270") (name "VCC5") (class "Default")
      (node (ref "C16") (pin "1") (pinfunction "1_1") (pintype "passive"))
      (node (ref "C17") (pin "1") (pinfunction "1_1") (pintype "passive"))
      (node (ref "C18") (pin "1") (pinfunction "1_1") (pintype "passive"))
      (node (ref "C26") (pin "1") (pinfunction "1_1") (pintype "passive"))
      (node (ref "C27") (pin "1") (pinfunction "1_1") (pintype "passive"))
      (node (ref "C28") (pin "1") (pinfunction "1_1") (pintype "passive"))
      (node (ref "C29") (pin "1") (pinfunction "1_1") (pintype "passive"))
      (node (ref "C3") (pin "1") (pinfunction "1_1") (pintype "passive"))
      (node (ref "C30") (pin "1") (pinfunction "1_1") (pintype "passive"))
      (node (ref "C35") (pin "2") (pinfunction "2_2") (pintype "passive"))
      (node (ref "C36") (pin "1") (pinfunction "1_1") (pintype "passive"))
      (node (ref "C37") (pin "1") (pinfunction "1_1") (pintype "passive"))
      (node (ref "C38") (pin "1") (pinfunction "1_1") (pintype "passive"))
      (node (ref "C39") (pin "1") (pinfunction "1_1") (pintype "passive"))
      (node (ref "C40") (pin "1") (pinfunction "1_1") (pintype "passive"))
      (node (ref "C41") (pin "1") (pinfunction "1_1") (pintype "passive"))
      (node (ref "C42") (pin "1") (pinfunction "1_1") (pintype "passive"))
      (node (ref "C43") (pin "1") (pinfunction "1_1") (pintype "passive"))
      (node (ref "C44") (pin "1") (pinfunction "1_1") (pintype "passive"))
      (node (ref "C45") (pin "1") (pinfunction "1_1") (pintype "passive"))
      (node (ref "C46") (pin "1") (pinfunction "1_1") (pintype "passive"))
      (node (ref "C47") (pin "1") (pinfunction "1_1") (pintype "passive"))
      (node (ref "C48") (pin "1") (pinfunction "1_1") (pintype "passive"))
      (node (ref "C49") (pin "1") (pinfunction "1_1") (pintype "passive"))
      (node (ref "C5") (pin "1") (pinfunction "1_1") (pintype "passive"))
      (node (ref "C50") (pin "1") (pinfunction "1_1") (pintype "passive"))
      (node (ref "C51") (pin "1") (pinfunction "1_1") (pintype "passive"))
      (node (ref "C6") (pin "1") (pinfunction "1_1") (pintype "passive"))
      (node (ref "P1") (pin "1") (pinfunction "1_1") (pintype "passive"))
      (node (ref "R1") (pin "2") (pinfunction "2_2") (pintype "passive"))
      (node (ref "R10") (pin "2") (pinfunction "2_2") (pintype "passive"))
      (node (ref "R100") (pin "2") (pinfunction "2_2") (pintype "passive"))
      (node (ref "R101") (pin "2") (pinfunction "2_2") (pintype "passive"))
      (node (ref "R102") (pin "2") (pinfunction "2_2") (pintype "passive"))
      (node (ref "R103") (pin "2") (pinfunction "2_2") (pintype "passive"))
      (node (ref "R104") (pin "2") (pinfunction "2_2") (pintype "passive"))
      (node (ref "R105") (pin "2") (pinfunction "2_2") (pintype "passive"))
      (node (ref "R106") (pin "2") (pinfunction "2_2") (pintype "passive"))
      (node (ref "R107") (pin "2") (pinfunction "2_2") (pintype "passive"))
      (node (ref "R108") (pin "2") (pinfunction "2_2") (pintype "passive"))
      (node (ref "R109") (pin "2") (pinfunction "2_2") (pintype "passive"))
      (node (ref "R11") (pin "2") (pinfunction "2_2") (pintype "passive"))
      (node (ref "R110") (pin "2") (pinfunction "2_2") (pintype "passive"))
      (node (ref "R111") (pin "2") (pinfunction "2_2") (pintype "passive"))
      (node (ref "R112") (pin "2") (pinfunction "2_2") (pintype "passive"))
      (node (ref "R113") (pin "2") (pinfunction "2_2") (pintype "passive"))
      (node (ref "R114") (pin "2") (pinfunction "2_2") (pintype "passive"))
      (node (ref "R115") (pin "2") (pinfunction "2_2") (pintype "passive"))
      (node (ref "R116") (pin "2") (pinfunction "2_2") (pintype "passive"))
      (node (ref "R117") (pin "2") (pinfunction "2_2") (pintype "passive"))
      (node (ref "R118") (pin "2") (pinfunction "2_2") (pintype "passive"))
      (node (ref "R119") (pin "2") (pinfunction "2_2") (pintype "passive"))
      (node (ref "R12") (pin "2") (pinfunction "2_2") (pintype "passive"))
      (node (ref "R120") (pin "2") (pinfunction "2_2") (pintype "passive"))
      (node (ref "R121") (pin "2") (pinfunction "2_2") (pintype "passive"))
      (node (ref "R122") (pin "2") (pinfunction "2_2") (pintype "passive"))
      (node (ref "R123") (pin "2") (pinfunction "2_2") (pintype "passive"))
      (node (ref "R124") (pin "2") (pinfunction "2_2") (pintype "passive"))
      (node (ref "R125") (pin "2") (pinfunction "2_2") (pintype "passive"))
      (node (ref "R126") (pin "2") (pinfunction "2_2") (pintype "passive"))
      (node (ref "R13") (pin "2") (pinfunction "2_2") (pintype "passive"))
      (node (ref "R138") (pin "2") (pinfunction "2_2") (pintype "passive"))
      (node (ref "R139") (pin "2") (pinfunction "2_2") (pintype "passive"))
      (node (ref "R14") (pin "2") (pinfunction "2_2") (pintype "passive"))
      (node (ref "R15") (pin "2") (pinfunction "2_2") (pintype "passive"))
      (node (ref "R16") (pin "2") (pinfunction "2_2") (pintype "passive"))
      (node (ref "R17") (pin "2") (pinfunction "2_2") (pintype "passive"))
      (node (ref "R18") (pin "2") (pinfunction "2_2") (pintype "passive"))
      (node (ref "R19") (pin "2") (pinfunction "2_2") (pintype "passive"))
      (node (ref "R2") (pin "2") (pinfunction "2_2") (pintype "passive"))
      (node (ref "R20") (pin "2") (pinfunction "2_2") (pintype "passive"))
      (node (ref "R21") (pin "2") (pinfunction "2_2") (pintype "passive"))
      (node (ref "R22") (pin "2") (pinfunction "2_2") (pintype "passive"))
      (node (ref "R23") (pin "2") (pinfunction "2_2") (pintype "passive"))
      (node (ref "R24") (pin "2") (pinfunction "2_2") (pintype "passive"))
      (node (ref "R25") (pin "2") (pinfunction "2_2") (pintype "passive"))
      (node (ref "R26") (pin "2") (pinfunction "2_2") (pintype "passive"))
      (node (ref "R27") (pin "2") (pinfunction "2_2") (pintype "passive"))
      (node (ref "R28") (pin "2") (pinfunction "2_2") (pintype "passive"))
      (node (ref "R29") (pin "2") (pinfunction "2_2") (pintype "passive"))
      (node (ref "R3") (pin "2") (pinfunction "2_2") (pintype "passive"))
      (node (ref "R30") (pin "2") (pinfunction "2_2") (pintype "passive"))
      (node (ref "R31") (pin "2") (pinfunction "2_2") (pintype "passive"))
      (node (ref "R32") (pin "2") (pinfunction "2_2") (pintype "passive"))
      (node (ref "R33") (pin "2") (pinfunction "2_2") (pintype "passive"))
      (node (ref "R34") (pin "2") (pinfunction "2_2") (pintype "passive"))
      (node (ref "R35") (pin "2") (pinfunction "2_2") (pintype "passive"))
      (node (ref "R36") (pin "2") (pinfunction "2_2") (pintype "passive"))
      (node (ref "R37") (pin "2") (pinfunction "2_2") (pintype "passive"))
      (node (ref "R38") (pin "2") (pinfunction "2_2") (pintype "passive"))
      (node (ref "R39") (pin "2") (pinfunction "2_2") (pintype "passive"))
      (node (ref "R4") (pin "2") (pinfunction "2_2") (pintype "passive"))
      (node (ref "R40") (pin "2") (pinfunction "2_2") (pintype "passive"))
      (node (ref "R41") (pin "2") (pinfunction "2_2") (pintype "passive"))
      (node (ref "R42") (pin "2") (pinfunction "2_2") (pintype "passive"))
      (node (ref "R43") (pin "2") (pinfunction "2_2") (pintype "passive"))
      (node (ref "R44") (pin "2") (pinfunction "2_2") (pintype "passive"))
      (node (ref "R45") (pin "2") (pinfunction "2_2") (pintype "passive"))
      (node (ref "R46") (pin "2") (pinfunction "2_2") (pintype "passive"))
      (node (ref "R47") (pin "2") (pinfunction "2_2") (pintype "passive"))
      (node (ref "R48") (pin "2") (pinfunction "2_2") (pintype "passive"))
      (node (ref "R49") (pin "2") (pinfunction "2_2") (pintype "passive"))
      (node (ref "R5") (pin "2") (pinfunction "2_2") (pintype "passive"))
      (node (ref "R50") (pin "2") (pinfunction "2_2") (pintype "passive"))
      (node (ref "R51") (pin "2") (pinfunction "2_2") (pintype "passive"))
      (node (ref "R52") (pin "2") (pinfunction "2_2") (pintype "passive"))
      (node (ref "R53") (pin "2") (pinfunction "2_2") (pintype "passive"))
      (node (ref "R54") (pin "2") (pinfunction "2_2") (pintype "passive"))
      (node (ref "R55") (pin "2") (pinfunction "2_2") (pintype "passive"))
      (node (ref "R56") (pin "2") (pinfunction "2_2") (pintype "passive"))
      (node (ref "R57") (pin "2") (pinfunction "2_2") (pintype "passive"))
      (node (ref "R58") (pin "2") (pinfunction "2_2") (pintype "passive"))
      (node (ref "R59") (pin "2") (pinfunction "2_2") (pintype "passive"))
      (node (ref "R6") (pin "2") (pinfunction "2_2") (pintype "passive"))
      (node (ref "R60") (pin "2") (pinfunction "2_2") (pintype "passive"))
      (node (ref "R61") (pin "2") (pinfunction "2_2") (pintype "passive"))
      (node (ref "R62") (pin "2") (pinfunction "2_2") (pintype "passive"))
      (node (ref "R63") (pin "2") (pinfunction "2_2") (pintype "passive"))
      (node (ref "R65") (pin "2") (pinfunction "2_2") (pintype "passive"))
      (node (ref "R66") (pin "2") (pinfunction "2_2") (pintype "passive"))
      (node (ref "R67") (pin "2") (pinfunction "2_2") (pintype "passive"))
      (node (ref "R68") (pin "2") (pinfunction "2_2") (pintype "passive"))
      (node (ref "R69") (pin "2") (pinfunction "2_2") (pintype "passive"))
      (node (ref "R7") (pin "2") (pinfunction "2_2") (pintype "passive"))
      (node (ref "R70") (pin "2") (pinfunction "2_2") (pintype "passive"))
      (node (ref "R71") (pin "2") (pinfunction "2_2") (pintype "passive"))
      (node (ref "R72") (pin "2") (pinfunction "2_2") (pintype "passive"))
      (node (ref "R73") (pin "2") (pinfunction "2_2") (pintype "passive"))
      (node (ref "R74") (pin "2") (pinfunction "2_2") (pintype "passive"))
      (node (ref "R75") (pin "2") (pinfunction "2_2") (pintype "passive"))
      (node (ref "R76") (pin "2") (pinfunction "2_2") (pintype "passive"))
      (node (ref "R77") (pin "2") (pinfunction "2_2") (pintype "passive"))
      (node (ref "R78") (pin "2") (pinfunction "2_2") (pintype "passive"))
      (node (ref "R79") (pin "2") (pinfunction "2_2") (pintype "passive"))
      (node (ref "R8") (pin "2") (pinfunction "2_2") (pintype "passive"))
      (node (ref "R80") (pin "2") (pinfunction "2_2") (pintype "passive"))
      (node (ref "R81") (pin "2") (pinfunction "2_2") (pintype "passive"))
      (node (ref "R82") (pin "2") (pinfunction "2_2") (pintype "passive"))
      (node (ref "R83") (pin "2") (pinfunction "2_2") (pintype "passive"))
      (node (ref "R84") (pin "2") (pinfunction "2_2") (pintype "passive"))
      (node (ref "R85") (pin "2") (pinfunction "2_2") (pintype "passive"))
      (node (ref "R86") (pin "2") (pinfunction "2_2") (pintype "passive"))
      (node (ref "R87") (pin "2") (pinfunction "2_2") (pintype "passive"))
      (node (ref "R88") (pin "2") (pinfunction "2_2") (pintype "passive"))
      (node (ref "R89") (pin "2") (pinfunction "2_2") (pintype "passive"))
      (node (ref "R9") (pin "2") (pinfunction "2_2") (pintype "passive"))
      (node (ref "R90") (pin "2") (pinfunction "2_2") (pintype "passive"))
      (node (ref "R91") (pin "2") (pinfunction "2_2") (pintype "passive"))
      (node (ref "R92") (pin "2") (pinfunction "2_2") (pintype "passive"))
      (node (ref "R93") (pin "2") (pinfunction "2_2") (pintype "passive"))
      (node (ref "R94") (pin "2") (pinfunction "2_2") (pintype "passive"))
      (node (ref "R95") (pin "2") (pinfunction "2_2") (pintype "passive"))
      (node (ref "R96") (pin "2") (pinfunction "2_2") (pintype "passive"))
      (node (ref "R97") (pin "2") (pinfunction "2_2") (pintype "passive"))
      (node (ref "R98") (pin "2") (pinfunction "2_2") (pintype "passive"))
      (node (ref "R99") (pin "2") (pinfunction "2_2") (pintype "passive"))
      (node (ref "S1") (pin "3") (pinfunction "3_3") (pintype "passive"))
      (node (ref "U10") (pin "35") (pinfunction "VCC_35") (pintype "passive"))
      (node (ref "U11") (pin "11") (pinfunction "VCC_11") (pintype "passive"))
      (node (ref "U11") (pin "33") (pinfunction "VCC_33") (pintype "passive"))
      (node (ref "U12") (pin "3") (pinfunction "IN_3") (pintype "passive"))
      (node (ref "U13") (pin "28") (pinfunction "VCC_28") (pintype "passive"))
      (node (ref "U14") (pin "28") (pinfunction "VCC_28") (pintype "passive"))
      (node (ref "U9") (pin "10") (pinfunction "VCC_10") (pintype "passive"))
      (node (ref "U9") (pin "21") (pinfunction "VCC_21") (pintype "passive"))
      (node (ref "U9") (pin "32") (pinfunction "VCC_32") (pintype "passive"))
      (node (ref "U9") (pin "39") (pinfunction "VCC_39") (pintype "passive"))
      (node (ref "U9") (pin "42") (pinfunction "VCC_42") (pintype "passive"))
      (node (ref "U9") (pin "48") (pinfunction "VCC_48") (pintype "passive"))
      (node (ref "U9") (pin "57") (pinfunction "VCC_57") (pintype "passive"))
      (node (ref "U9") (pin "69") (pinfunction "VCC_69") (pintype "passive"))
      (node (ref "U9") (pin "71") (pinfunction "VCC_71") (pintype "passive"))
      (node (ref "U9") (pin "8") (pinfunction "VCC_8") (pintype "passive"))
      (node (ref "U9") (pin "84") (pinfunction "VCC_84") (pintype "passive"))
      (node (ref "U9") (pin "9") (pinfunction "VCC_9") (pintype "passive"))
      (node (ref "U9") (pin "91") (pinfunction "VCC_91") (pintype "passive"))
      (node (ref "U9") (pin "97") (pinfunction "VCC_97") (pintype "passive"))
    )
    (net (code "271") (name "VCC5_IN") (class "Default")
      (node (ref "C32") (pin "1") (pinfunction "1_1") (pintype "passive"))
      (node (ref "C34") (pin "2") (pinfunction "2_2") (pintype "passive"))
      (node (ref "J2") (pin "1") (pinfunction "VCC_1") (pintype "passive"))
      (node (ref "S1") (pin "1") (pinfunction "1_1") (pintype "passive"))
    )
    (net (code "272") (name "VDD2.5") (class "Default")
      (node (ref "J1") (pin "4") (pinfunction "4_4") (pintype "passive"))
      (node (ref "U4") (pin "2") (pinfunction "2.5V_2") (pintype "power_in"))
    )
    (net (code "273") (name "VDD3.3") (class "Default")
      (node (ref "C11") (pin "1") (pinfunction "1_1") (pintype "passive"))
      (node (ref "C12") (pin "1") (pinfunction "1_1") (pintype "passive"))
      (node (ref "C22") (pin "1") (pinfunction "1_1") (pintype "passive"))
      (node (ref "C23") (pin "1") (pinfunction "1_1") (pintype "passive"))
      (node (ref "C24") (pin "1") (pinfunction "1_1") (pintype "passive"))
      (node (ref "C25") (pin "2") (pinfunction "2_2") (pintype "passive"))
      (node (ref "C31") (pin "2") (pinfunction "2_2") (pintype "passive"))
      (node (ref "C33") (pin "1") (pinfunction "1_1") (pintype "passive"))
      (node (ref "C9") (pin "1") (pinfunction "1_1") (pintype "passive"))
      (node (ref "CN1") (pin "4") (pinfunction "VDD_4") (pintype "passive"))
      (node (ref "R128") (pin "2") (pinfunction "2_2") (pintype "passive"))
      (node (ref "R129") (pin "2") (pinfunction "2_2") (pintype "passive"))
      (node (ref "R130") (pin "2") (pinfunction "2_2") (pintype "passive"))
      (node (ref "R131") (pin "2") (pinfunction "2_2") (pintype "passive"))
      (node (ref "R132") (pin "2") (pinfunction "2_2") (pintype "passive"))
      (node (ref "R133") (pin "2") (pinfunction "2_2") (pintype "passive"))
      (node (ref "R134") (pin "2") (pinfunction "2_2") (pintype "passive"))
      (node (ref "R135") (pin "2") (pinfunction "2_2") (pintype "passive"))
      (node (ref "R136") (pin "2") (pinfunction "2_2") (pintype "passive"))
      (node (ref "R137") (pin "2") (pinfunction "2_2") (pintype "passive"))
      (node (ref "R140") (pin "1") (pinfunction "1_1") (pintype "passive"))
      (node (ref "R64") (pin "2") (pinfunction "2_2") (pintype "passive"))
      (node (ref "U1") (pin "2") (pinfunction "A1_2") (pintype "passive"))
      (node (ref "U12") (pin "2") (pinfunction "OUT_2") (pintype "passive"))
      (node (ref "U12") (pin "4") (pinfunction "OUT_4") (pintype "passive"))
      (node (ref "U2") (pin "2") (pinfunction "A1_2") (pintype "passive"))
      (node (ref "U3") (pin "2") (pinfunction "A1_2") (pintype "passive"))
      (node (ref "U4") (pin "100") (pinfunction "3.3V_100") (pintype "power_in"))
      (node (ref "U4") (pin "139") (pinfunction "3.3V_139") (pintype "power_in"))
      (node (ref "U4") (pin "22") (pinfunction "3.3V_22") (pintype "power_in"))
      (node (ref "U4") (pin "60") (pinfunction "3.3V_60") (pintype "power_in"))
      (node (ref "U5") (pin "2") (pinfunction "A1_2") (pintype "passive"))
      (node (ref "U6") (pin "2") (pinfunction "A1_2") (pintype "passive"))
      (node (ref "U7") (pin "2") (pinfunction "A1_2") (pintype "passive"))
      (node (ref "U8") (pin "8") (pinfunction "VCC_8") (pintype "passive"))
    )
    (net (code "274") (name "unconnected-(J1-Pad6)") (class "Default")
      (node (ref "J1") (pin "6") (pinfunction "6_6") (pintype "passive"))
    )
    (net (code "275") (name "unconnected-(J1-Pad7)") (class "Default")
      (node (ref "J1") (pin "7") (pinfunction "7_7") (pintype "passive+no_connect"))
    )
    (net (code "276") (name "unconnected-(J1-Pad8)") (class "Default")
      (node (ref "J1") (pin "8") (pinfunction "8_8") (pintype "passive+no_connect"))
    )
    (net (code "277") (name "unconnected-(J2-D+-Pad3)") (class "Default")
      (node (ref "J2") (pin "3") (pinfunction "D+_3") (pintype "passive+no_connect"))
    )
    (net (code "278") (name "unconnected-(J2-D--Pad2)") (class "Default")
      (node (ref "J2") (pin "2") (pinfunction "D-_2") (pintype "passive+no_connect"))
    )
    (net (code "279") (name "unconnected-(J2-ID-Pad4)") (class "Default")
      (node (ref "J2") (pin "4") (pinfunction "ID_4") (pintype "passive+no_connect"))
    )
    (net (code "280") (name "unconnected-(S1-Pad2)") (class "Default")
      (node (ref "S1") (pin "2") (pinfunction "2_2") (pintype "passive"))
    )
    (net (code "281") (name "unconnected-(S1-Pad4)") (class "Default")
      (node (ref "S1") (pin "4") (pinfunction "4_4") (pintype "passive"))
    )
    (net (code "282") (name "unconnected-(S1-Pad5)") (class "Default")
      (node (ref "S1") (pin "5") (pinfunction "5_5") (pintype "passive"))
    )
    (net (code "283") (name "unconnected-(S1-Pad6)") (class "Default")
      (node (ref "S1") (pin "6") (pinfunction "6_6") (pintype "passive"))
    )
    (net (code "284") (name "unconnected-(U1-A2-Pad3)") (class "Default")
      (node (ref "U1") (pin "3") (pinfunction "A2_3") (pintype "passive+no_connect"))
    )
    (net (code "285") (name "unconnected-(U1-A3-Pad4)") (class "Default")
      (node (ref "U1") (pin "4") (pinfunction "A3_4") (pintype "passive+no_connect"))
    )
    (net (code "286") (name "unconnected-(U1-B2-Pad46)") (class "Default")
      (node (ref "U1") (pin "46") (pinfunction "B2_46") (pintype "passive+no_connect"))
    )
    (net (code "287") (name "unconnected-(U1-B3-Pad45)") (class "Default")
      (node (ref "U1") (pin "45") (pinfunction "B3_45") (pintype "passive+no_connect"))
    )
    (net (code "288") (name "unconnected-(U2-A2-Pad3)") (class "Default")
      (node (ref "U2") (pin "3") (pinfunction "A2_3") (pintype "passive+no_connect"))
    )
    (net (code "289") (name "unconnected-(U2-A3-Pad4)") (class "Default")
      (node (ref "U2") (pin "4") (pinfunction "A3_4") (pintype "passive+no_connect"))
    )
    (net (code "290") (name "unconnected-(U2-B2-Pad46)") (class "Default")
      (node (ref "U2") (pin "46") (pinfunction "B2_46") (pintype "passive+no_connect"))
    )
    (net (code "291") (name "unconnected-(U2-B3-Pad45)") (class "Default")
      (node (ref "U2") (pin "45") (pinfunction "B3_45") (pintype "passive+no_connect"))
    )
    (net (code "292") (name "unconnected-(U3-A2-Pad3)") (class "Default")
      (node (ref "U3") (pin "3") (pinfunction "A2_3") (pintype "passive+no_connect"))
    )
    (net (code "293") (name "unconnected-(U3-A3-Pad4)") (class "Default")
      (node (ref "U3") (pin "4") (pinfunction "A3_4") (pintype "passive+no_connect"))
    )
    (net (code "294") (name "unconnected-(U3-B2-Pad46)") (class "Default")
      (node (ref "U3") (pin "46") (pinfunction "B2_46") (pintype "passive+no_connect"))
    )
    (net (code "295") (name "unconnected-(U3-B3-Pad45)") (class "Default")
      (node (ref "U3") (pin "45") (pinfunction "B3_45") (pintype "passive+no_connect"))
    )
    (net (code "296") (name "unconnected-(U4-CLK_E15-Pad111)") (class "Default")
      (node (ref "U4") (pin "111") (pinfunction "CLK_E15_111") (pintype "input+no_connect"))
    )
    (net (code "297") (name "unconnected-(U4-CLK_E16-Pad110)") (class "Default")
      (node (ref "U4") (pin "110") (pinfunction "CLK_E16_110") (pintype "input+no_connect"))
    )
    (net (code "298") (name "unconnected-(U4-CLK_M2-Pad30)") (class "Default")
      (node (ref "U4") (pin "30") (pinfunction "CLK_M2_30") (pintype "input+no_connect"))
    )
    (net (code "299") (name "unconnected-(U4-CLK_M15-Pad94)") (class "Default")
      (node (ref "U4") (pin "94") (pinfunction "CLK_M15_94") (pintype "input+no_connect"))
    )
    (net (code "300") (name "unconnected-(U4-CLK_M16-Pad95)") (class "Default")
      (node (ref "U4") (pin "95") (pinfunction "CLK_M16_95") (pintype "input+no_connect"))
    )
    (net (code "301") (name "unconnected-(U5-A2-Pad3)") (class "Default")
      (node (ref "U5") (pin "3") (pinfunction "A2_3") (pintype "passive+no_connect"))
    )
    (net (code "302") (name "unconnected-(U5-A3-Pad4)") (class "Default")
      (node (ref "U5") (pin "4") (pinfunction "A3_4") (pintype "passive+no_connect"))
    )
    (net (code "303") (name "unconnected-(U5-B2-Pad46)") (class "Default")
      (node (ref "U5") (pin "46") (pinfunction "B2_46") (pintype "passive+no_connect"))
    )
    (net (code "304") (name "unconnected-(U5-B3-Pad45)") (class "Default")
      (node (ref "U5") (pin "45") (pinfunction "B3_45") (pintype "passive+no_connect"))
    )
    (net (code "305") (name "unconnected-(U6-A2-Pad3)") (class "Default")
      (node (ref "U6") (pin "3") (pinfunction "A2_3") (pintype "passive+no_connect"))
    )
    (net (code "306") (name "unconnected-(U6-A3-Pad4)") (class "Default")
      (node (ref "U6") (pin "4") (pinfunction "A3_4") (pintype "passive+no_connect"))
    )
    (net (code "307") (name "unconnected-(U6-B2-Pad46)") (class "Default")
      (node (ref "U6") (pin "46") (pinfunction "B2_46") (pintype "passive+no_connect"))
    )
    (net (code "308") (name "unconnected-(U6-B3-Pad45)") (class "Default")
      (node (ref "U6") (pin "45") (pinfunction "B3_45") (pintype "passive+no_connect"))
    )
    (net (code "309") (name "unconnected-(U7-A2-Pad3)") (class "Default")
      (node (ref "U7") (pin "3") (pinfunction "A2_3") (pintype "passive+no_connect"))
    )
    (net (code "310") (name "unconnected-(U7-A3-Pad4)") (class "Default")
      (node (ref "U7") (pin "4") (pinfunction "A3_4") (pintype "passive+no_connect"))
    )
    (net (code "311") (name "unconnected-(U7-A23-Pad24)") (class "Default")
      (node (ref "U7") (pin "24") (pinfunction "A23_24") (pintype "passive+no_connect"))
    )
    (net (code "312") (name "unconnected-(U7-B2-Pad46)") (class "Default")
      (node (ref "U7") (pin "46") (pinfunction "B2_46") (pintype "passive+no_connect"))
    )
    (net (code "313") (name "unconnected-(U7-B3-Pad45)") (class "Default")
      (node (ref "U7") (pin "45") (pinfunction "B3_45") (pintype "passive+no_connect"))
    )
    (net (code "314") (name "unconnected-(U7-B23-Pad25)") (class "Default")
      (node (ref "U7") (pin "25") (pinfunction "B23_25") (pintype "passive+no_connect"))
    )
    (net (code "315") (name "unconnected-(U9A-NC-Pad20)") (class "Default")
      (node (ref "U9") (pin "20") (pinfunction "NC_20") (pintype "passive+no_connect"))
    )
    (net (code "316") (name "unconnected-(U9A-NC-Pad27)") (class "Default")
      (node (ref "U9") (pin "27") (pinfunction "NC_27") (pintype "passive+no_connect"))
    )
    (net (code "317") (name "unconnected-(U9A-NC-Pad29)") (class "Default")
      (node (ref "U9") (pin "29") (pinfunction "NC_29") (pintype "passive+no_connect"))
    )
    (net (code "318") (name "unconnected-(U9A-NC-Pad30)") (class "Default")
      (node (ref "U9") (pin "30") (pinfunction "NC_30") (pintype "passive+no_connect"))
    )
    (net (code "319") (name "unconnected-(U9A-NC-Pad31)") (class "Default")
      (node (ref "U9") (pin "31") (pinfunction "NC_31") (pintype "passive+no_connect"))
    )
    (net (code "320") (name "unconnected-(U9A-NC-Pad43)") (class "Default")
      (node (ref "U9") (pin "43") (pinfunction "NC_43") (pintype "passive+no_connect"))
    )
    (net (code "321") (name "unconnected-(U9A-NC-Pad44)") (class "Default")
      (node (ref "U9") (pin "44") (pinfunction "NC_44") (pintype "passive+no_connect"))
    )
    (net (code "322") (name "unconnected-(U9A-NC-Pad45)") (class "Default")
      (node (ref "U9") (pin "45") (pinfunction "NC_45") (pintype "passive+no_connect"))
    )
    (net (code "323") (name "unconnected-(U9A-NC-Pad46)") (class "Default")
      (node (ref "U9") (pin "46") (pinfunction "NC_46") (pintype "passive+no_connect"))
    )
    (net (code "324") (name "unconnected-(U9A-NC-Pad47)") (class "Default")
      (node (ref "U9") (pin "47") (pinfunction "NC_47") (pintype "passive+no_connect"))
    )
    (net (code "325") (name "unconnected-(U10-NC-Pad5)") (class "Default")
      (node (ref "U10") (pin "5") (pinfunction "NC_5") (pintype "passive+no_connect"))
    )
    (net (code "326") (name "unconnected-(U10-NC-Pad7)") (class "Default")
      (node (ref "U10") (pin "7") (pinfunction "NC_7") (pintype "passive+no_connect"))
    )
    (net (code "327") (name "unconnected-(U10-NC-Pad8)") (class "Default")
      (node (ref "U10") (pin "8") (pinfunction "NC_8") (pintype "passive+no_connect"))
    )
    (net (code "328") (name "unconnected-(U10-NC-Pad17)") (class "Default")
      (node (ref "U10") (pin "17") (pinfunction "NC_17") (pintype "passive+no_connect"))
    )
    (net (code "329") (name "unconnected-(U10-NC-Pad29)") (class "Default")
      (node (ref "U10") (pin "29") (pinfunction "NC_29") (pintype "passive+no_connect"))
    )
    (net (code "330") (name "unconnected-(U13-CAS0-Pad12)") (class "Default")
      (node (ref "U13") (pin "12") (pinfunction "CAS0_12") (pintype "passive+no_connect"))
    )
    (net (code "331") (name "unconnected-(U13-CAS1-Pad13)") (class "Default")
      (node (ref "U13") (pin "13") (pinfunction "CAS1_13") (pintype "passive+no_connect"))
    )
    (net (code "332") (name "unconnected-(U13-CAS2-Pad15)") (class "Default")
      (node (ref "U13") (pin "15") (pinfunction "CAS2_15") (pintype "passive+no_connect"))
    )
    (net (code "333") (name "unconnected-(U14-NC-Pad1)") (class "Default")
      (node (ref "U14") (pin "1") (pinfunction "NC_1") (pintype "passive+no_connect"))
    )
    (net (code "334") (name "unconnected-(U14-NC-Pad11)") (class "Default")
      (node (ref "U14") (pin "11") (pinfunction "NC_11") (pintype "passive+no_connect"))
    )
    (net (code "335") (name "unconnected-(U14-NC-Pad15)") (class "Default")
      (node (ref "U14") (pin "15") (pinfunction "NC_15") (pintype "passive+no_connect"))
    )
    (net (code "336") (name "unconnected-(U14-NC-Pad25)") (class "Default")
      (node (ref "U14") (pin "25") (pinfunction "NC_25") (pintype "passive+no_connect"))
    )
  )
)
